# 02.net
KiCad netlist of a schematic drawn in Altium Designer
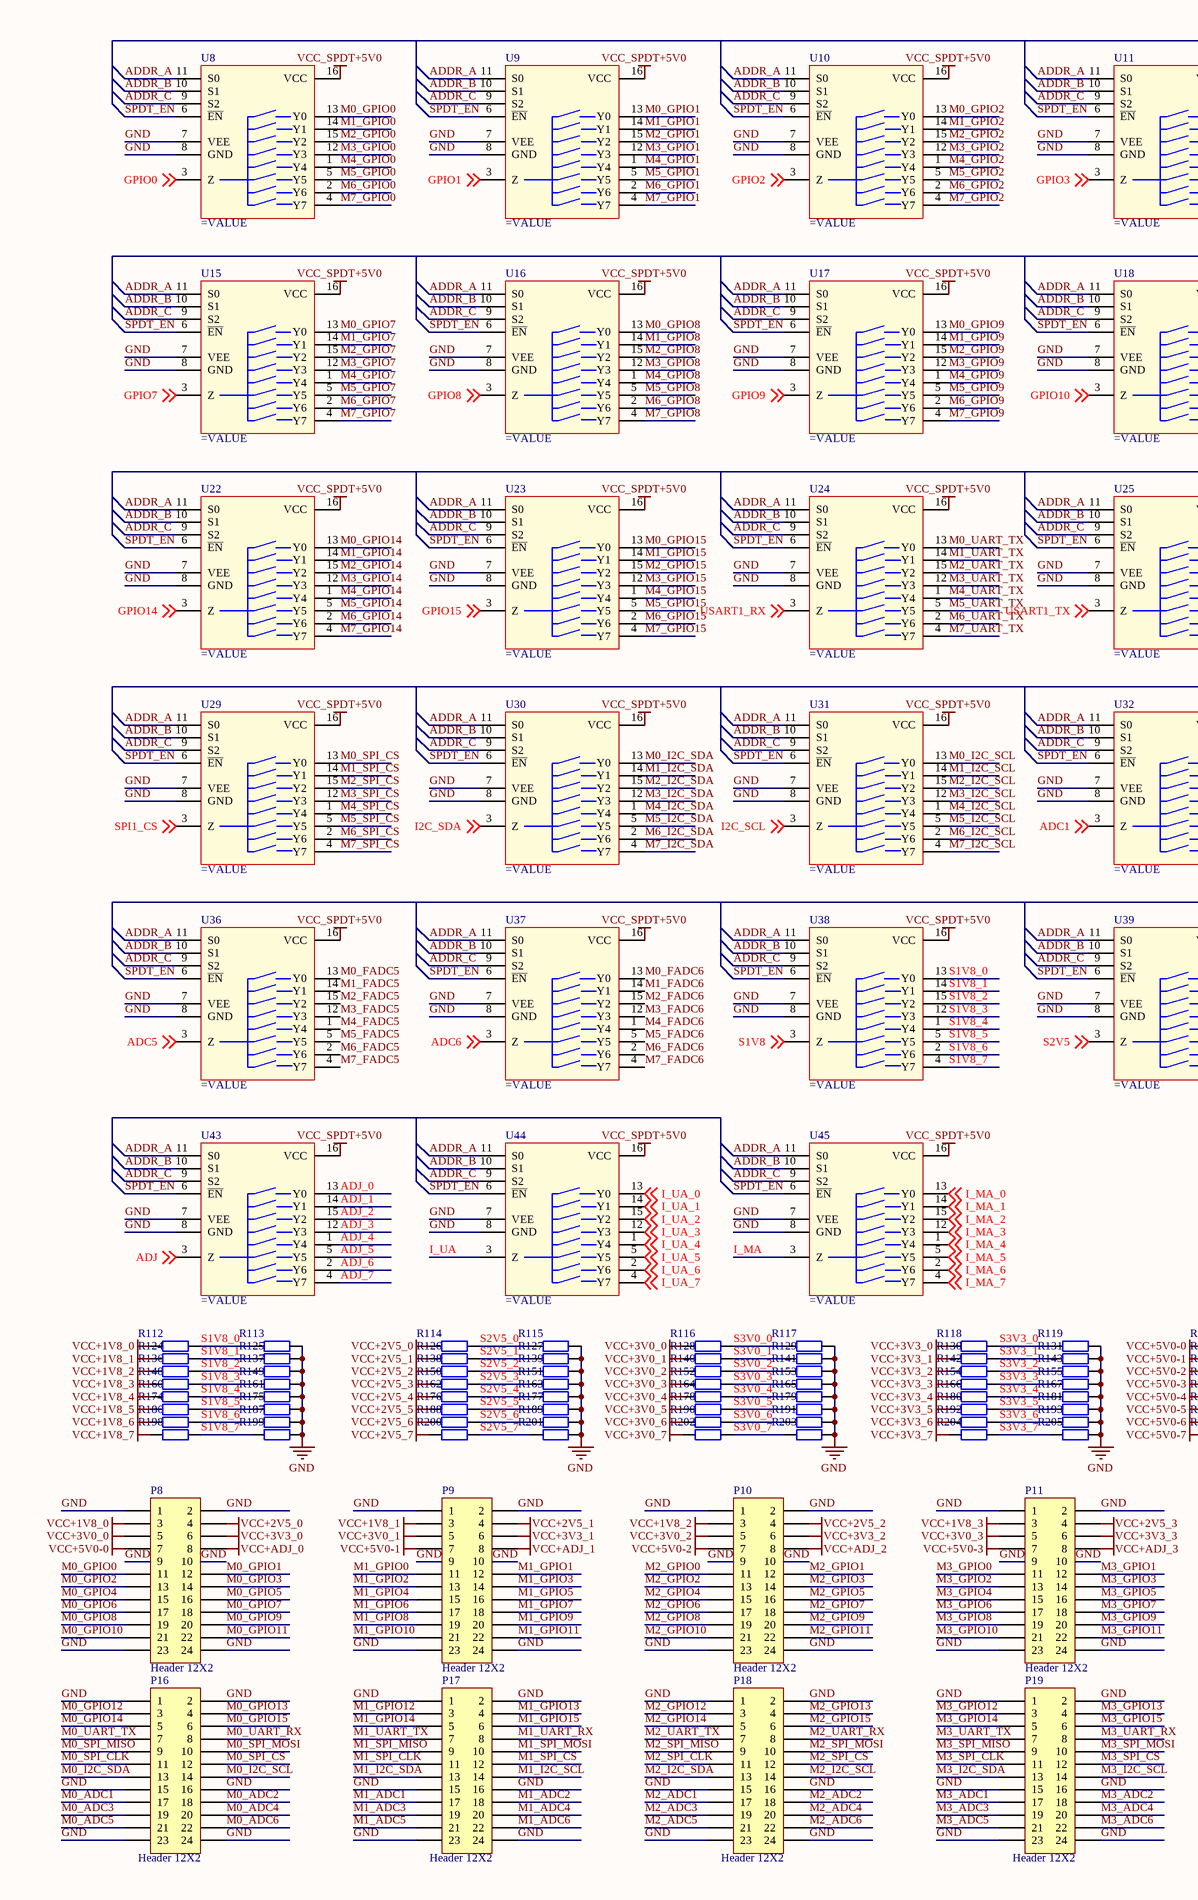
[diagram p0: 通用工装板02.SchDoc, left]
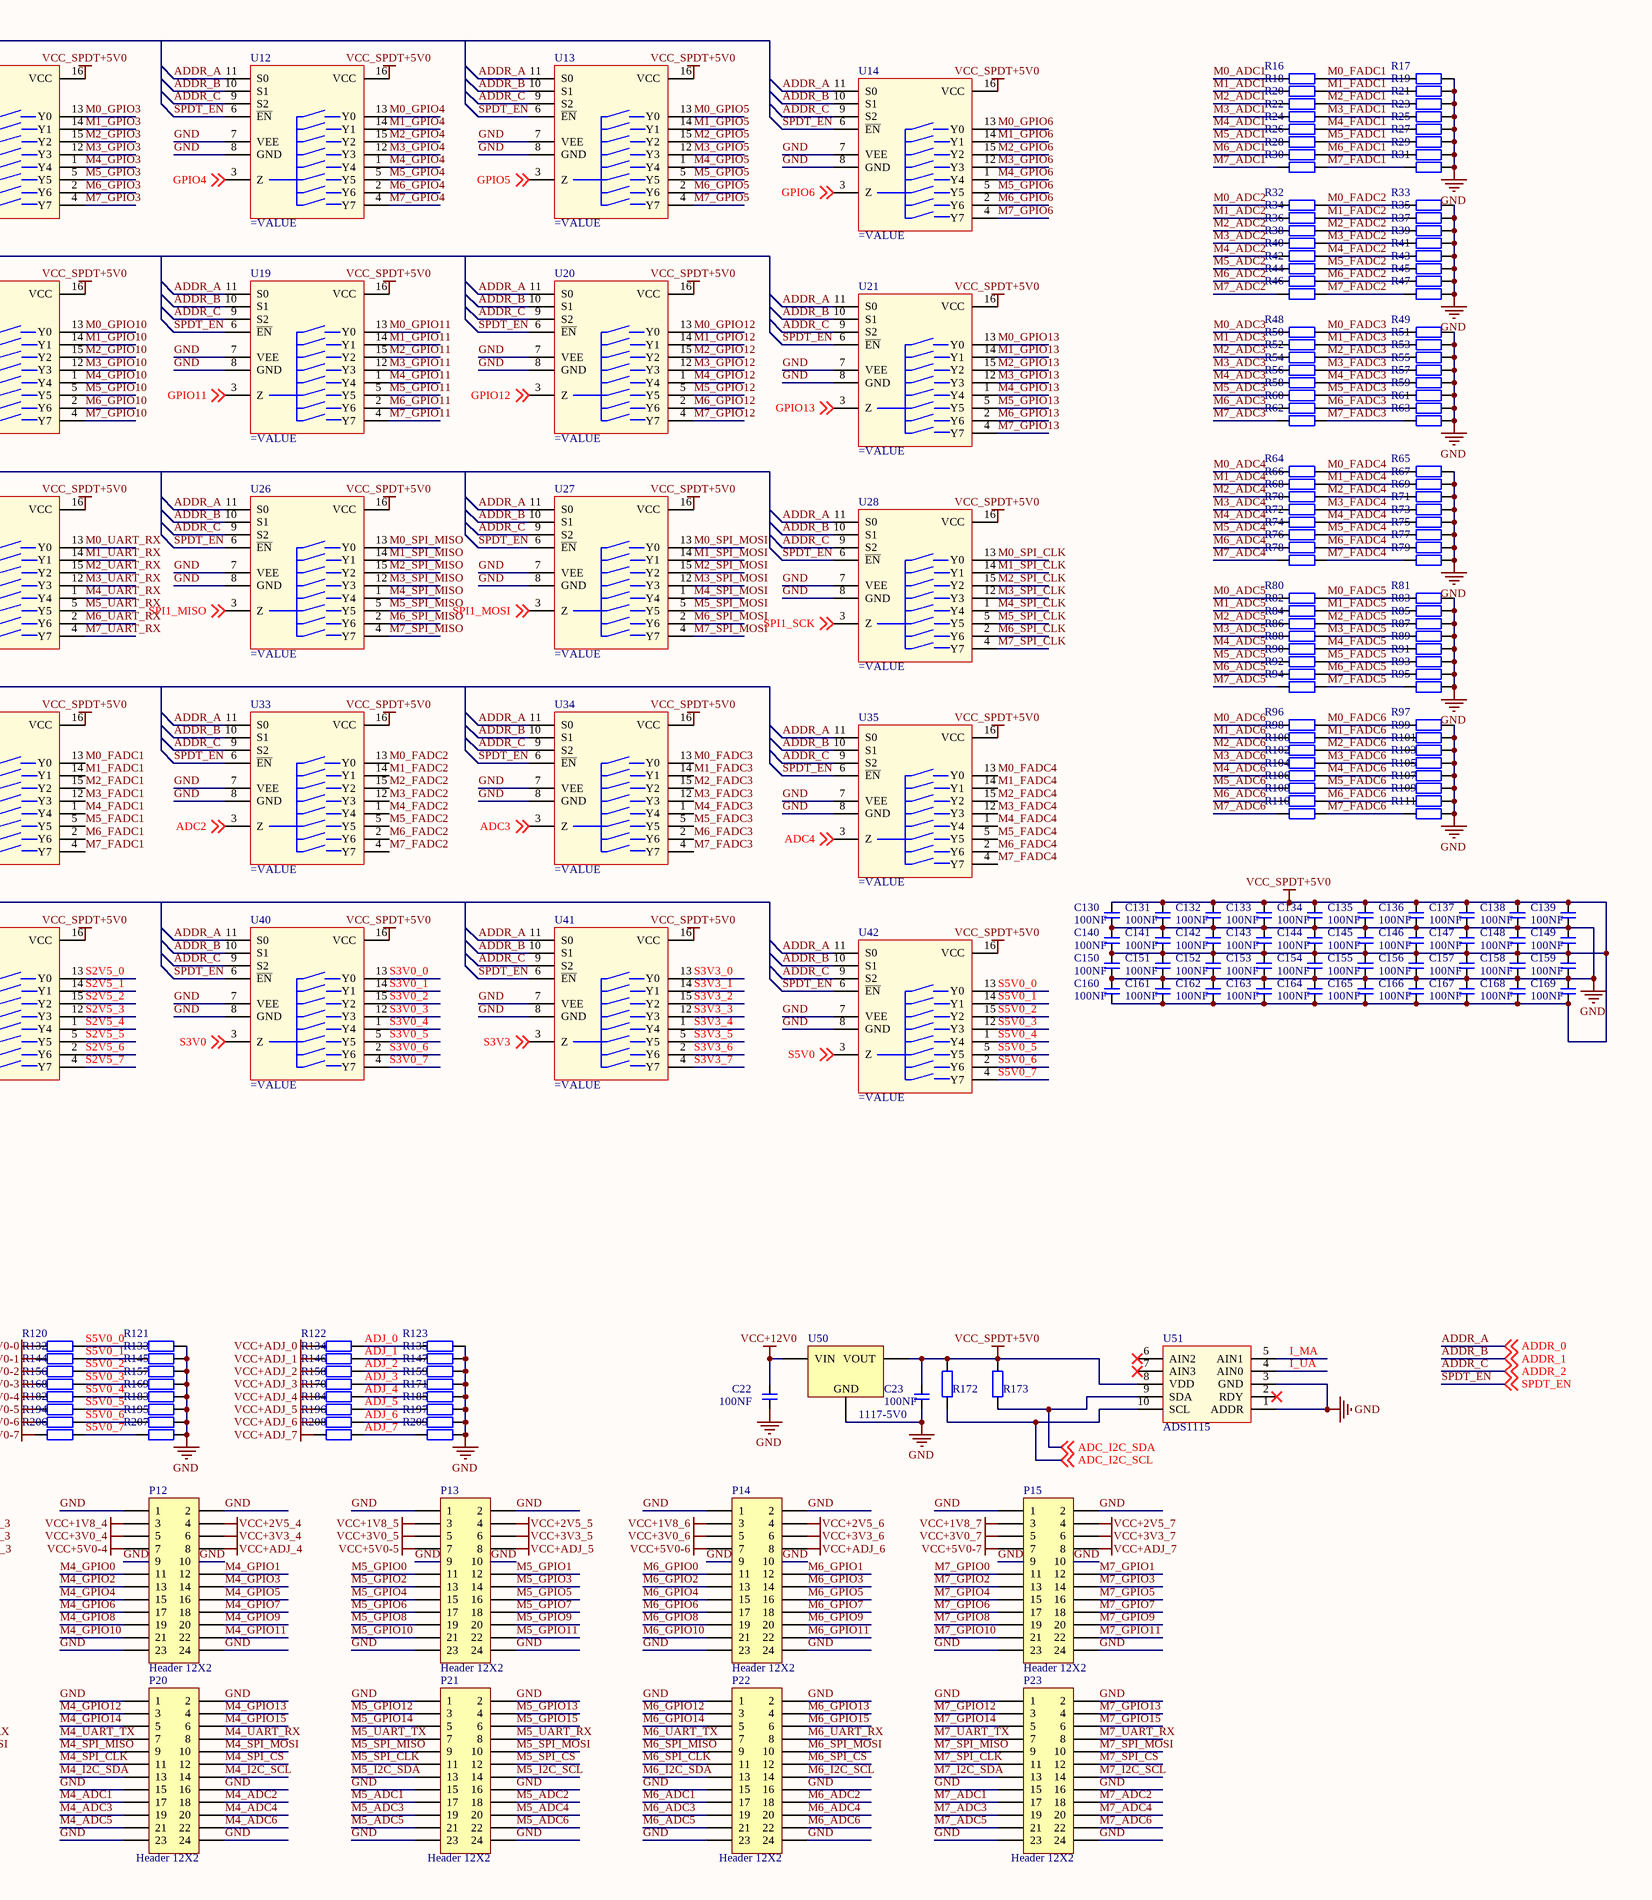
[diagram p1: 通用工装板02.SchDoc, right]

(export (version "E")
  (design (tool "Eeschema 10.0.6"))
  (components
    (comp (ref "C22")
      (value "100NF")
      (footprint "c0402")
      (description "无极性电容")
      (libsource (lib "瑞臻信息") (part "无极性电容"))
    )
    (comp (ref "C23")
      (value "100NF")
      (footprint "c0402")
      (description "无极性电容")
      (libsource (lib "瑞臻信息") (part "无极性电容"))
    )
    (comp (ref "C130")
      (value "100NF")
      (footprint "c0402")
      (description "无极性电容")
      (libsource (lib "瑞臻信息") (part "无极性电容"))
    )
    (comp (ref "C131")
      (value "100NF")
      (footprint "c0402")
      (description "无极性电容")
      (libsource (lib "瑞臻信息") (part "无极性电容"))
    )
    (comp (ref "C132")
      (value "100NF")
      (footprint "c0402")
      (description "无极性电容")
      (libsource (lib "瑞臻信息") (part "无极性电容"))
    )
    (comp (ref "C133")
      (value "100NF")
      (footprint "c0402")
      (description "无极性电容")
      (libsource (lib "瑞臻信息") (part "无极性电容"))
    )
    (comp (ref "C134")
      (value "100NF")
      (footprint "c0402")
      (description "无极性电容")
      (libsource (lib "瑞臻信息") (part "无极性电容"))
    )
    (comp (ref "C135")
      (value "100NF")
      (footprint "c0402")
      (description "无极性电容")
      (libsource (lib "瑞臻信息") (part "无极性电容"))
    )
    (comp (ref "C136")
      (value "100NF")
      (footprint "c0402")
      (description "无极性电容")
      (libsource (lib "瑞臻信息") (part "无极性电容"))
    )
    (comp (ref "C137")
      (value "100NF")
      (footprint "c0402")
      (description "无极性电容")
      (libsource (lib "瑞臻信息") (part "无极性电容"))
    )
    (comp (ref "C138")
      (value "100NF")
      (footprint "c0402")
      (description "无极性电容")
      (libsource (lib "瑞臻信息") (part "无极性电容"))
    )
    (comp (ref "C139")
      (value "100NF")
      (footprint "c0402")
      (description "无极性电容")
      (libsource (lib "瑞臻信息") (part "无极性电容"))
    )
    (comp (ref "C140")
      (value "100NF")
      (footprint "c0402")
      (description "无极性电容")
      (libsource (lib "瑞臻信息") (part "无极性电容"))
    )
    (comp (ref "C141")
      (value "100NF")
      (footprint "c0402")
      (description "无极性电容")
      (libsource (lib "瑞臻信息") (part "无极性电容"))
    )
    (comp (ref "C142")
      (value "100NF")
      (footprint "c0402")
      (description "无极性电容")
      (libsource (lib "瑞臻信息") (part "无极性电容"))
    )
    (comp (ref "C143")
      (value "100NF")
      (footprint "c0402")
      (description "无极性电容")
      (libsource (lib "瑞臻信息") (part "无极性电容"))
    )
    (comp (ref "C144")
      (value "100NF")
      (footprint "c0402")
      (description "无极性电容")
      (libsource (lib "瑞臻信息") (part "无极性电容"))
    )
    (comp (ref "C145")
      (value "100NF")
      (footprint "c0402")
      (description "无极性电容")
      (libsource (lib "瑞臻信息") (part "无极性电容"))
    )
    (comp (ref "C146")
      (value "100NF")
      (footprint "c0402")
      (description "无极性电容")
      (libsource (lib "瑞臻信息") (part "无极性电容"))
    )
    (comp (ref "C147")
      (value "100NF")
      (footprint "c0402")
      (description "无极性电容")
      (libsource (lib "瑞臻信息") (part "无极性电容"))
    )
    (comp (ref "C148")
      (value "100NF")
      (footprint "c0402")
      (description "无极性电容")
      (libsource (lib "瑞臻信息") (part "无极性电容"))
    )
    (comp (ref "C149")
      (value "100NF")
      (footprint "c0402")
      (description "无极性电容")
      (libsource (lib "瑞臻信息") (part "无极性电容"))
    )
    (comp (ref "C150")
      (value "100NF")
      (footprint "c0402")
      (description "无极性电容")
      (libsource (lib "瑞臻信息") (part "无极性电容"))
    )
    (comp (ref "C151")
      (value "100NF")
      (footprint "c0402")
      (description "无极性电容")
      (libsource (lib "瑞臻信息") (part "无极性电容"))
    )
    (comp (ref "C152")
      (value "100NF")
      (footprint "c0402")
      (description "无极性电容")
      (libsource (lib "瑞臻信息") (part "无极性电容"))
    )
    (comp (ref "C153")
      (value "100NF")
      (footprint "c0402")
      (description "无极性电容")
      (libsource (lib "瑞臻信息") (part "无极性电容"))
    )
    (comp (ref "C154")
      (value "100NF")
      (footprint "c0402")
      (description "无极性电容")
      (libsource (lib "瑞臻信息") (part "无极性电容"))
    )
    (comp (ref "C155")
      (value "100NF")
      (footprint "c0402")
      (description "无极性电容")
      (libsource (lib "瑞臻信息") (part "无极性电容"))
    )
    (comp (ref "C156")
      (value "100NF")
      (footprint "c0402")
      (description "无极性电容")
      (libsource (lib "瑞臻信息") (part "无极性电容"))
    )
    (comp (ref "C157")
      (value "100NF")
      (footprint "c0402")
      (description "无极性电容")
      (libsource (lib "瑞臻信息") (part "无极性电容"))
    )
    (comp (ref "C158")
      (value "100NF")
      (footprint "c0402")
      (description "无极性电容")
      (libsource (lib "瑞臻信息") (part "无极性电容"))
    )
    (comp (ref "C159")
      (value "100NF")
      (footprint "c0402")
      (description "无极性电容")
      (libsource (lib "瑞臻信息") (part "无极性电容"))
    )
    (comp (ref "C160")
      (value "100NF")
      (footprint "c0402")
      (description "无极性电容")
      (libsource (lib "瑞臻信息") (part "无极性电容"))
    )
    (comp (ref "C161")
      (value "100NF")
      (footprint "c0402")
      (description "无极性电容")
      (libsource (lib "瑞臻信息") (part "无极性电容"))
    )
    (comp (ref "C162")
      (value "100NF")
      (footprint "c0402")
      (description "无极性电容")
      (libsource (lib "瑞臻信息") (part "无极性电容"))
    )
    (comp (ref "C163")
      (value "100NF")
      (footprint "c0402")
      (description "无极性电容")
      (libsource (lib "瑞臻信息") (part "无极性电容"))
    )
    (comp (ref "C164")
      (value "100NF")
      (footprint "c0402")
      (description "无极性电容")
      (libsource (lib "瑞臻信息") (part "无极性电容"))
    )
    (comp (ref "C165")
      (value "100NF")
      (footprint "c0402")
      (description "无极性电容")
      (libsource (lib "瑞臻信息") (part "无极性电容"))
    )
    (comp (ref "C166")
      (value "100NF")
      (footprint "c0402")
      (description "无极性电容")
      (libsource (lib "瑞臻信息") (part "无极性电容"))
    )
    (comp (ref "C167")
      (value "100NF")
      (footprint "c0402")
      (description "无极性电容")
      (libsource (lib "瑞臻信息") (part "无极性电容"))
    )
    (comp (ref "C168")
      (value "100NF")
      (footprint "c0402")
      (description "无极性电容")
      (libsource (lib "瑞臻信息") (part "无极性电容"))
    )
    (comp (ref "C169")
      (value "100NF")
      (footprint "c0402")
      (description "无极性电容")
      (libsource (lib "瑞臻信息") (part "无极性电容"))
    )
    (comp (ref "P8")
      (value "Header 12X2")
      (footprint "FPC_24P_AB_0R5_5R1X17R7")
      (description "Header, 12-Pin, Dual row")
      (fields (field (name "PUBLISHER") "Altium Limited"))
      (libsource (lib "Miscellaneous Connectors") (part "Header 12X2"))
    )
    (comp (ref "P9")
      (value "Header 12X2")
      (footprint "FPC_24P_AB_0R5_5R1X17R7")
      (description "Header, 12-Pin, Dual row")
      (fields (field (name "PUBLISHER") "Altium Limited"))
      (libsource (lib "Miscellaneous Connectors") (part "Header 12X2"))
    )
    (comp (ref "P10")
      (value "Header 12X2")
      (footprint "FPC_24P_AB_0R5_5R1X17R7")
      (description "Header, 12-Pin, Dual row")
      (fields (field (name "PUBLISHER") "Altium Limited"))
      (libsource (lib "Miscellaneous Connectors") (part "Header 12X2"))
    )
    (comp (ref "P11")
      (value "Header 12X2")
      (footprint "FPC_24P_AB_0R5_5R1X17R7")
      (description "Header, 12-Pin, Dual row")
      (fields (field (name "PUBLISHER") "Altium Limited"))
      (libsource (lib "Miscellaneous Connectors") (part "Header 12X2"))
    )
    (comp (ref "P12")
      (value "Header 12X2")
      (footprint "FPC_24P_AB_0R5_5R1X17R7")
      (description "Header, 12-Pin, Dual row")
      (fields (field (name "PUBLISHER") "Altium Limited"))
      (libsource (lib "Miscellaneous Connectors") (part "Header 12X2"))
    )
    (comp (ref "P13")
      (value "Header 12X2")
      (footprint "FPC_24P_AB_0R5_5R1X17R7")
      (description "Header, 12-Pin, Dual row")
      (fields (field (name "PUBLISHER") "Altium Limited"))
      (libsource (lib "Miscellaneous Connectors") (part "Header 12X2"))
    )
    (comp (ref "P14")
      (value "Header 12X2")
      (footprint "FPC_24P_AB_0R5_5R1X17R7")
      (description "Header, 12-Pin, Dual row")
      (fields (field (name "PUBLISHER") "Altium Limited"))
      (libsource (lib "Miscellaneous Connectors") (part "Header 12X2"))
    )
    (comp (ref "P15")
      (value "Header 12X2")
      (footprint "FPC_24P_AB_0R5_5R1X17R7")
      (description "Header, 12-Pin, Dual row")
      (fields (field (name "PUBLISHER") "Altium Limited"))
      (libsource (lib "Miscellaneous Connectors") (part "Header 12X2"))
    )
    (comp (ref "P16")
      (value "Header 12X2")
      (footprint "FPC_24P_AB_0R5_5R1X17R7")
      (description "Header, 12-Pin, Dual row")
      (fields (field (name "PUBLISHER") "Altium Limited"))
      (libsource (lib "Miscellaneous Connectors") (part "Header 12X2"))
    )
    (comp (ref "P17")
      (value "Header 12X2")
      (footprint "FPC_24P_AB_0R5_5R1X17R7")
      (description "Header, 12-Pin, Dual row")
      (fields (field (name "PUBLISHER") "Altium Limited"))
      (libsource (lib "Miscellaneous Connectors") (part "Header 12X2"))
    )
    (comp (ref "P18")
      (value "Header 12X2")
      (footprint "FPC_24P_AB_0R5_5R1X17R7")
      (description "Header, 12-Pin, Dual row")
      (fields (field (name "PUBLISHER") "Altium Limited"))
      (libsource (lib "Miscellaneous Connectors") (part "Header 12X2"))
    )
    (comp (ref "P19")
      (value "Header 12X2")
      (footprint "FPC_24P_AB_0R5_5R1X17R7")
      (description "Header, 12-Pin, Dual row")
      (fields (field (name "PUBLISHER") "Altium Limited"))
      (libsource (lib "Miscellaneous Connectors") (part "Header 12X2"))
    )
    (comp (ref "P20")
      (value "Header 12X2")
      (footprint "FPC_24P_AB_0R5_5R1X17R7")
      (description "Header, 12-Pin, Dual row")
      (fields (field (name "PUBLISHER") "Altium Limited"))
      (libsource (lib "Miscellaneous Connectors") (part "Header 12X2"))
    )
    (comp (ref "P21")
      (value "Header 12X2")
      (footprint "FPC_24P_AB_0R5_5R1X17R7")
      (description "Header, 12-Pin, Dual row")
      (fields (field (name "PUBLISHER") "Altium Limited"))
      (libsource (lib "Miscellaneous Connectors") (part "Header 12X2"))
    )
    (comp (ref "P22")
      (value "Header 12X2")
      (footprint "FPC_24P_AB_0R5_5R1X17R7")
      (description "Header, 12-Pin, Dual row")
      (fields (field (name "PUBLISHER") "Altium Limited"))
      (libsource (lib "Miscellaneous Connectors") (part "Header 12X2"))
    )
    (comp (ref "P23")
      (value "Header 12X2")
      (footprint "FPC_24P_AB_0R5_5R1X17R7")
      (description "Header, 12-Pin, Dual row")
      (fields (field (name "PUBLISHER") "Altium Limited"))
      (libsource (lib "Miscellaneous Connectors") (part "Header 12X2"))
    )
    (comp (ref "R16")
      (value "10K")
      (footprint "r0402")
      (description "普通电阻")
      (libsource (lib "瑞臻信息") (part "普通电阻"))
    )
    (comp (ref "R17")
      (value "20K")
      (footprint "r0402")
      (description "普通电阻")
      (libsource (lib "瑞臻信息") (part "普通电阻"))
    )
    (comp (ref "R18")
      (value "10K")
      (footprint "r0402")
      (description "普通电阻")
      (libsource (lib "瑞臻信息") (part "普通电阻"))
    )
    (comp (ref "R19")
      (value "20K")
      (footprint "r0402")
      (description "普通电阻")
      (libsource (lib "瑞臻信息") (part "普通电阻"))
    )
    (comp (ref "R20")
      (value "10K")
      (footprint "r0402")
      (description "普通电阻")
      (libsource (lib "瑞臻信息") (part "普通电阻"))
    )
    (comp (ref "R21")
      (value "20K")
      (footprint "r0402")
      (description "普通电阻")
      (libsource (lib "瑞臻信息") (part "普通电阻"))
    )
    (comp (ref "R22")
      (value "10K")
      (footprint "r0402")
      (description "普通电阻")
      (libsource (lib "瑞臻信息") (part "普通电阻"))
    )
    (comp (ref "R23")
      (value "20K")
      (footprint "r0402")
      (description "普通电阻")
      (libsource (lib "瑞臻信息") (part "普通电阻"))
    )
    (comp (ref "R24")
      (value "10K")
      (footprint "r0402")
      (description "普通电阻")
      (libsource (lib "瑞臻信息") (part "普通电阻"))
    )
    (comp (ref "R25")
      (value "20K")
      (footprint "r0402")
      (description "普通电阻")
      (libsource (lib "瑞臻信息") (part "普通电阻"))
    )
    (comp (ref "R26")
      (value "10K")
      (footprint "r0402")
      (description "普通电阻")
      (libsource (lib "瑞臻信息") (part "普通电阻"))
    )
    (comp (ref "R27")
      (value "20K")
      (footprint "r0402")
      (description "普通电阻")
      (libsource (lib "瑞臻信息") (part "普通电阻"))
    )
    (comp (ref "R28")
      (value "10K")
      (footprint "r0402")
      (description "普通电阻")
      (libsource (lib "瑞臻信息") (part "普通电阻"))
    )
    (comp (ref "R29")
      (value "20K")
      (footprint "r0402")
      (description "普通电阻")
      (libsource (lib "瑞臻信息") (part "普通电阻"))
    )
    (comp (ref "R30")
      (value "10K")
      (footprint "r0402")
      (description "普通电阻")
      (libsource (lib "瑞臻信息") (part "普通电阻"))
    )
    (comp (ref "R31")
      (value "20K")
      (footprint "r0402")
      (description "普通电阻")
      (libsource (lib "瑞臻信息") (part "普通电阻"))
    )
    (comp (ref "R32")
      (value "10K")
      (footprint "r0402")
      (description "普通电阻")
      (libsource (lib "瑞臻信息") (part "普通电阻"))
    )
    (comp (ref "R33")
      (value "20K")
      (footprint "r0402")
      (description "普通电阻")
      (libsource (lib "瑞臻信息") (part "普通电阻"))
    )
    (comp (ref "R34")
      (value "10K")
      (footprint "r0402")
      (description "普通电阻")
      (libsource (lib "瑞臻信息") (part "普通电阻"))
    )
    (comp (ref "R35")
      (value "20K")
      (footprint "r0402")
      (description "普通电阻")
      (libsource (lib "瑞臻信息") (part "普通电阻"))
    )
    (comp (ref "R36")
      (value "10K")
      (footprint "r0402")
      (description "普通电阻")
      (libsource (lib "瑞臻信息") (part "普通电阻"))
    )
    (comp (ref "R37")
      (value "20K")
      (footprint "r0402")
      (description "普通电阻")
      (libsource (lib "瑞臻信息") (part "普通电阻"))
    )
    (comp (ref "R38")
      (value "10K")
      (footprint "r0402")
      (description "普通电阻")
      (libsource (lib "瑞臻信息") (part "普通电阻"))
    )
    (comp (ref "R39")
      (value "20K")
      (footprint "r0402")
      (description "普通电阻")
      (libsource (lib "瑞臻信息") (part "普通电阻"))
    )
    (comp (ref "R40")
      (value "10K")
      (footprint "r0402")
      (description "普通电阻")
      (libsource (lib "瑞臻信息") (part "普通电阻"))
    )
    (comp (ref "R41")
      (value "20K")
      (footprint "r0402")
      (description "普通电阻")
      (libsource (lib "瑞臻信息") (part "普通电阻"))
    )
    (comp (ref "R42")
      (value "10K")
      (footprint "r0402")
      (description "普通电阻")
      (libsource (lib "瑞臻信息") (part "普通电阻"))
    )
    (comp (ref "R43")
      (value "20K")
      (footprint "r0402")
      (description "普通电阻")
      (libsource (lib "瑞臻信息") (part "普通电阻"))
    )
    (comp (ref "R44")
      (value "10K")
      (footprint "r0402")
      (description "普通电阻")
      (libsource (lib "瑞臻信息") (part "普通电阻"))
    )
    (comp (ref "R45")
      (value "20K")
      (footprint "r0402")
      (description "普通电阻")
      (libsource (lib "瑞臻信息") (part "普通电阻"))
    )
    (comp (ref "R46")
      (value "10K")
      (footprint "r0402")
      (description "普通电阻")
      (libsource (lib "瑞臻信息") (part "普通电阻"))
    )
    (comp (ref "R47")
      (value "20K")
      (footprint "r0402")
      (description "普通电阻")
      (libsource (lib "瑞臻信息") (part "普通电阻"))
    )
    (comp (ref "R48")
      (value "10K")
      (footprint "r0402")
      (description "普通电阻")
      (libsource (lib "瑞臻信息") (part "普通电阻"))
    )
    (comp (ref "R49")
      (value "20K")
      (footprint "r0402")
      (description "普通电阻")
      (libsource (lib "瑞臻信息") (part "普通电阻"))
    )
    (comp (ref "R50")
      (value "10K")
      (footprint "r0402")
      (description "普通电阻")
      (libsource (lib "瑞臻信息") (part "普通电阻"))
    )
    (comp (ref "R51")
      (value "20K")
      (footprint "r0402")
      (description "普通电阻")
      (libsource (lib "瑞臻信息") (part "普通电阻"))
    )
    (comp (ref "R52")
      (value "10K")
      (footprint "r0402")
      (description "普通电阻")
      (libsource (lib "瑞臻信息") (part "普通电阻"))
    )
    (comp (ref "R53")
      (value "20K")
      (footprint "r0402")
      (description "普通电阻")
      (libsource (lib "瑞臻信息") (part "普通电阻"))
    )
    (comp (ref "R54")
      (value "10K")
      (footprint "r0402")
      (description "普通电阻")
      (libsource (lib "瑞臻信息") (part "普通电阻"))
    )
    (comp (ref "R55")
      (value "20K")
      (footprint "r0402")
      (description "普通电阻")
      (libsource (lib "瑞臻信息") (part "普通电阻"))
    )
    (comp (ref "R56")
      (value "10K")
      (footprint "r0402")
      (description "普通电阻")
      (libsource (lib "瑞臻信息") (part "普通电阻"))
    )
    (comp (ref "R57")
      (value "20K")
      (footprint "r0402")
      (description "普通电阻")
      (libsource (lib "瑞臻信息") (part "普通电阻"))
    )
    (comp (ref "R58")
      (value "10K")
      (footprint "r0402")
      (description "普通电阻")
      (libsource (lib "瑞臻信息") (part "普通电阻"))
    )
    (comp (ref "R59")
      (value "20K")
      (footprint "r0402")
      (description "普通电阻")
      (libsource (lib "瑞臻信息") (part "普通电阻"))
    )
    (comp (ref "R60")
      (value "10K")
      (footprint "r0402")
      (description "普通电阻")
      (libsource (lib "瑞臻信息") (part "普通电阻"))
    )
    (comp (ref "R61")
      (value "20K")
      (footprint "r0402")
      (description "普通电阻")
      (libsource (lib "瑞臻信息") (part "普通电阻"))
    )
    (comp (ref "R62")
      (value "10K")
      (footprint "r0402")
      (description "普通电阻")
      (libsource (lib "瑞臻信息") (part "普通电阻"))
    )
    (comp (ref "R63")
      (value "20K")
      (footprint "r0402")
      (description "普通电阻")
      (libsource (lib "瑞臻信息") (part "普通电阻"))
    )
    (comp (ref "R64")
      (value "10K")
      (footprint "r0402")
      (description "普通电阻")
      (libsource (lib "瑞臻信息") (part "普通电阻"))
    )
    (comp (ref "R65")
      (value "20K")
      (footprint "r0402")
      (description "普通电阻")
      (libsource (lib "瑞臻信息") (part "普通电阻"))
    )
    (comp (ref "R66")
      (value "10K")
      (footprint "r0402")
      (description "普通电阻")
      (libsource (lib "瑞臻信息") (part "普通电阻"))
    )
    (comp (ref "R67")
      (value "20K")
      (footprint "r0402")
      (description "普通电阻")
      (libsource (lib "瑞臻信息") (part "普通电阻"))
    )
    (comp (ref "R68")
      (value "10K")
      (footprint "r0402")
      (description "普通电阻")
      (libsource (lib "瑞臻信息") (part "普通电阻"))
    )
    (comp (ref "R69")
      (value "20K")
      (footprint "r0402")
      (description "普通电阻")
      (libsource (lib "瑞臻信息") (part "普通电阻"))
    )
    (comp (ref "R70")
      (value "10K")
      (footprint "r0402")
      (description "普通电阻")
      (libsource (lib "瑞臻信息") (part "普通电阻"))
    )
    (comp (ref "R71")
      (value "20K")
      (footprint "r0402")
      (description "普通电阻")
      (libsource (lib "瑞臻信息") (part "普通电阻"))
    )
    (comp (ref "R72")
      (value "10K")
      (footprint "r0402")
      (description "普通电阻")
      (libsource (lib "瑞臻信息") (part "普通电阻"))
    )
    (comp (ref "R73")
      (value "20K")
      (footprint "r0402")
      (description "普通电阻")
      (libsource (lib "瑞臻信息") (part "普通电阻"))
    )
    (comp (ref "R74")
      (value "10K")
      (footprint "r0402")
      (description "普通电阻")
      (libsource (lib "瑞臻信息") (part "普通电阻"))
    )
    (comp (ref "R75")
      (value "20K")
      (footprint "r0402")
      (description "普通电阻")
      (libsource (lib "瑞臻信息") (part "普通电阻"))
    )
    (comp (ref "R76")
      (value "10K")
      (footprint "r0402")
      (description "普通电阻")
      (libsource (lib "瑞臻信息") (part "普通电阻"))
    )
    (comp (ref "R77")
      (value "20K")
      (footprint "r0402")
      (description "普通电阻")
      (libsource (lib "瑞臻信息") (part "普通电阻"))
    )
    (comp (ref "R78")
      (value "10K")
      (footprint "r0402")
      (description "普通电阻")
      (libsource (lib "瑞臻信息") (part "普通电阻"))
    )
    (comp (ref "R79")
      (value "20K")
      (footprint "r0402")
      (description "普通电阻")
      (libsource (lib "瑞臻信息") (part "普通电阻"))
    )
    (comp (ref "R80")
      (value "10K")
      (footprint "r0402")
      (description "普通电阻")
      (libsource (lib "瑞臻信息") (part "普通电阻"))
    )
    (comp (ref "R81")
      (value "20K")
      (footprint "r0402")
      (description "普通电阻")
      (libsource (lib "瑞臻信息") (part "普通电阻"))
    )
    (comp (ref "R82")
      (value "10K")
      (footprint "r0402")
      (description "普通电阻")
      (libsource (lib "瑞臻信息") (part "普通电阻"))
    )
    (comp (ref "R83")
      (value "20K")
      (footprint "r0402")
      (description "普通电阻")
      (libsource (lib "瑞臻信息") (part "普通电阻"))
    )
    (comp (ref "R84")
      (value "10K")
      (footprint "r0402")
      (description "普通电阻")
      (libsource (lib "瑞臻信息") (part "普通电阻"))
    )
    (comp (ref "R85")
      (value "20K")
      (footprint "r0402")
      (description "普通电阻")
      (libsource (lib "瑞臻信息") (part "普通电阻"))
    )
    (comp (ref "R86")
      (value "10K")
      (footprint "r0402")
      (description "普通电阻")
      (libsource (lib "瑞臻信息") (part "普通电阻"))
    )
    (comp (ref "R87")
      (value "20K")
      (footprint "r0402")
      (description "普通电阻")
      (libsource (lib "瑞臻信息") (part "普通电阻"))
    )
    (comp (ref "R88")
      (value "10K")
      (footprint "r0402")
      (description "普通电阻")
      (libsource (lib "瑞臻信息") (part "普通电阻"))
    )
    (comp (ref "R89")
      (value "20K")
      (footprint "r0402")
      (description "普通电阻")
      (libsource (lib "瑞臻信息") (part "普通电阻"))
    )
    (comp (ref "R90")
      (value "10K")
      (footprint "r0402")
      (description "普通电阻")
      (libsource (lib "瑞臻信息") (part "普通电阻"))
    )
    (comp (ref "R91")
      (value "20K")
      (footprint "r0402")
      (description "普通电阻")
      (libsource (lib "瑞臻信息") (part "普通电阻"))
    )
    (comp (ref "R92")
      (value "10K")
      (footprint "r0402")
      (description "普通电阻")
      (libsource (lib "瑞臻信息") (part "普通电阻"))
    )
    (comp (ref "R93")
      (value "20K")
      (footprint "r0402")
      (description "普通电阻")
      (libsource (lib "瑞臻信息") (part "普通电阻"))
    )
    (comp (ref "R94")
      (value "10K")
      (footprint "r0402")
      (description "普通电阻")
      (libsource (lib "瑞臻信息") (part "普通电阻"))
    )
    (comp (ref "R95")
      (value "20K")
      (footprint "r0402")
      (description "普通电阻")
      (libsource (lib "瑞臻信息") (part "普通电阻"))
    )
    (comp (ref "R96")
      (value "10K")
      (footprint "r0402")
      (description "普通电阻")
      (libsource (lib "瑞臻信息") (part "普通电阻"))
    )
    (comp (ref "R97")
      (value "20K")
      (footprint "r0402")
      (description "普通电阻")
      (libsource (lib "瑞臻信息") (part "普通电阻"))
    )
    (comp (ref "R98")
      (value "10K")
      (footprint "r0402")
      (description "普通电阻")
      (libsource (lib "瑞臻信息") (part "普通电阻"))
    )
    (comp (ref "R99")
      (value "20K")
      (footprint "r0402")
      (description "普通电阻")
      (libsource (lib "瑞臻信息") (part "普通电阻"))
    )
    (comp (ref "R100")
      (value "10K")
      (footprint "r0402")
      (description "普通电阻")
      (libsource (lib "瑞臻信息") (part "普通电阻"))
    )
    (comp (ref "R101")
      (value "20K")
      (footprint "r0402")
      (description "普通电阻")
      (libsource (lib "瑞臻信息") (part "普通电阻"))
    )
    (comp (ref "R102")
      (value "10K")
      (footprint "r0402")
      (description "普通电阻")
      (libsource (lib "瑞臻信息") (part "普通电阻"))
    )
    (comp (ref "R103")
      (value "20K")
      (footprint "r0402")
      (description "普通电阻")
      (libsource (lib "瑞臻信息") (part "普通电阻"))
    )
    (comp (ref "R104")
      (value "10K")
      (footprint "r0402")
      (description "普通电阻")
      (libsource (lib "瑞臻信息") (part "普通电阻"))
    )
    (comp (ref "R105")
      (value "20K")
      (footprint "r0402")
      (description "普通电阻")
      (libsource (lib "瑞臻信息") (part "普通电阻"))
    )
    (comp (ref "R106")
      (value "10K")
      (footprint "r0402")
      (description "普通电阻")
      (libsource (lib "瑞臻信息") (part "普通电阻"))
    )
    (comp (ref "R107")
      (value "20K")
      (footprint "r0402")
      (description "普通电阻")
      (libsource (lib "瑞臻信息") (part "普通电阻"))
    )
    (comp (ref "R108")
      (value "10K")
      (footprint "r0402")
      (description "普通电阻")
      (libsource (lib "瑞臻信息") (part "普通电阻"))
    )
    (comp (ref "R109")
      (value "20K")
      (footprint "r0402")
      (description "普通电阻")
      (libsource (lib "瑞臻信息") (part "普通电阻"))
    )
    (comp (ref "R110")
      (value "10K")
      (footprint "r0402")
      (description "普通电阻")
      (libsource (lib "瑞臻信息") (part "普通电阻"))
    )
    (comp (ref "R111")
      (value "20K")
      (footprint "r0402")
      (description "普通电阻")
      (libsource (lib "瑞臻信息") (part "普通电阻"))
    )
    (comp (ref "R112")
      (value "10K")
      (footprint "r0402")
      (description "普通电阻")
      (libsource (lib "瑞臻信息") (part "普通电阻"))
    )
    (comp (ref "R113")
      (value "10K")
      (footprint "r0402")
      (description "普通电阻")
      (libsource (lib "瑞臻信息") (part "普通电阻"))
    )
    (comp (ref "R114")
      (value "10K")
      (footprint "r0402")
      (description "普通电阻")
      (libsource (lib "瑞臻信息") (part "普通电阻"))
    )
    (comp (ref "R115")
      (value "10K")
      (footprint "r0402")
      (description "普通电阻")
      (libsource (lib "瑞臻信息") (part "普通电阻"))
    )
    (comp (ref "R116")
      (value "10K")
      (footprint "r0402")
      (description "普通电阻")
      (libsource (lib "瑞臻信息") (part "普通电阻"))
    )
    (comp (ref "R117")
      (value "10K")
      (footprint "r0402")
      (description "普通电阻")
      (libsource (lib "瑞臻信息") (part "普通电阻"))
    )
    (comp (ref "R118")
      (value "10K")
      (footprint "r0402")
      (description "普通电阻")
      (libsource (lib "瑞臻信息") (part "普通电阻"))
    )
    (comp (ref "R119")
      (value "10K")
      (footprint "r0402")
      (description "普通电阻")
      (libsource (lib "瑞臻信息") (part "普通电阻"))
    )
    (comp (ref "R120")
      (value "10K")
      (footprint "r0402")
      (description "普通电阻")
      (libsource (lib "瑞臻信息") (part "普通电阻"))
    )
    (comp (ref "R121")
      (value "10K")
      (footprint "r0402")
      (description "普通电阻")
      (libsource (lib "瑞臻信息") (part "普通电阻"))
    )
    (comp (ref "R122")
      (value "10K")
      (footprint "r0402")
      (description "普通电阻")
      (libsource (lib "瑞臻信息") (part "普通电阻"))
    )
    (comp (ref "R123")
      (value "10K")
      (footprint "r0402")
      (description "普通电阻")
      (libsource (lib "瑞臻信息") (part "普通电阻"))
    )
    (comp (ref "R124")
      (value "10K")
      (footprint "r0402")
      (description "普通电阻")
      (libsource (lib "瑞臻信息") (part "普通电阻"))
    )
    (comp (ref "R125")
      (value "10K")
      (footprint "r0402")
      (description "普通电阻")
      (libsource (lib "瑞臻信息") (part "普通电阻"))
    )
    (comp (ref "R126")
      (value "10K")
      (footprint "r0402")
      (description "普通电阻")
      (libsource (lib "瑞臻信息") (part "普通电阻"))
    )
    (comp (ref "R127")
      (value "10K")
      (footprint "r0402")
      (description "普通电阻")
      (libsource (lib "瑞臻信息") (part "普通电阻"))
    )
    (comp (ref "R128")
      (value "10K")
      (footprint "r0402")
      (description "普通电阻")
      (libsource (lib "瑞臻信息") (part "普通电阻"))
    )
    (comp (ref "R129")
      (value "10K")
      (footprint "r0402")
      (description "普通电阻")
      (libsource (lib "瑞臻信息") (part "普通电阻"))
    )
    (comp (ref "R130")
      (value "10K")
      (footprint "r0402")
      (description "普通电阻")
      (libsource (lib "瑞臻信息") (part "普通电阻"))
    )
    (comp (ref "R131")
      (value "10K")
      (footprint "r0402")
      (description "普通电阻")
      (libsource (lib "瑞臻信息") (part "普通电阻"))
    )
    (comp (ref "R132")
      (value "10K")
      (footprint "r0402")
      (description "普通电阻")
      (libsource (lib "瑞臻信息") (part "普通电阻"))
    )
    (comp (ref "R133")
      (value "10K")
      (footprint "r0402")
      (description "普通电阻")
      (libsource (lib "瑞臻信息") (part "普通电阻"))
    )
    (comp (ref "R134")
      (value "10K")
      (footprint "r0402")
      (description "普通电阻")
      (libsource (lib "瑞臻信息") (part "普通电阻"))
    )
    (comp (ref "R135")
      (value "10K")
      (footprint "r0402")
      (description "普通电阻")
      (libsource (lib "瑞臻信息") (part "普通电阻"))
    )
    (comp (ref "R136")
      (value "10K")
      (footprint "r0402")
      (description "普通电阻")
      (libsource (lib "瑞臻信息") (part "普通电阻"))
    )
    (comp (ref "R137")
      (value "10K")
      (footprint "r0402")
      (description "普通电阻")
      (libsource (lib "瑞臻信息") (part "普通电阻"))
    )
    (comp (ref "R138")
      (value "10K")
      (footprint "r0402")
      (description "普通电阻")
      (libsource (lib "瑞臻信息") (part "普通电阻"))
    )
    (comp (ref "R139")
      (value "10K")
      (footprint "r0402")
      (description "普通电阻")
      (libsource (lib "瑞臻信息") (part "普通电阻"))
    )
    (comp (ref "R140")
      (value "10K")
      (footprint "r0402")
      (description "普通电阻")
      (libsource (lib "瑞臻信息") (part "普通电阻"))
    )
    (comp (ref "R141")
      (value "10K")
      (footprint "r0402")
      (description "普通电阻")
      (libsource (lib "瑞臻信息") (part "普通电阻"))
    )
    (comp (ref "R142")
      (value "10K")
      (footprint "r0402")
      (description "普通电阻")
      (libsource (lib "瑞臻信息") (part "普通电阻"))
    )
    (comp (ref "R143")
      (value "10K")
      (footprint "r0402")
      (description "普通电阻")
      (libsource (lib "瑞臻信息") (part "普通电阻"))
    )
    (comp (ref "R144")
      (value "10K")
      (footprint "r0402")
      (description "普通电阻")
      (libsource (lib "瑞臻信息") (part "普通电阻"))
    )
    (comp (ref "R145")
      (value "10K")
      (footprint "r0402")
      (description "普通电阻")
      (libsource (lib "瑞臻信息") (part "普通电阻"))
    )
    (comp (ref "R146")
      (value "10K")
      (footprint "r0402")
      (description "普通电阻")
      (libsource (lib "瑞臻信息") (part "普通电阻"))
    )
    (comp (ref "R147")
      (value "10K")
      (footprint "r0402")
      (description "普通电阻")
      (libsource (lib "瑞臻信息") (part "普通电阻"))
    )
    (comp (ref "R148")
      (value "10K")
      (footprint "r0402")
      (description "普通电阻")
      (libsource (lib "瑞臻信息") (part "普通电阻"))
    )
    (comp (ref "R149")
      (value "10K")
      (footprint "r0402")
      (description "普通电阻")
      (libsource (lib "瑞臻信息") (part "普通电阻"))
    )
    (comp (ref "R150")
      (value "10K")
      (footprint "r0402")
      (description "普通电阻")
      (libsource (lib "瑞臻信息") (part "普通电阻"))
    )
    (comp (ref "R151")
      (value "10K")
      (footprint "r0402")
      (description "普通电阻")
      (libsource (lib "瑞臻信息") (part "普通电阻"))
    )
    (comp (ref "R152")
      (value "10K")
      (footprint "r0402")
      (description "普通电阻")
      (libsource (lib "瑞臻信息") (part "普通电阻"))
    )
    (comp (ref "R153")
      (value "10K")
      (footprint "r0402")
      (description "普通电阻")
      (libsource (lib "瑞臻信息") (part "普通电阻"))
    )
    (comp (ref "R154")
      (value "10K")
      (footprint "r0402")
      (description "普通电阻")
      (libsource (lib "瑞臻信息") (part "普通电阻"))
    )
    (comp (ref "R155")
      (value "10K")
      (footprint "r0402")
      (description "普通电阻")
      (libsource (lib "瑞臻信息") (part "普通电阻"))
    )
    (comp (ref "R156")
      (value "10K")
      (footprint "r0402")
      (description "普通电阻")
      (libsource (lib "瑞臻信息") (part "普通电阻"))
    )
    (comp (ref "R157")
      (value "10K")
      (footprint "r0402")
      (description "普通电阻")
      (libsource (lib "瑞臻信息") (part "普通电阻"))
    )
    (comp (ref "R158")
      (value "10K")
      (footprint "r0402")
      (description "普通电阻")
      (libsource (lib "瑞臻信息") (part "普通电阻"))
    )
    (comp (ref "R159")
      (value "10K")
      (footprint "r0402")
      (description "普通电阻")
      (libsource (lib "瑞臻信息") (part "普通电阻"))
    )
    (comp (ref "R160")
      (value "10K")
      (footprint "r0402")
      (description "普通电阻")
      (libsource (lib "瑞臻信息") (part "普通电阻"))
    )
    (comp (ref "R161")
      (value "10K")
      (footprint "r0402")
      (description "普通电阻")
      (libsource (lib "瑞臻信息") (part "普通电阻"))
    )
    (comp (ref "R162")
      (value "10K")
      (footprint "r0402")
      (description "普通电阻")
      (libsource (lib "瑞臻信息") (part "普通电阻"))
    )
    (comp (ref "R163")
      (value "10K")
      (footprint "r0402")
      (description "普通电阻")
      (libsource (lib "瑞臻信息") (part "普通电阻"))
    )
    (comp (ref "R164")
      (value "10K")
      (footprint "r0402")
      (description "普通电阻")
      (libsource (lib "瑞臻信息") (part "普通电阻"))
    )
    (comp (ref "R165")
      (value "10K")
      (footprint "r0402")
      (description "普通电阻")
      (libsource (lib "瑞臻信息") (part "普通电阻"))
    )
    (comp (ref "R166")
      (value "10K")
      (footprint "r0402")
      (description "普通电阻")
      (libsource (lib "瑞臻信息") (part "普通电阻"))
    )
    (comp (ref "R167")
      (value "10K")
      (footprint "r0402")
      (description "普通电阻")
      (libsource (lib "瑞臻信息") (part "普通电阻"))
    )
    (comp (ref "R168")
      (value "10K")
      (footprint "r0402")
      (description "普通电阻")
      (libsource (lib "瑞臻信息") (part "普通电阻"))
    )
    (comp (ref "R169")
      (value "10K")
      (footprint "r0402")
      (description "普通电阻")
      (libsource (lib "瑞臻信息") (part "普通电阻"))
    )
    (comp (ref "R170")
      (value "10K")
      (footprint "r0402")
      (description "普通电阻")
      (libsource (lib "瑞臻信息") (part "普通电阻"))
    )
    (comp (ref "R171")
      (value "10K")
      (footprint "r0402")
      (description "普通电阻")
      (libsource (lib "瑞臻信息") (part "普通电阻"))
    )
    (comp (ref "R172")
      (value "10K")
      (footprint "r0402")
      (description "普通电阻")
      (libsource (lib "") (part "普通电阻_1"))
    )
    (comp (ref "R173")
      (value "10K")
      (footprint "r0402")
      (description "普通电阻")
      (libsource (lib "") (part "普通电阻_1"))
    )
    (comp (ref "R174")
      (value "10K")
      (footprint "r0402")
      (description "普通电阻")
      (libsource (lib "瑞臻信息") (part "普通电阻"))
    )
    (comp (ref "R175")
      (value "10K")
      (footprint "r0402")
      (description "普通电阻")
      (libsource (lib "瑞臻信息") (part "普通电阻"))
    )
    (comp (ref "R176")
      (value "10K")
      (footprint "r0402")
      (description "普通电阻")
      (libsource (lib "瑞臻信息") (part "普通电阻"))
    )
    (comp (ref "R177")
      (value "10K")
      (footprint "r0402")
      (description "普通电阻")
      (libsource (lib "瑞臻信息") (part "普通电阻"))
    )
    (comp (ref "R178")
      (value "10K")
      (footprint "r0402")
      (description "普通电阻")
      (libsource (lib "瑞臻信息") (part "普通电阻"))
    )
    (comp (ref "R179")
      (value "10K")
      (footprint "r0402")
      (description "普通电阻")
      (libsource (lib "瑞臻信息") (part "普通电阻"))
    )
    (comp (ref "R180")
      (value "10K")
      (footprint "r0402")
      (description "普通电阻")
      (libsource (lib "瑞臻信息") (part "普通电阻"))
    )
    (comp (ref "R181")
      (value "10K")
      (footprint "r0402")
      (description "普通电阻")
      (libsource (lib "瑞臻信息") (part "普通电阻"))
    )
    (comp (ref "R182")
      (value "10K")
      (footprint "r0402")
      (description "普通电阻")
      (libsource (lib "瑞臻信息") (part "普通电阻"))
    )
    (comp (ref "R183")
      (value "10K")
      (footprint "r0402")
      (description "普通电阻")
      (libsource (lib "瑞臻信息") (part "普通电阻"))
    )
    (comp (ref "R184")
      (value "10K")
      (footprint "r0402")
      (description "普通电阻")
      (libsource (lib "瑞臻信息") (part "普通电阻"))
    )
    (comp (ref "R185")
      (value "10K")
      (footprint "r0402")
      (description "普通电阻")
      (libsource (lib "瑞臻信息") (part "普通电阻"))
    )
    (comp (ref "R186")
      (value "10K")
      (footprint "r0402")
      (description "普通电阻")
      (libsource (lib "瑞臻信息") (part "普通电阻"))
    )
    (comp (ref "R187")
      (value "10K")
      (footprint "r0402")
      (description "普通电阻")
      (libsource (lib "瑞臻信息") (part "普通电阻"))
    )
    (comp (ref "R188")
      (value "10K")
      (footprint "r0402")
      (description "普通电阻")
      (libsource (lib "瑞臻信息") (part "普通电阻"))
    )
    (comp (ref "R189")
      (value "10K")
      (footprint "r0402")
      (description "普通电阻")
      (libsource (lib "瑞臻信息") (part "普通电阻"))
    )
    (comp (ref "R190")
      (value "10K")
      (footprint "r0402")
      (description "普通电阻")
      (libsource (lib "瑞臻信息") (part "普通电阻"))
    )
    (comp (ref "R191")
      (value "10K")
      (footprint "r0402")
      (description "普通电阻")
      (libsource (lib "瑞臻信息") (part "普通电阻"))
    )
    (comp (ref "R192")
      (value "10K")
      (footprint "r0402")
      (description "普通电阻")
      (libsource (lib "瑞臻信息") (part "普通电阻"))
    )
    (comp (ref "R193")
      (value "10K")
      (footprint "r0402")
      (description "普通电阻")
      (libsource (lib "瑞臻信息") (part "普通电阻"))
    )
    (comp (ref "R194")
      (value "10K")
      (footprint "r0402")
      (description "普通电阻")
      (libsource (lib "瑞臻信息") (part "普通电阻"))
    )
    (comp (ref "R195")
      (value "10K")
      (footprint "r0402")
      (description "普通电阻")
      (libsource (lib "瑞臻信息") (part "普通电阻"))
    )
    (comp (ref "R196")
      (value "10K")
      (footprint "r0402")
      (description "普通电阻")
      (libsource (lib "瑞臻信息") (part "普通电阻"))
    )
    (comp (ref "R197")
      (value "10K")
      (footprint "r0402")
      (description "普通电阻")
      (libsource (lib "瑞臻信息") (part "普通电阻"))
    )
    (comp (ref "R198")
      (value "10K")
      (footprint "r0402")
      (description "普通电阻")
      (libsource (lib "瑞臻信息") (part "普通电阻"))
    )
    (comp (ref "R199")
      (value "10K")
      (footprint "r0402")
      (description "普通电阻")
      (libsource (lib "瑞臻信息") (part "普通电阻"))
    )
    (comp (ref "R200")
      (value "10K")
      (footprint "r0402")
      (description "普通电阻")
      (libsource (lib "瑞臻信息") (part "普通电阻"))
    )
    (comp (ref "R201")
      (value "10K")
      (footprint "r0402")
      (description "普通电阻")
      (libsource (lib "瑞臻信息") (part "普通电阻"))
    )
    (comp (ref "R202")
      (value "10K")
      (footprint "r0402")
      (description "普通电阻")
      (libsource (lib "瑞臻信息") (part "普通电阻"))
    )
    (comp (ref "R203")
      (value "10K")
      (footprint "r0402")
      (description "普通电阻")
      (libsource (lib "瑞臻信息") (part "普通电阻"))
    )
    (comp (ref "R204")
      (value "10K")
      (footprint "r0402")
      (description "普通电阻")
      (libsource (lib "瑞臻信息") (part "普通电阻"))
    )
    (comp (ref "R205")
      (value "10K")
      (footprint "r0402")
      (description "普通电阻")
      (libsource (lib "瑞臻信息") (part "普通电阻"))
    )
    (comp (ref "R206")
      (value "10K")
      (footprint "r0402")
      (description "普通电阻")
      (libsource (lib "瑞臻信息") (part "普通电阻"))
    )
    (comp (ref "R207")
      (value "10K")
      (footprint "r0402")
      (description "普通电阻")
      (libsource (lib "瑞臻信息") (part "普通电阻"))
    )
    (comp (ref "R208")
      (value "10K")
      (footprint "r0402")
      (description "普通电阻")
      (libsource (lib "瑞臻信息") (part "普通电阻"))
    )
    (comp (ref "R209")
      (value "10K")
      (footprint "r0402")
      (description "普通电阻")
      (libsource (lib "瑞臻信息") (part "普通电阻"))
    )
    (comp (ref "U8")
      (value "~")
      (footprint "TSSOP_16P_0R65_4R4X5R0")
      (libsource (lib "瑞臻信息") (part "74HC4051"))
    )
    (comp (ref "U9")
      (value "~")
      (footprint "TSSOP_16P_0R65_4R4X5R0")
      (libsource (lib "瑞臻信息") (part "74HC4051"))
    )
    (comp (ref "U10")
      (value "~")
      (footprint "TSSOP_16P_0R65_4R4X5R0")
      (libsource (lib "瑞臻信息") (part "74HC4051"))
    )
    (comp (ref "U11")
      (value "~")
      (footprint "TSSOP_16P_0R65_4R4X5R0")
      (libsource (lib "瑞臻信息") (part "74HC4051"))
    )
    (comp (ref "U12")
      (value "~")
      (footprint "TSSOP_16P_0R65_4R4X5R0")
      (libsource (lib "瑞臻信息") (part "74HC4051"))
    )
    (comp (ref "U13")
      (value "~")
      (footprint "TSSOP_16P_0R65_4R4X5R0")
      (libsource (lib "瑞臻信息") (part "74HC4051"))
    )
    (comp (ref "U14")
      (value "~")
      (footprint "TSSOP_16P_0R65_4R4X5R0")
      (libsource (lib "瑞臻信息") (part "74HC4051"))
    )
    (comp (ref "U15")
      (value "~")
      (footprint "TSSOP_16P_0R65_4R4X5R0")
      (libsource (lib "瑞臻信息") (part "74HC4051"))
    )
    (comp (ref "U16")
      (value "~")
      (footprint "TSSOP_16P_0R65_4R4X5R0")
      (libsource (lib "瑞臻信息") (part "74HC4051"))
    )
    (comp (ref "U17")
      (value "~")
      (footprint "TSSOP_16P_0R65_4R4X5R0")
      (libsource (lib "瑞臻信息") (part "74HC4051"))
    )
    (comp (ref "U18")
      (value "~")
      (footprint "TSSOP_16P_0R65_4R4X5R0")
      (libsource (lib "瑞臻信息") (part "74HC4051"))
    )
    (comp (ref "U19")
      (value "~")
      (footprint "TSSOP_16P_0R65_4R4X5R0")
      (libsource (lib "瑞臻信息") (part "74HC4051"))
    )
    (comp (ref "U20")
      (value "~")
      (footprint "TSSOP_16P_0R65_4R4X5R0")
      (libsource (lib "瑞臻信息") (part "74HC4051"))
    )
    (comp (ref "U21")
      (value "~")
      (footprint "TSSOP_16P_0R65_4R4X5R0")
      (libsource (lib "瑞臻信息") (part "74HC4051"))
    )
    (comp (ref "U22")
      (value "~")
      (footprint "TSSOP_16P_0R65_4R4X5R0")
      (libsource (lib "瑞臻信息") (part "74HC4051"))
    )
    (comp (ref "U23")
      (value "~")
      (footprint "TSSOP_16P_0R65_4R4X5R0")
      (libsource (lib "瑞臻信息") (part "74HC4051"))
    )
    (comp (ref "U24")
      (value "~")
      (footprint "TSSOP_16P_0R65_4R4X5R0")
      (libsource (lib "瑞臻信息") (part "74HC4051"))
    )
    (comp (ref "U25")
      (value "~")
      (footprint "TSSOP_16P_0R65_4R4X5R0")
      (libsource (lib "瑞臻信息") (part "74HC4051"))
    )
    (comp (ref "U26")
      (value "~")
      (footprint "TSSOP_16P_0R65_4R4X5R0")
      (libsource (lib "瑞臻信息") (part "74HC4051"))
    )
    (comp (ref "U27")
      (value "~")
      (footprint "TSSOP_16P_0R65_4R4X5R0")
      (libsource (lib "瑞臻信息") (part "74HC4051"))
    )
    (comp (ref "U28")
      (value "~")
      (footprint "TSSOP_16P_0R65_4R4X5R0")
      (libsource (lib "瑞臻信息") (part "74HC4051"))
    )
    (comp (ref "U29")
      (value "~")
      (footprint "TSSOP_16P_0R65_4R4X5R0")
      (libsource (lib "瑞臻信息") (part "74HC4051"))
    )
    (comp (ref "U30")
      (value "~")
      (footprint "TSSOP_16P_0R65_4R4X5R0")
      (libsource (lib "瑞臻信息") (part "74HC4051"))
    )
    (comp (ref "U31")
      (value "~")
      (footprint "TSSOP_16P_0R65_4R4X5R0")
      (libsource (lib "瑞臻信息") (part "74HC4051"))
    )
    (comp (ref "U32")
      (value "~")
      (footprint "TSSOP_16P_0R65_4R4X5R0")
      (libsource (lib "瑞臻信息") (part "74HC4051"))
    )
    (comp (ref "U33")
      (value "~")
      (footprint "TSSOP_16P_0R65_4R4X5R0")
      (libsource (lib "瑞臻信息") (part "74HC4051"))
    )
    (comp (ref "U34")
      (value "~")
      (footprint "TSSOP_16P_0R65_4R4X5R0")
      (libsource (lib "瑞臻信息") (part "74HC4051"))
    )
    (comp (ref "U35")
      (value "~")
      (footprint "TSSOP_16P_0R65_4R4X5R0")
      (libsource (lib "瑞臻信息") (part "74HC4051"))
    )
    (comp (ref "U36")
      (value "~")
      (footprint "TSSOP_16P_0R65_4R4X5R0")
      (libsource (lib "瑞臻信息") (part "74HC4051"))
    )
    (comp (ref "U37")
      (value "~")
      (footprint "TSSOP_16P_0R65_4R4X5R0")
      (libsource (lib "瑞臻信息") (part "74HC4051"))
    )
    (comp (ref "U38")
      (value "~")
      (footprint "TSSOP_16P_0R65_4R4X5R0")
      (libsource (lib "瑞臻信息") (part "74HC4051"))
    )
    (comp (ref "U39")
      (value "~")
      (footprint "TSSOP_16P_0R65_4R4X5R0")
      (libsource (lib "瑞臻信息") (part "74HC4051"))
    )
    (comp (ref "U40")
      (value "~")
      (footprint "TSSOP_16P_0R65_4R4X5R0")
      (libsource (lib "瑞臻信息") (part "74HC4051"))
    )
    (comp (ref "U41")
      (value "~")
      (footprint "TSSOP_16P_0R65_4R4X5R0")
      (libsource (lib "瑞臻信息") (part "74HC4051"))
    )
    (comp (ref "U42")
      (value "~")
      (footprint "TSSOP_16P_0R65_4R4X5R0")
      (libsource (lib "瑞臻信息") (part "74HC4051"))
    )
    (comp (ref "U43")
      (value "~")
      (footprint "TSSOP_16P_0R65_4R4X5R0")
      (libsource (lib "瑞臻信息") (part "74HC4051"))
    )
    (comp (ref "U44")
      (value "~")
      (footprint "TSSOP_16P_0R65_4R4X5R0")
      (libsource (lib "瑞臻信息") (part "74HC4051"))
    )
    (comp (ref "U45")
      (value "~")
      (footprint "TSSOP_16P_0R65_4R4X5R0")
      (libsource (lib "瑞臻信息") (part "74HC4051"))
    )
    (comp (ref "U50")
      (value "1117-5V0")
      (footprint "SOT223_4P_2R3_3R7X6R7")
      (libsource (lib "瑞臻信息") (part "AMS1117"))
    )
    (comp (ref "U51")
      (value "ADS1115")
      (footprint "MSOP_10P_3R0X5R0_P")
      (libsource (lib "瑞臻信息") (part "ADS1115"))
    )
  )
  (nets
    (net (code "1") (name "/ADJ_0") (class "Default")
      (node (ref "R122") (pin "2") (pinfunction "2_2") (pintype "passive"))
      (node (ref "R123") (pin "1") (pinfunction "1_1") (pintype "passive"))
      (node (ref "U43") (pin "13") (pinfunction "Y0_13") (pintype "passive"))
    )
    (net (code "2") (name "/ADJ_1") (class "Default")
      (node (ref "R134") (pin "2") (pinfunction "2_2") (pintype "passive"))
      (node (ref "R135") (pin "1") (pinfunction "1_1") (pintype "passive"))
      (node (ref "U43") (pin "14") (pinfunction "Y1_14") (pintype "passive"))
    )
    (net (code "3") (name "/ADJ_2") (class "Default")
      (node (ref "R146") (pin "2") (pinfunction "2_2") (pintype "passive"))
      (node (ref "R147") (pin "1") (pinfunction "1_1") (pintype "passive"))
      (node (ref "U43") (pin "15") (pinfunction "Y2_15") (pintype "passive"))
    )
    (net (code "4") (name "/ADJ_3") (class "Default")
      (node (ref "R158") (pin "2") (pinfunction "2_2") (pintype "passive"))
      (node (ref "R159") (pin "1") (pinfunction "1_1") (pintype "passive"))
      (node (ref "U43") (pin "12") (pinfunction "Y3_12") (pintype "passive"))
    )
    (net (code "5") (name "/ADJ_4") (class "Default")
      (node (ref "R170") (pin "2") (pinfunction "2_2") (pintype "passive"))
      (node (ref "R171") (pin "1") (pinfunction "1_1") (pintype "passive"))
      (node (ref "U43") (pin "1") (pinfunction "Y4_1") (pintype "passive"))
    )
    (net (code "6") (name "/ADJ_5") (class "Default")
      (node (ref "R184") (pin "2") (pinfunction "2_2") (pintype "passive"))
      (node (ref "R185") (pin "1") (pinfunction "1_1") (pintype "passive"))
      (node (ref "U43") (pin "5") (pinfunction "Y5_5") (pintype "passive"))
    )
    (net (code "7") (name "/ADJ_6") (class "Default")
      (node (ref "R196") (pin "2") (pinfunction "2_2") (pintype "passive"))
      (node (ref "R197") (pin "1") (pinfunction "1_1") (pintype "passive"))
      (node (ref "U43") (pin "2") (pinfunction "Y6_2") (pintype "passive"))
    )
    (net (code "8") (name "/ADJ_7") (class "Default")
      (node (ref "R208") (pin "2") (pinfunction "2_2") (pintype "passive"))
      (node (ref "R209") (pin "1") (pinfunction "1_1") (pintype "passive"))
      (node (ref "U43") (pin "4") (pinfunction "Y7_4") (pintype "passive"))
    )
    (net (code "9") (name "/I_MA") (class "Default")
      (node (ref "U45") (pin "3") (pinfunction "Z_3") (pintype "passive"))
      (node (ref "U51") (pin "5") (pinfunction "AIN1_5") (pintype "passive"))
    )
    (net (code "10") (name "/I_UA") (class "Default")
      (node (ref "U44") (pin "3") (pinfunction "Z_3") (pintype "passive"))
      (node (ref "U51") (pin "4") (pinfunction "AIN0_4") (pintype "passive"))
    )
    (net (code "11") (name "/M0_ADC1") (class "Default")
      (node (ref "P16") (pin "17") (pinfunction "17_17") (pintype "passive"))
      (node (ref "R16") (pin "1") (pinfunction "1_1") (pintype "passive"))
    )
    (net (code "12") (name "/M0_ADC2") (class "Default")
      (node (ref "P16") (pin "18") (pinfunction "18_18") (pintype "passive"))
      (node (ref "R32") (pin "1") (pinfunction "1_1") (pintype "passive"))
    )
    (net (code "13") (name "/M0_ADC3") (class "Default")
      (node (ref "P16") (pin "19") (pinfunction "19_19") (pintype "passive"))
      (node (ref "R48") (pin "1") (pinfunction "1_1") (pintype "passive"))
    )
    (net (code "14") (name "/M0_ADC4") (class "Default")
      (node (ref "P16") (pin "20") (pinfunction "20_20") (pintype "passive"))
      (node (ref "R64") (pin "1") (pinfunction "1_1") (pintype "passive"))
    )
    (net (code "15") (name "/M0_ADC5") (class "Default")
      (node (ref "P16") (pin "21") (pinfunction "21_21") (pintype "passive"))
      (node (ref "R80") (pin "1") (pinfunction "1_1") (pintype "passive"))
    )
    (net (code "16") (name "/M0_ADC6") (class "Default")
      (node (ref "P16") (pin "22") (pinfunction "22_22") (pintype "passive"))
      (node (ref "R96") (pin "1") (pinfunction "1_1") (pintype "passive"))
    )
    (net (code "17") (name "/M0_FADC1") (class "Default")
      (node (ref "R16") (pin "2") (pinfunction "2_2") (pintype "passive"))
      (node (ref "R17") (pin "1") (pinfunction "1_1") (pintype "passive"))
      (node (ref "U32") (pin "13") (pinfunction "Y0_13") (pintype "passive"))
    )
    (net (code "18") (name "/M0_FADC2") (class "Default")
      (node (ref "R32") (pin "2") (pinfunction "2_2") (pintype "passive"))
      (node (ref "R33") (pin "1") (pinfunction "1_1") (pintype "passive"))
      (node (ref "U33") (pin "13") (pinfunction "Y0_13") (pintype "passive"))
    )
    (net (code "19") (name "/M0_FADC3") (class "Default")
      (node (ref "R48") (pin "2") (pinfunction "2_2") (pintype "passive"))
      (node (ref "R49") (pin "1") (pinfunction "1_1") (pintype "passive"))
      (node (ref "U34") (pin "13") (pinfunction "Y0_13") (pintype "passive"))
    )
    (net (code "20") (name "/M0_FADC4") (class "Default")
      (node (ref "R64") (pin "2") (pinfunction "2_2") (pintype "passive"))
      (node (ref "R65") (pin "1") (pinfunction "1_1") (pintype "passive"))
      (node (ref "U35") (pin "13") (pinfunction "Y0_13") (pintype "passive"))
    )
    (net (code "21") (name "/M0_FADC5") (class "Default")
      (node (ref "R80") (pin "2") (pinfunction "2_2") (pintype "passive"))
      (node (ref "R81") (pin "1") (pinfunction "1_1") (pintype "passive"))
      (node (ref "U36") (pin "13") (pinfunction "Y0_13") (pintype "passive"))
    )
    (net (code "22") (name "/M0_FADC6") (class "Default")
      (node (ref "R96") (pin "2") (pinfunction "2_2") (pintype "passive"))
      (node (ref "R97") (pin "1") (pinfunction "1_1") (pintype "passive"))
      (node (ref "U37") (pin "13") (pinfunction "Y0_13") (pintype "passive"))
    )
    (net (code "23") (name "/M0_GPIO0") (class "Default")
      (node (ref "P8") (pin "11") (pinfunction "11_11") (pintype "passive"))
      (node (ref "U8") (pin "13") (pinfunction "Y0_13") (pintype "passive"))
    )
    (net (code "24") (name "/M0_GPIO1") (class "Default")
      (node (ref "P8") (pin "12") (pinfunction "12_12") (pintype "passive"))
      (node (ref "U9") (pin "13") (pinfunction "Y0_13") (pintype "passive"))
    )
    (net (code "25") (name "/M0_GPIO2") (class "Default")
      (node (ref "P8") (pin "13") (pinfunction "13_13") (pintype "passive"))
      (node (ref "U10") (pin "13") (pinfunction "Y0_13") (pintype "passive"))
    )
    (net (code "26") (name "/M0_GPIO3") (class "Default")
      (node (ref "P8") (pin "14") (pinfunction "14_14") (pintype "passive"))
      (node (ref "U11") (pin "13") (pinfunction "Y0_13") (pintype "passive"))
    )
    (net (code "27") (name "/M0_GPIO4") (class "Default")
      (node (ref "P8") (pin "15") (pinfunction "15_15") (pintype "passive"))
      (node (ref "U12") (pin "13") (pinfunction "Y0_13") (pintype "passive"))
    )
    (net (code "28") (name "/M0_GPIO5") (class "Default")
      (node (ref "P8") (pin "16") (pinfunction "16_16") (pintype "passive"))
      (node (ref "U13") (pin "13") (pinfunction "Y0_13") (pintype "passive"))
    )
    (net (code "29") (name "/M0_GPIO6") (class "Default")
      (node (ref "P8") (pin "17") (pinfunction "17_17") (pintype "passive"))
      (node (ref "U14") (pin "13") (pinfunction "Y0_13") (pintype "passive"))
    )
    (net (code "30") (name "/M0_GPIO7") (class "Default")
      (node (ref "P8") (pin "18") (pinfunction "18_18") (pintype "passive"))
      (node (ref "U15") (pin "13") (pinfunction "Y0_13") (pintype "passive"))
    )
    (net (code "31") (name "/M0_GPIO8") (class "Default")
      (node (ref "P8") (pin "19") (pinfunction "19_19") (pintype "passive"))
      (node (ref "U16") (pin "13") (pinfunction "Y0_13") (pintype "passive"))
    )
    (net (code "32") (name "/M0_GPIO9") (class "Default")
      (node (ref "P8") (pin "20") (pinfunction "20_20") (pintype "passive"))
      (node (ref "U17") (pin "13") (pinfunction "Y0_13") (pintype "passive"))
    )
    (net (code "33") (name "/M0_GPIO10") (class "Default")
      (node (ref "P8") (pin "21") (pinfunction "21_21") (pintype "passive"))
      (node (ref "U18") (pin "13") (pinfunction "Y0_13") (pintype "passive"))
    )
    (net (code "34") (name "/M0_GPIO11") (class "Default")
      (node (ref "P8") (pin "22") (pinfunction "22_22") (pintype "passive"))
      (node (ref "U19") (pin "13") (pinfunction "Y0_13") (pintype "passive"))
    )
    (net (code "35") (name "/M0_GPIO12") (class "Default")
      (node (ref "P16") (pin "3") (pinfunction "3_3") (pintype "passive"))
      (node (ref "U20") (pin "13") (pinfunction "Y0_13") (pintype "passive"))
    )
    (net (code "36") (name "/M0_GPIO13") (class "Default")
      (node (ref "P16") (pin "4") (pinfunction "4_4") (pintype "passive"))
      (node (ref "U21") (pin "13") (pinfunction "Y0_13") (pintype "passive"))
    )
    (net (code "37") (name "/M0_GPIO14") (class "Default")
      (node (ref "P16") (pin "5") (pinfunction "5_5") (pintype "passive"))
      (node (ref "U22") (pin "13") (pinfunction "Y0_13") (pintype "passive"))
    )
    (net (code "38") (name "/M0_GPIO15") (class "Default")
      (node (ref "P16") (pin "6") (pinfunction "6_6") (pintype "passive"))
      (node (ref "U23") (pin "13") (pinfunction "Y0_13") (pintype "passive"))
    )
    (net (code "39") (name "/M0_I2C_SCL") (class "Default")
      (node (ref "P16") (pin "14") (pinfunction "14_14") (pintype "passive"))
      (node (ref "U31") (pin "13") (pinfunction "Y0_13") (pintype "passive"))
    )
    (net (code "40") (name "/M0_I2C_SDA") (class "Default")
      (node (ref "P16") (pin "13") (pinfunction "13_13") (pintype "passive"))
      (node (ref "U30") (pin "13") (pinfunction "Y0_13") (pintype "passive"))
    )
    (net (code "41") (name "/M0_SPI_CLK") (class "Default")
      (node (ref "P16") (pin "11") (pinfunction "11_11") (pintype "passive"))
      (node (ref "U28") (pin "13") (pinfunction "Y0_13") (pintype "passive"))
    )
    (net (code "42") (name "/M0_SPI_CS") (class "Default")
      (node (ref "P16") (pin "12") (pinfunction "12_12") (pintype "passive"))
      (node (ref "U29") (pin "13") (pinfunction "Y0_13") (pintype "passive"))
    )
    (net (code "43") (name "/M0_SPI_MISO") (class "Default")
      (node (ref "P16") (pin "9") (pinfunction "9_9") (pintype "passive"))
      (node (ref "U26") (pin "13") (pinfunction "Y0_13") (pintype "passive"))
    )
    (net (code "44") (name "/M0_SPI_MOSI") (class "Default")
      (node (ref "P16") (pin "10") (pinfunction "10_10") (pintype "passive"))
      (node (ref "U27") (pin "13") (pinfunction "Y0_13") (pintype "passive"))
    )
    (net (code "45") (name "/M0_UART_RX") (class "Default")
      (node (ref "P16") (pin "8") (pinfunction "8_8") (pintype "passive"))
      (node (ref "U25") (pin "13") (pinfunction "Y0_13") (pintype "passive"))
    )
    (net (code "46") (name "/M0_UART_TX") (class "Default")
      (node (ref "P16") (pin "7") (pinfunction "7_7") (pintype "passive"))
      (node (ref "U24") (pin "13") (pinfunction "Y0_13") (pintype "passive"))
    )
    (net (code "47") (name "/M1_ADC1") (class "Default")
      (node (ref "P17") (pin "17") (pinfunction "17_17") (pintype "passive"))
      (node (ref "R18") (pin "1") (pinfunction "1_1") (pintype "passive"))
    )
    (net (code "48") (name "/M1_ADC2") (class "Default")
      (node (ref "P17") (pin "18") (pinfunction "18_18") (pintype "passive"))
      (node (ref "R34") (pin "1") (pinfunction "1_1") (pintype "passive"))
    )
    (net (code "49") (name "/M1_ADC3") (class "Default")
      (node (ref "P17") (pin "19") (pinfunction "19_19") (pintype "passive"))
      (node (ref "R50") (pin "1") (pinfunction "1_1") (pintype "passive"))
    )
    (net (code "50") (name "/M1_ADC4") (class "Default")
      (node (ref "P17") (pin "20") (pinfunction "20_20") (pintype "passive"))
      (node (ref "R66") (pin "1") (pinfunction "1_1") (pintype "passive"))
    )
    (net (code "51") (name "/M1_ADC5") (class "Default")
      (node (ref "P17") (pin "21") (pinfunction "21_21") (pintype "passive"))
      (node (ref "R82") (pin "1") (pinfunction "1_1") (pintype "passive"))
    )
    (net (code "52") (name "/M1_ADC6") (class "Default")
      (node (ref "P17") (pin "22") (pinfunction "22_22") (pintype "passive"))
      (node (ref "R98") (pin "1") (pinfunction "1_1") (pintype "passive"))
    )
    (net (code "53") (name "/M1_FADC1") (class "Default")
      (node (ref "R18") (pin "2") (pinfunction "2_2") (pintype "passive"))
      (node (ref "R19") (pin "1") (pinfunction "1_1") (pintype "passive"))
      (node (ref "U32") (pin "14") (pinfunction "Y1_14") (pintype "passive"))
    )
    (net (code "54") (name "/M1_FADC2") (class "Default")
      (node (ref "R34") (pin "2") (pinfunction "2_2") (pintype "passive"))
      (node (ref "R35") (pin "1") (pinfunction "1_1") (pintype "passive"))
      (node (ref "U33") (pin "14") (pinfunction "Y1_14") (pintype "passive"))
    )
    (net (code "55") (name "/M1_FADC3") (class "Default")
      (node (ref "R50") (pin "2") (pinfunction "2_2") (pintype "passive"))
      (node (ref "R51") (pin "1") (pinfunction "1_1") (pintype "passive"))
      (node (ref "U34") (pin "14") (pinfunction "Y1_14") (pintype "passive"))
    )
    (net (code "56") (name "/M1_FADC4") (class "Default")
      (node (ref "R66") (pin "2") (pinfunction "2_2") (pintype "passive"))
      (node (ref "R67") (pin "1") (pinfunction "1_1") (pintype "passive"))
      (node (ref "U35") (pin "14") (pinfunction "Y1_14") (pintype "passive"))
    )
    (net (code "57") (name "/M1_FADC5") (class "Default")
      (node (ref "R82") (pin "2") (pinfunction "2_2") (pintype "passive"))
      (node (ref "R83") (pin "1") (pinfunction "1_1") (pintype "passive"))
      (node (ref "U36") (pin "14") (pinfunction "Y1_14") (pintype "passive"))
    )
    (net (code "58") (name "/M1_FADC6") (class "Default")
      (node (ref "R98") (pin "2") (pinfunction "2_2") (pintype "passive"))
      (node (ref "R99") (pin "1") (pinfunction "1_1") (pintype "passive"))
      (node (ref "U37") (pin "14") (pinfunction "Y1_14") (pintype "passive"))
    )
    (net (code "59") (name "/M1_GPIO0") (class "Default")
      (node (ref "P9") (pin "11") (pinfunction "11_11") (pintype "passive"))
      (node (ref "U8") (pin "14") (pinfunction "Y1_14") (pintype "passive"))
    )
    (net (code "60") (name "/M1_GPIO1") (class "Default")
      (node (ref "P9") (pin "12") (pinfunction "12_12") (pintype "passive"))
      (node (ref "U9") (pin "14") (pinfunction "Y1_14") (pintype "passive"))
    )
    (net (code "61") (name "/M1_GPIO2") (class "Default")
      (node (ref "P9") (pin "13") (pinfunction "13_13") (pintype "passive"))
      (node (ref "U10") (pin "14") (pinfunction "Y1_14") (pintype "passive"))
    )
    (net (code "62") (name "/M1_GPIO3") (class "Default")
      (node (ref "P9") (pin "14") (pinfunction "14_14") (pintype "passive"))
      (node (ref "U11") (pin "14") (pinfunction "Y1_14") (pintype "passive"))
    )
    (net (code "63") (name "/M1_GPIO4") (class "Default")
      (node (ref "P9") (pin "15") (pinfunction "15_15") (pintype "passive"))
      (node (ref "U12") (pin "14") (pinfunction "Y1_14") (pintype "passive"))
    )
    (net (code "64") (name "/M1_GPIO5") (class "Default")
      (node (ref "P9") (pin "16") (pinfunction "16_16") (pintype "passive"))
      (node (ref "U13") (pin "14") (pinfunction "Y1_14") (pintype "passive"))
    )
    (net (code "65") (name "/M1_GPIO6") (class "Default")
      (node (ref "P9") (pin "17") (pinfunction "17_17") (pintype "passive"))
      (node (ref "U14") (pin "14") (pinfunction "Y1_14") (pintype "passive"))
    )
    (net (code "66") (name "/M1_GPIO7") (class "Default")
      (node (ref "P9") (pin "18") (pinfunction "18_18") (pintype "passive"))
      (node (ref "U15") (pin "14") (pinfunction "Y1_14") (pintype "passive"))
    )
    (net (code "67") (name "/M1_GPIO8") (class "Default")
      (node (ref "P9") (pin "19") (pinfunction "19_19") (pintype "passive"))
      (node (ref "U16") (pin "14") (pinfunction "Y1_14") (pintype "passive"))
    )
    (net (code "68") (name "/M1_GPIO9") (class "Default")
      (node (ref "P9") (pin "20") (pinfunction "20_20") (pintype "passive"))
      (node (ref "U17") (pin "14") (pinfunction "Y1_14") (pintype "passive"))
    )
    (net (code "69") (name "/M1_GPIO10") (class "Default")
      (node (ref "P9") (pin "21") (pinfunction "21_21") (pintype "passive"))
      (node (ref "U18") (pin "14") (pinfunction "Y1_14") (pintype "passive"))
    )
    (net (code "70") (name "/M1_GPIO11") (class "Default")
      (node (ref "P9") (pin "22") (pinfunction "22_22") (pintype "passive"))
      (node (ref "U19") (pin "14") (pinfunction "Y1_14") (pintype "passive"))
    )
    (net (code "71") (name "/M1_GPIO12") (class "Default")
      (node (ref "P17") (pin "3") (pinfunction "3_3") (pintype "passive"))
      (node (ref "U20") (pin "14") (pinfunction "Y1_14") (pintype "passive"))
    )
    (net (code "72") (name "/M1_GPIO13") (class "Default")
      (node (ref "P17") (pin "4") (pinfunction "4_4") (pintype "passive"))
      (node (ref "U21") (pin "14") (pinfunction "Y1_14") (pintype "passive"))
    )
    (net (code "73") (name "/M1_GPIO14") (class "Default")
      (node (ref "P17") (pin "5") (pinfunction "5_5") (pintype "passive"))
      (node (ref "U22") (pin "14") (pinfunction "Y1_14") (pintype "passive"))
    )
    (net (code "74") (name "/M1_GPIO15") (class "Default")
      (node (ref "P17") (pin "6") (pinfunction "6_6") (pintype "passive"))
      (node (ref "U23") (pin "14") (pinfunction "Y1_14") (pintype "passive"))
    )
    (net (code "75") (name "/M1_I2C_SCL") (class "Default")
      (node (ref "P17") (pin "14") (pinfunction "14_14") (pintype "passive"))
      (node (ref "U31") (pin "14") (pinfunction "Y1_14") (pintype "passive"))
    )
    (net (code "76") (name "/M1_I2C_SDA") (class "Default")
      (node (ref "P17") (pin "13") (pinfunction "13_13") (pintype "passive"))
      (node (ref "U30") (pin "14") (pinfunction "Y1_14") (pintype "passive"))
    )
    (net (code "77") (name "/M1_SPI_CLK") (class "Default")
      (node (ref "P17") (pin "11") (pinfunction "11_11") (pintype "passive"))
      (node (ref "U28") (pin "14") (pinfunction "Y1_14") (pintype "passive"))
    )
    (net (code "78") (name "/M1_SPI_CS") (class "Default")
      (node (ref "P17") (pin "12") (pinfunction "12_12") (pintype "passive"))
      (node (ref "U29") (pin "14") (pinfunction "Y1_14") (pintype "passive"))
    )
    (net (code "79") (name "/M1_SPI_MISO") (class "Default")
      (node (ref "P17") (pin "9") (pinfunction "9_9") (pintype "passive"))
      (node (ref "U26") (pin "14") (pinfunction "Y1_14") (pintype "passive"))
    )
    (net (code "80") (name "/M1_SPI_MOSI") (class "Default")
      (node (ref "P17") (pin "10") (pinfunction "10_10") (pintype "passive"))
      (node (ref "U27") (pin "14") (pinfunction "Y1_14") (pintype "passive"))
    )
    (net (code "81") (name "/M1_UART_RX") (class "Default")
      (node (ref "P17") (pin "8") (pinfunction "8_8") (pintype "passive"))
      (node (ref "U25") (pin "14") (pinfunction "Y1_14") (pintype "passive"))
    )
    (net (code "82") (name "/M1_UART_TX") (class "Default")
      (node (ref "P17") (pin "7") (pinfunction "7_7") (pintype "passive"))
      (node (ref "U24") (pin "14") (pinfunction "Y1_14") (pintype "passive"))
    )
    (net (code "83") (name "/M2_ADC1") (class "Default")
      (node (ref "P18") (pin "17") (pinfunction "17_17") (pintype "passive"))
      (node (ref "R20") (pin "1") (pinfunction "1_1") (pintype "passive"))
    )
    (net (code "84") (name "/M2_ADC2") (class "Default")
      (node (ref "P18") (pin "18") (pinfunction "18_18") (pintype "passive"))
      (node (ref "R36") (pin "1") (pinfunction "1_1") (pintype "passive"))
    )
    (net (code "85") (name "/M2_ADC3") (class "Default")
      (node (ref "P18") (pin "19") (pinfunction "19_19") (pintype "passive"))
      (node (ref "R52") (pin "1") (pinfunction "1_1") (pintype "passive"))
    )
    (net (code "86") (name "/M2_ADC4") (class "Default")
      (node (ref "P18") (pin "20") (pinfunction "20_20") (pintype "passive"))
      (node (ref "R68") (pin "1") (pinfunction "1_1") (pintype "passive"))
    )
    (net (code "87") (name "/M2_ADC5") (class "Default")
      (node (ref "P18") (pin "21") (pinfunction "21_21") (pintype "passive"))
      (node (ref "R84") (pin "1") (pinfunction "1_1") (pintype "passive"))
    )
    (net (code "88") (name "/M2_ADC6") (class "Default")
      (node (ref "P18") (pin "22") (pinfunction "22_22") (pintype "passive"))
      (node (ref "R100") (pin "1") (pinfunction "1_1") (pintype "passive"))
    )
    (net (code "89") (name "/M2_FADC1") (class "Default")
      (node (ref "R20") (pin "2") (pinfunction "2_2") (pintype "passive"))
      (node (ref "R21") (pin "1") (pinfunction "1_1") (pintype "passive"))
      (node (ref "U32") (pin "15") (pinfunction "Y2_15") (pintype "passive"))
    )
    (net (code "90") (name "/M2_FADC2") (class "Default")
      (node (ref "R36") (pin "2") (pinfunction "2_2") (pintype "passive"))
      (node (ref "R37") (pin "1") (pinfunction "1_1") (pintype "passive"))
      (node (ref "U33") (pin "15") (pinfunction "Y2_15") (pintype "passive"))
    )
    (net (code "91") (name "/M2_FADC3") (class "Default")
      (node (ref "R52") (pin "2") (pinfunction "2_2") (pintype "passive"))
      (node (ref "R53") (pin "1") (pinfunction "1_1") (pintype "passive"))
      (node (ref "U34") (pin "15") (pinfunction "Y2_15") (pintype "passive"))
    )
    (net (code "92") (name "/M2_FADC4") (class "Default")
      (node (ref "R68") (pin "2") (pinfunction "2_2") (pintype "passive"))
      (node (ref "R69") (pin "1") (pinfunction "1_1") (pintype "passive"))
      (node (ref "U35") (pin "15") (pinfunction "Y2_15") (pintype "passive"))
    )
    (net (code "93") (name "/M2_FADC5") (class "Default")
      (node (ref "R84") (pin "2") (pinfunction "2_2") (pintype "passive"))
      (node (ref "R85") (pin "1") (pinfunction "1_1") (pintype "passive"))
      (node (ref "U36") (pin "15") (pinfunction "Y2_15") (pintype "passive"))
    )
    (net (code "94") (name "/M2_FADC6") (class "Default")
      (node (ref "R100") (pin "2") (pinfunction "2_2") (pintype "passive"))
      (node (ref "R101") (pin "1") (pinfunction "1_1") (pintype "passive"))
      (node (ref "U37") (pin "15") (pinfunction "Y2_15") (pintype "passive"))
    )
    (net (code "95") (name "/M2_GPIO0") (class "Default")
      (node (ref "P10") (pin "11") (pinfunction "11_11") (pintype "passive"))
      (node (ref "U8") (pin "15") (pinfunction "Y2_15") (pintype "passive"))
    )
    (net (code "96") (name "/M2_GPIO1") (class "Default")
      (node (ref "P10") (pin "12") (pinfunction "12_12") (pintype "passive"))
      (node (ref "U9") (pin "15") (pinfunction "Y2_15") (pintype "passive"))
    )
    (net (code "97") (name "/M2_GPIO2") (class "Default")
      (node (ref "P10") (pin "13") (pinfunction "13_13") (pintype "passive"))
      (node (ref "U10") (pin "15") (pinfunction "Y2_15") (pintype "passive"))
    )
    (net (code "98") (name "/M2_GPIO3") (class "Default")
      (node (ref "P10") (pin "14") (pinfunction "14_14") (pintype "passive"))
      (node (ref "U11") (pin "15") (pinfunction "Y2_15") (pintype "passive"))
    )
    (net (code "99") (name "/M2_GPIO4") (class "Default")
      (node (ref "P10") (pin "15") (pinfunction "15_15") (pintype "passive"))
      (node (ref "U12") (pin "15") (pinfunction "Y2_15") (pintype "passive"))
    )
    (net (code "100") (name "/M2_GPIO5") (class "Default")
      (node (ref "P10") (pin "16") (pinfunction "16_16") (pintype "passive"))
      (node (ref "U13") (pin "15") (pinfunction "Y2_15") (pintype "passive"))
    )
    (net (code "101") (name "/M2_GPIO6") (class "Default")
      (node (ref "P10") (pin "17") (pinfunction "17_17") (pintype "passive"))
      (node (ref "U14") (pin "15") (pinfunction "Y2_15") (pintype "passive"))
    )
    (net (code "102") (name "/M2_GPIO7") (class "Default")
      (node (ref "P10") (pin "18") (pinfunction "18_18") (pintype "passive"))
      (node (ref "U15") (pin "15") (pinfunction "Y2_15") (pintype "passive"))
    )
    (net (code "103") (name "/M2_GPIO8") (class "Default")
      (node (ref "P10") (pin "19") (pinfunction "19_19") (pintype "passive"))
      (node (ref "U16") (pin "15") (pinfunction "Y2_15") (pintype "passive"))
    )
    (net (code "104") (name "/M2_GPIO9") (class "Default")
      (node (ref "P10") (pin "20") (pinfunction "20_20") (pintype "passive"))
      (node (ref "U17") (pin "15") (pinfunction "Y2_15") (pintype "passive"))
    )
    (net (code "105") (name "/M2_GPIO10") (class "Default")
      (node (ref "P10") (pin "21") (pinfunction "21_21") (pintype "passive"))
      (node (ref "U18") (pin "15") (pinfunction "Y2_15") (pintype "passive"))
    )
    (net (code "106") (name "/M2_GPIO11") (class "Default")
      (node (ref "P10") (pin "22") (pinfunction "22_22") (pintype "passive"))
      (node (ref "U19") (pin "15") (pinfunction "Y2_15") (pintype "passive"))
    )
    (net (code "107") (name "/M2_GPIO12") (class "Default")
      (node (ref "P18") (pin "3") (pinfunction "3_3") (pintype "passive"))
      (node (ref "U20") (pin "15") (pinfunction "Y2_15") (pintype "passive"))
    )
    (net (code "108") (name "/M2_GPIO13") (class "Default")
      (node (ref "P18") (pin "4") (pinfunction "4_4") (pintype "passive"))
      (node (ref "U21") (pin "15") (pinfunction "Y2_15") (pintype "passive"))
    )
    (net (code "109") (name "/M2_GPIO14") (class "Default")
      (node (ref "P18") (pin "5") (pinfunction "5_5") (pintype "passive"))
      (node (ref "U22") (pin "15") (pinfunction "Y2_15") (pintype "passive"))
    )
    (net (code "110") (name "/M2_GPIO15") (class "Default")
      (node (ref "P18") (pin "6") (pinfunction "6_6") (pintype "passive"))
      (node (ref "U23") (pin "15") (pinfunction "Y2_15") (pintype "passive"))
    )
    (net (code "111") (name "/M2_I2C_SCL") (class "Default")
      (node (ref "P18") (pin "14") (pinfunction "14_14") (pintype "passive"))
      (node (ref "U31") (pin "15") (pinfunction "Y2_15") (pintype "passive"))
    )
    (net (code "112") (name "/M2_I2C_SDA") (class "Default")
      (node (ref "P18") (pin "13") (pinfunction "13_13") (pintype "passive"))
      (node (ref "U30") (pin "15") (pinfunction "Y2_15") (pintype "passive"))
    )
    (net (code "113") (name "/M2_SPI_CLK") (class "Default")
      (node (ref "P18") (pin "11") (pinfunction "11_11") (pintype "passive"))
      (node (ref "U28") (pin "15") (pinfunction "Y2_15") (pintype "passive"))
    )
    (net (code "114") (name "/M2_SPI_CS") (class "Default")
      (node (ref "P18") (pin "12") (pinfunction "12_12") (pintype "passive"))
      (node (ref "U29") (pin "15") (pinfunction "Y2_15") (pintype "passive"))
    )
    (net (code "115") (name "/M2_SPI_MISO") (class "Default")
      (node (ref "P18") (pin "9") (pinfunction "9_9") (pintype "passive"))
      (node (ref "U26") (pin "15") (pinfunction "Y2_15") (pintype "passive"))
    )
    (net (code "116") (name "/M2_SPI_MOSI") (class "Default")
      (node (ref "P18") (pin "10") (pinfunction "10_10") (pintype "passive"))
      (node (ref "U27") (pin "15") (pinfunction "Y2_15") (pintype "passive"))
    )
    (net (code "117") (name "/M2_UART_RX") (class "Default")
      (node (ref "P18") (pin "8") (pinfunction "8_8") (pintype "passive"))
      (node (ref "U25") (pin "15") (pinfunction "Y2_15") (pintype "passive"))
    )
    (net (code "118") (name "/M2_UART_TX") (class "Default")
      (node (ref "P18") (pin "7") (pinfunction "7_7") (pintype "passive"))
      (node (ref "U24") (pin "15") (pinfunction "Y2_15") (pintype "passive"))
    )
    (net (code "119") (name "/M3_ADC1") (class "Default")
      (node (ref "P19") (pin "17") (pinfunction "17_17") (pintype "passive"))
      (node (ref "R22") (pin "1") (pinfunction "1_1") (pintype "passive"))
    )
    (net (code "120") (name "/M3_ADC2") (class "Default")
      (node (ref "P19") (pin "18") (pinfunction "18_18") (pintype "passive"))
      (node (ref "R38") (pin "1") (pinfunction "1_1") (pintype "passive"))
    )
    (net (code "121") (name "/M3_ADC3") (class "Default")
      (node (ref "P19") (pin "19") (pinfunction "19_19") (pintype "passive"))
      (node (ref "R54") (pin "1") (pinfunction "1_1") (pintype "passive"))
    )
    (net (code "122") (name "/M3_ADC4") (class "Default")
      (node (ref "P19") (pin "20") (pinfunction "20_20") (pintype "passive"))
      (node (ref "R70") (pin "1") (pinfunction "1_1") (pintype "passive"))
    )
    (net (code "123") (name "/M3_ADC5") (class "Default")
      (node (ref "P19") (pin "21") (pinfunction "21_21") (pintype "passive"))
      (node (ref "R86") (pin "1") (pinfunction "1_1") (pintype "passive"))
    )
    (net (code "124") (name "/M3_ADC6") (class "Default")
      (node (ref "P19") (pin "22") (pinfunction "22_22") (pintype "passive"))
      (node (ref "R102") (pin "1") (pinfunction "1_1") (pintype "passive"))
    )
    (net (code "125") (name "/M3_FADC1") (class "Default")
      (node (ref "R22") (pin "2") (pinfunction "2_2") (pintype "passive"))
      (node (ref "R23") (pin "1") (pinfunction "1_1") (pintype "passive"))
      (node (ref "U32") (pin "12") (pinfunction "Y3_12") (pintype "passive"))
    )
    (net (code "126") (name "/M3_FADC2") (class "Default")
      (node (ref "R38") (pin "2") (pinfunction "2_2") (pintype "passive"))
      (node (ref "R39") (pin "1") (pinfunction "1_1") (pintype "passive"))
      (node (ref "U33") (pin "12") (pinfunction "Y3_12") (pintype "passive"))
    )
    (net (code "127") (name "/M3_FADC3") (class "Default")
      (node (ref "R54") (pin "2") (pinfunction "2_2") (pintype "passive"))
      (node (ref "R55") (pin "1") (pinfunction "1_1") (pintype "passive"))
      (node (ref "U34") (pin "12") (pinfunction "Y3_12") (pintype "passive"))
    )
    (net (code "128") (name "/M3_FADC4") (class "Default")
      (node (ref "R70") (pin "2") (pinfunction "2_2") (pintype "passive"))
      (node (ref "R71") (pin "1") (pinfunction "1_1") (pintype "passive"))
      (node (ref "U35") (pin "12") (pinfunction "Y3_12") (pintype "passive"))
    )
    (net (code "129") (name "/M3_FADC5") (class "Default")
      (node (ref "R86") (pin "2") (pinfunction "2_2") (pintype "passive"))
      (node (ref "R87") (pin "1") (pinfunction "1_1") (pintype "passive"))
      (node (ref "U36") (pin "12") (pinfunction "Y3_12") (pintype "passive"))
    )
    (net (code "130") (name "/M3_FADC6") (class "Default")
      (node (ref "R102") (pin "2") (pinfunction "2_2") (pintype "passive"))
      (node (ref "R103") (pin "1") (pinfunction "1_1") (pintype "passive"))
      (node (ref "U37") (pin "12") (pinfunction "Y3_12") (pintype "passive"))
    )
    (net (code "131") (name "/M3_GPIO0") (class "Default")
      (node (ref "P11") (pin "11") (pinfunction "11_11") (pintype "passive"))
      (node (ref "U8") (pin "12") (pinfunction "Y3_12") (pintype "passive"))
    )
    (net (code "132") (name "/M3_GPIO1") (class "Default")
      (node (ref "P11") (pin "12") (pinfunction "12_12") (pintype "passive"))
      (node (ref "U9") (pin "12") (pinfunction "Y3_12") (pintype "passive"))
    )
    (net (code "133") (name "/M3_GPIO2") (class "Default")
      (node (ref "P11") (pin "13") (pinfunction "13_13") (pintype "passive"))
      (node (ref "U10") (pin "12") (pinfunction "Y3_12") (pintype "passive"))
    )
    (net (code "134") (name "/M3_GPIO3") (class "Default")
      (node (ref "P11") (pin "14") (pinfunction "14_14") (pintype "passive"))
      (node (ref "U11") (pin "12") (pinfunction "Y3_12") (pintype "passive"))
    )
    (net (code "135") (name "/M3_GPIO4") (class "Default")
      (node (ref "P11") (pin "15") (pinfunction "15_15") (pintype "passive"))
      (node (ref "U12") (pin "12") (pinfunction "Y3_12") (pintype "passive"))
    )
    (net (code "136") (name "/M3_GPIO5") (class "Default")
      (node (ref "P11") (pin "16") (pinfunction "16_16") (pintype "passive"))
      (node (ref "U13") (pin "12") (pinfunction "Y3_12") (pintype "passive"))
    )
    (net (code "137") (name "/M3_GPIO6") (class "Default")
      (node (ref "P11") (pin "17") (pinfunction "17_17") (pintype "passive"))
      (node (ref "U14") (pin "12") (pinfunction "Y3_12") (pintype "passive"))
    )
    (net (code "138") (name "/M3_GPIO7") (class "Default")
      (node (ref "P11") (pin "18") (pinfunction "18_18") (pintype "passive"))
      (node (ref "U15") (pin "12") (pinfunction "Y3_12") (pintype "passive"))
    )
    (net (code "139") (name "/M3_GPIO8") (class "Default")
      (node (ref "P11") (pin "19") (pinfunction "19_19") (pintype "passive"))
      (node (ref "U16") (pin "12") (pinfunction "Y3_12") (pintype "passive"))
    )
    (net (code "140") (name "/M3_GPIO9") (class "Default")
      (node (ref "P11") (pin "20") (pinfunction "20_20") (pintype "passive"))
      (node (ref "U17") (pin "12") (pinfunction "Y3_12") (pintype "passive"))
    )
    (net (code "141") (name "/M3_GPIO10") (class "Default")
      (node (ref "P11") (pin "21") (pinfunction "21_21") (pintype "passive"))
      (node (ref "U18") (pin "12") (pinfunction "Y3_12") (pintype "passive"))
    )
    (net (code "142") (name "/M3_GPIO11") (class "Default")
      (node (ref "P11") (pin "22") (pinfunction "22_22") (pintype "passive"))
      (node (ref "U19") (pin "12") (pinfunction "Y3_12") (pintype "passive"))
    )
    (net (code "143") (name "/M3_GPIO12") (class "Default")
      (node (ref "P19") (pin "3") (pinfunction "3_3") (pintype "passive"))
      (node (ref "U20") (pin "12") (pinfunction "Y3_12") (pintype "passive"))
    )
    (net (code "144") (name "/M3_GPIO13") (class "Default")
      (node (ref "P19") (pin "4") (pinfunction "4_4") (pintype "passive"))
      (node (ref "U21") (pin "12") (pinfunction "Y3_12") (pintype "passive"))
    )
    (net (code "145") (name "/M3_GPIO14") (class "Default")
      (node (ref "P19") (pin "5") (pinfunction "5_5") (pintype "passive"))
      (node (ref "U22") (pin "12") (pinfunction "Y3_12") (pintype "passive"))
    )
    (net (code "146") (name "/M3_GPIO15") (class "Default")
      (node (ref "P19") (pin "6") (pinfunction "6_6") (pintype "passive"))
      (node (ref "U23") (pin "12") (pinfunction "Y3_12") (pintype "passive"))
    )
    (net (code "147") (name "/M3_I2C_SCL") (class "Default")
      (node (ref "P19") (pin "14") (pinfunction "14_14") (pintype "passive"))
      (node (ref "U31") (pin "12") (pinfunction "Y3_12") (pintype "passive"))
    )
    (net (code "148") (name "/M3_I2C_SDA") (class "Default")
      (node (ref "P19") (pin "13") (pinfunction "13_13") (pintype "passive"))
      (node (ref "U30") (pin "12") (pinfunction "Y3_12") (pintype "passive"))
    )
    (net (code "149") (name "/M3_SPI_CLK") (class "Default")
      (node (ref "P19") (pin "11") (pinfunction "11_11") (pintype "passive"))
      (node (ref "U28") (pin "12") (pinfunction "Y3_12") (pintype "passive"))
    )
    (net (code "150") (name "/M3_SPI_CS") (class "Default")
      (node (ref "P19") (pin "12") (pinfunction "12_12") (pintype "passive"))
      (node (ref "U29") (pin "12") (pinfunction "Y3_12") (pintype "passive"))
    )
    (net (code "151") (name "/M3_SPI_MISO") (class "Default")
      (node (ref "P19") (pin "9") (pinfunction "9_9") (pintype "passive"))
      (node (ref "U26") (pin "12") (pinfunction "Y3_12") (pintype "passive"))
    )
    (net (code "152") (name "/M3_SPI_MOSI") (class "Default")
      (node (ref "P19") (pin "10") (pinfunction "10_10") (pintype "passive"))
      (node (ref "U27") (pin "12") (pinfunction "Y3_12") (pintype "passive"))
    )
    (net (code "153") (name "/M3_UART_RX") (class "Default")
      (node (ref "P19") (pin "8") (pinfunction "8_8") (pintype "passive"))
      (node (ref "U25") (pin "12") (pinfunction "Y3_12") (pintype "passive"))
    )
    (net (code "154") (name "/M3_UART_TX") (class "Default")
      (node (ref "P19") (pin "7") (pinfunction "7_7") (pintype "passive"))
      (node (ref "U24") (pin "12") (pinfunction "Y3_12") (pintype "passive"))
    )
    (net (code "155") (name "/M4_ADC1") (class "Default")
      (node (ref "P20") (pin "17") (pinfunction "17_17") (pintype "passive"))
      (node (ref "R24") (pin "1") (pinfunction "1_1") (pintype "passive"))
    )
    (net (code "156") (name "/M4_ADC2") (class "Default")
      (node (ref "P20") (pin "18") (pinfunction "18_18") (pintype "passive"))
      (node (ref "R40") (pin "1") (pinfunction "1_1") (pintype "passive"))
    )
    (net (code "157") (name "/M4_ADC3") (class "Default")
      (node (ref "P20") (pin "19") (pinfunction "19_19") (pintype "passive"))
      (node (ref "R56") (pin "1") (pinfunction "1_1") (pintype "passive"))
    )
    (net (code "158") (name "/M4_ADC4") (class "Default")
      (node (ref "P20") (pin "20") (pinfunction "20_20") (pintype "passive"))
      (node (ref "R72") (pin "1") (pinfunction "1_1") (pintype "passive"))
    )
    (net (code "159") (name "/M4_ADC5") (class "Default")
      (node (ref "P20") (pin "21") (pinfunction "21_21") (pintype "passive"))
      (node (ref "R88") (pin "1") (pinfunction "1_1") (pintype "passive"))
    )
    (net (code "160") (name "/M4_ADC6") (class "Default")
      (node (ref "P20") (pin "22") (pinfunction "22_22") (pintype "passive"))
      (node (ref "R104") (pin "1") (pinfunction "1_1") (pintype "passive"))
    )
    (net (code "161") (name "/M4_FADC1") (class "Default")
      (node (ref "R24") (pin "2") (pinfunction "2_2") (pintype "passive"))
      (node (ref "R25") (pin "1") (pinfunction "1_1") (pintype "passive"))
      (node (ref "U32") (pin "1") (pinfunction "Y4_1") (pintype "passive"))
    )
    (net (code "162") (name "/M4_FADC2") (class "Default")
      (node (ref "R40") (pin "2") (pinfunction "2_2") (pintype "passive"))
      (node (ref "R41") (pin "1") (pinfunction "1_1") (pintype "passive"))
      (node (ref "U33") (pin "1") (pinfunction "Y4_1") (pintype "passive"))
    )
    (net (code "163") (name "/M4_FADC3") (class "Default")
      (node (ref "R56") (pin "2") (pinfunction "2_2") (pintype "passive"))
      (node (ref "R57") (pin "1") (pinfunction "1_1") (pintype "passive"))
      (node (ref "U34") (pin "1") (pinfunction "Y4_1") (pintype "passive"))
    )
    (net (code "164") (name "/M4_FADC4") (class "Default")
      (node (ref "R72") (pin "2") (pinfunction "2_2") (pintype "passive"))
      (node (ref "R73") (pin "1") (pinfunction "1_1") (pintype "passive"))
      (node (ref "U35") (pin "1") (pinfunction "Y4_1") (pintype "passive"))
    )
    (net (code "165") (name "/M4_FADC5") (class "Default")
      (node (ref "R88") (pin "2") (pinfunction "2_2") (pintype "passive"))
      (node (ref "R89") (pin "1") (pinfunction "1_1") (pintype "passive"))
      (node (ref "U36") (pin "1") (pinfunction "Y4_1") (pintype "passive"))
    )
    (net (code "166") (name "/M4_FADC6") (class "Default")
      (node (ref "R104") (pin "2") (pinfunction "2_2") (pintype "passive"))
      (node (ref "R105") (pin "1") (pinfunction "1_1") (pintype "passive"))
      (node (ref "U37") (pin "1") (pinfunction "Y4_1") (pintype "passive"))
    )
    (net (code "167") (name "/M4_GPIO0") (class "Default")
      (node (ref "P12") (pin "11") (pinfunction "11_11") (pintype "passive"))
      (node (ref "U8") (pin "1") (pinfunction "Y4_1") (pintype "passive"))
    )
    (net (code "168") (name "/M4_GPIO1") (class "Default")
      (node (ref "P12") (pin "12") (pinfunction "12_12") (pintype "passive"))
      (node (ref "U9") (pin "1") (pinfunction "Y4_1") (pintype "passive"))
    )
    (net (code "169") (name "/M4_GPIO2") (class "Default")
      (node (ref "P12") (pin "13") (pinfunction "13_13") (pintype "passive"))
      (node (ref "U10") (pin "1") (pinfunction "Y4_1") (pintype "passive"))
    )
    (net (code "170") (name "/M4_GPIO3") (class "Default")
      (node (ref "P12") (pin "14") (pinfunction "14_14") (pintype "passive"))
      (node (ref "U11") (pin "1") (pinfunction "Y4_1") (pintype "passive"))
    )
    (net (code "171") (name "/M4_GPIO4") (class "Default")
      (node (ref "P12") (pin "15") (pinfunction "15_15") (pintype "passive"))
      (node (ref "U12") (pin "1") (pinfunction "Y4_1") (pintype "passive"))
    )
    (net (code "172") (name "/M4_GPIO5") (class "Default")
      (node (ref "P12") (pin "16") (pinfunction "16_16") (pintype "passive"))
      (node (ref "U13") (pin "1") (pinfunction "Y4_1") (pintype "passive"))
    )
    (net (code "173") (name "/M4_GPIO6") (class "Default")
      (node (ref "P12") (pin "17") (pinfunction "17_17") (pintype "passive"))
      (node (ref "U14") (pin "1") (pinfunction "Y4_1") (pintype "passive"))
    )
    (net (code "174") (name "/M4_GPIO7") (class "Default")
      (node (ref "P12") (pin "18") (pinfunction "18_18") (pintype "passive"))
      (node (ref "U15") (pin "1") (pinfunction "Y4_1") (pintype "passive"))
    )
    (net (code "175") (name "/M4_GPIO8") (class "Default")
      (node (ref "P12") (pin "19") (pinfunction "19_19") (pintype "passive"))
      (node (ref "U16") (pin "1") (pinfunction "Y4_1") (pintype "passive"))
    )
    (net (code "176") (name "/M4_GPIO9") (class "Default")
      (node (ref "P12") (pin "20") (pinfunction "20_20") (pintype "passive"))
      (node (ref "U17") (pin "1") (pinfunction "Y4_1") (pintype "passive"))
    )
    (net (code "177") (name "/M4_GPIO10") (class "Default")
      (node (ref "P12") (pin "21") (pinfunction "21_21") (pintype "passive"))
      (node (ref "U18") (pin "1") (pinfunction "Y4_1") (pintype "passive"))
    )
    (net (code "178") (name "/M4_GPIO11") (class "Default")
      (node (ref "P12") (pin "22") (pinfunction "22_22") (pintype "passive"))
      (node (ref "U19") (pin "1") (pinfunction "Y4_1") (pintype "passive"))
    )
    (net (code "179") (name "/M4_GPIO12") (class "Default")
      (node (ref "P20") (pin "3") (pinfunction "3_3") (pintype "passive"))
      (node (ref "U20") (pin "1") (pinfunction "Y4_1") (pintype "passive"))
    )
    (net (code "180") (name "/M4_GPIO13") (class "Default")
      (node (ref "P20") (pin "4") (pinfunction "4_4") (pintype "passive"))
      (node (ref "U21") (pin "1") (pinfunction "Y4_1") (pintype "passive"))
    )
    (net (code "181") (name "/M4_GPIO14") (class "Default")
      (node (ref "P20") (pin "5") (pinfunction "5_5") (pintype "passive"))
      (node (ref "U22") (pin "1") (pinfunction "Y4_1") (pintype "passive"))
    )
    (net (code "182") (name "/M4_GPIO15") (class "Default")
      (node (ref "P20") (pin "6") (pinfunction "6_6") (pintype "passive"))
      (node (ref "U23") (pin "1") (pinfunction "Y4_1") (pintype "passive"))
    )
    (net (code "183") (name "/M4_I2C_SCL") (class "Default")
      (node (ref "P20") (pin "14") (pinfunction "14_14") (pintype "passive"))
      (node (ref "U31") (pin "1") (pinfunction "Y4_1") (pintype "passive"))
    )
    (net (code "184") (name "/M4_I2C_SDA") (class "Default")
      (node (ref "P20") (pin "13") (pinfunction "13_13") (pintype "passive"))
      (node (ref "U30") (pin "1") (pinfunction "Y4_1") (pintype "passive"))
    )
    (net (code "185") (name "/M4_SPI_CLK") (class "Default")
      (node (ref "P20") (pin "11") (pinfunction "11_11") (pintype "passive"))
      (node (ref "U28") (pin "1") (pinfunction "Y4_1") (pintype "passive"))
    )
    (net (code "186") (name "/M4_SPI_CS") (class "Default")
      (node (ref "P20") (pin "12") (pinfunction "12_12") (pintype "passive"))
      (node (ref "U29") (pin "1") (pinfunction "Y4_1") (pintype "passive"))
    )
    (net (code "187") (name "/M4_SPI_MISO") (class "Default")
      (node (ref "P20") (pin "9") (pinfunction "9_9") (pintype "passive"))
      (node (ref "U26") (pin "1") (pinfunction "Y4_1") (pintype "passive"))
    )
    (net (code "188") (name "/M4_SPI_MOSI") (class "Default")
      (node (ref "P20") (pin "10") (pinfunction "10_10") (pintype "passive"))
      (node (ref "U27") (pin "1") (pinfunction "Y4_1") (pintype "passive"))
    )
    (net (code "189") (name "/M4_UART_RX") (class "Default")
      (node (ref "P20") (pin "8") (pinfunction "8_8") (pintype "passive"))
      (node (ref "U25") (pin "1") (pinfunction "Y4_1") (pintype "passive"))
    )
    (net (code "190") (name "/M4_UART_TX") (class "Default")
      (node (ref "P20") (pin "7") (pinfunction "7_7") (pintype "passive"))
      (node (ref "U24") (pin "1") (pinfunction "Y4_1") (pintype "passive"))
    )
    (net (code "191") (name "/M5_ADC1") (class "Default")
      (node (ref "P21") (pin "17") (pinfunction "17_17") (pintype "passive"))
      (node (ref "R26") (pin "1") (pinfunction "1_1") (pintype "passive"))
    )
    (net (code "192") (name "/M5_ADC2") (class "Default")
      (node (ref "P21") (pin "18") (pinfunction "18_18") (pintype "passive"))
      (node (ref "R42") (pin "1") (pinfunction "1_1") (pintype "passive"))
    )
    (net (code "193") (name "/M5_ADC3") (class "Default")
      (node (ref "P21") (pin "19") (pinfunction "19_19") (pintype "passive"))
      (node (ref "R58") (pin "1") (pinfunction "1_1") (pintype "passive"))
    )
    (net (code "194") (name "/M5_ADC4") (class "Default")
      (node (ref "P21") (pin "20") (pinfunction "20_20") (pintype "passive"))
      (node (ref "R74") (pin "1") (pinfunction "1_1") (pintype "passive"))
    )
    (net (code "195") (name "/M5_ADC5") (class "Default")
      (node (ref "P21") (pin "21") (pinfunction "21_21") (pintype "passive"))
      (node (ref "R90") (pin "1") (pinfunction "1_1") (pintype "passive"))
    )
    (net (code "196") (name "/M5_ADC6") (class "Default")
      (node (ref "P21") (pin "22") (pinfunction "22_22") (pintype "passive"))
      (node (ref "R106") (pin "1") (pinfunction "1_1") (pintype "passive"))
    )
    (net (code "197") (name "/M5_FADC1") (class "Default")
      (node (ref "R26") (pin "2") (pinfunction "2_2") (pintype "passive"))
      (node (ref "R27") (pin "1") (pinfunction "1_1") (pintype "passive"))
      (node (ref "U32") (pin "5") (pinfunction "Y5_5") (pintype "passive"))
    )
    (net (code "198") (name "/M5_FADC2") (class "Default")
      (node (ref "R42") (pin "2") (pinfunction "2_2") (pintype "passive"))
      (node (ref "R43") (pin "1") (pinfunction "1_1") (pintype "passive"))
      (node (ref "U33") (pin "5") (pinfunction "Y5_5") (pintype "passive"))
    )
    (net (code "199") (name "/M5_FADC3") (class "Default")
      (node (ref "R58") (pin "2") (pinfunction "2_2") (pintype "passive"))
      (node (ref "R59") (pin "1") (pinfunction "1_1") (pintype "passive"))
      (node (ref "U34") (pin "5") (pinfunction "Y5_5") (pintype "passive"))
    )
    (net (code "200") (name "/M5_FADC4") (class "Default")
      (node (ref "R74") (pin "2") (pinfunction "2_2") (pintype "passive"))
      (node (ref "R75") (pin "1") (pinfunction "1_1") (pintype "passive"))
      (node (ref "U35") (pin "5") (pinfunction "Y5_5") (pintype "passive"))
    )
    (net (code "201") (name "/M5_FADC5") (class "Default")
      (node (ref "R90") (pin "2") (pinfunction "2_2") (pintype "passive"))
      (node (ref "R91") (pin "1") (pinfunction "1_1") (pintype "passive"))
      (node (ref "U36") (pin "5") (pinfunction "Y5_5") (pintype "passive"))
    )
    (net (code "202") (name "/M5_FADC6") (class "Default")
      (node (ref "R106") (pin "2") (pinfunction "2_2") (pintype "passive"))
      (node (ref "R107") (pin "1") (pinfunction "1_1") (pintype "passive"))
      (node (ref "U37") (pin "5") (pinfunction "Y5_5") (pintype "passive"))
    )
    (net (code "203") (name "/M5_GPIO0") (class "Default")
      (node (ref "P13") (pin "11") (pinfunction "11_11") (pintype "passive"))
      (node (ref "U8") (pin "5") (pinfunction "Y5_5") (pintype "passive"))
    )
    (net (code "204") (name "/M5_GPIO1") (class "Default")
      (node (ref "P13") (pin "12") (pinfunction "12_12") (pintype "passive"))
      (node (ref "U9") (pin "5") (pinfunction "Y5_5") (pintype "passive"))
    )
    (net (code "205") (name "/M5_GPIO2") (class "Default")
      (node (ref "P13") (pin "13") (pinfunction "13_13") (pintype "passive"))
      (node (ref "U10") (pin "5") (pinfunction "Y5_5") (pintype "passive"))
    )
    (net (code "206") (name "/M5_GPIO3") (class "Default")
      (node (ref "P13") (pin "14") (pinfunction "14_14") (pintype "passive"))
      (node (ref "U11") (pin "5") (pinfunction "Y5_5") (pintype "passive"))
    )
    (net (code "207") (name "/M5_GPIO4") (class "Default")
      (node (ref "P13") (pin "15") (pinfunction "15_15") (pintype "passive"))
      (node (ref "U12") (pin "5") (pinfunction "Y5_5") (pintype "passive"))
    )
    (net (code "208") (name "/M5_GPIO5") (class "Default")
      (node (ref "P13") (pin "16") (pinfunction "16_16") (pintype "passive"))
      (node (ref "U13") (pin "5") (pinfunction "Y5_5") (pintype "passive"))
    )
    (net (code "209") (name "/M5_GPIO6") (class "Default")
      (node (ref "P13") (pin "17") (pinfunction "17_17") (pintype "passive"))
      (node (ref "U14") (pin "5") (pinfunction "Y5_5") (pintype "passive"))
    )
    (net (code "210") (name "/M5_GPIO7") (class "Default")
      (node (ref "P13") (pin "18") (pinfunction "18_18") (pintype "passive"))
      (node (ref "U15") (pin "5") (pinfunction "Y5_5") (pintype "passive"))
    )
    (net (code "211") (name "/M5_GPIO8") (class "Default")
      (node (ref "P13") (pin "19") (pinfunction "19_19") (pintype "passive"))
      (node (ref "U16") (pin "5") (pinfunction "Y5_5") (pintype "passive"))
    )
    (net (code "212") (name "/M5_GPIO9") (class "Default")
      (node (ref "P13") (pin "20") (pinfunction "20_20") (pintype "passive"))
      (node (ref "U17") (pin "5") (pinfunction "Y5_5") (pintype "passive"))
    )
    (net (code "213") (name "/M5_GPIO10") (class "Default")
      (node (ref "P13") (pin "21") (pinfunction "21_21") (pintype "passive"))
      (node (ref "U18") (pin "5") (pinfunction "Y5_5") (pintype "passive"))
    )
    (net (code "214") (name "/M5_GPIO11") (class "Default")
      (node (ref "P13") (pin "22") (pinfunction "22_22") (pintype "passive"))
      (node (ref "U19") (pin "5") (pinfunction "Y5_5") (pintype "passive"))
    )
    (net (code "215") (name "/M5_GPIO12") (class "Default")
      (node (ref "P21") (pin "3") (pinfunction "3_3") (pintype "passive"))
      (node (ref "U20") (pin "5") (pinfunction "Y5_5") (pintype "passive"))
    )
    (net (code "216") (name "/M5_GPIO13") (class "Default")
      (node (ref "P21") (pin "4") (pinfunction "4_4") (pintype "passive"))
      (node (ref "U21") (pin "5") (pinfunction "Y5_5") (pintype "passive"))
    )
    (net (code "217") (name "/M5_GPIO14") (class "Default")
      (node (ref "P21") (pin "5") (pinfunction "5_5") (pintype "passive"))
      (node (ref "U22") (pin "5") (pinfunction "Y5_5") (pintype "passive"))
    )
    (net (code "218") (name "/M5_GPIO15") (class "Default")
      (node (ref "P21") (pin "6") (pinfunction "6_6") (pintype "passive"))
      (node (ref "U23") (pin "5") (pinfunction "Y5_5") (pintype "passive"))
    )
    (net (code "219") (name "/M5_I2C_SCL") (class "Default")
      (node (ref "P21") (pin "14") (pinfunction "14_14") (pintype "passive"))
      (node (ref "U31") (pin "5") (pinfunction "Y5_5") (pintype "passive"))
    )
    (net (code "220") (name "/M5_I2C_SDA") (class "Default")
      (node (ref "P21") (pin "13") (pinfunction "13_13") (pintype "passive"))
      (node (ref "U30") (pin "5") (pinfunction "Y5_5") (pintype "passive"))
    )
    (net (code "221") (name "/M5_SPI_CLK") (class "Default")
      (node (ref "P21") (pin "11") (pinfunction "11_11") (pintype "passive"))
      (node (ref "U28") (pin "5") (pinfunction "Y5_5") (pintype "passive"))
    )
    (net (code "222") (name "/M5_SPI_CS") (class "Default")
      (node (ref "P21") (pin "12") (pinfunction "12_12") (pintype "passive"))
      (node (ref "U29") (pin "5") (pinfunction "Y5_5") (pintype "passive"))
    )
    (net (code "223") (name "/M5_SPI_MISO") (class "Default")
      (node (ref "P21") (pin "9") (pinfunction "9_9") (pintype "passive"))
      (node (ref "U26") (pin "5") (pinfunction "Y5_5") (pintype "passive"))
    )
    (net (code "224") (name "/M5_SPI_MOSI") (class "Default")
      (node (ref "P21") (pin "10") (pinfunction "10_10") (pintype "passive"))
      (node (ref "U27") (pin "5") (pinfunction "Y5_5") (pintype "passive"))
    )
    (net (code "225") (name "/M5_UART_RX") (class "Default")
      (node (ref "P21") (pin "8") (pinfunction "8_8") (pintype "passive"))
      (node (ref "U25") (pin "5") (pinfunction "Y5_5") (pintype "passive"))
    )
    (net (code "226") (name "/M5_UART_TX") (class "Default")
      (node (ref "P21") (pin "7") (pinfunction "7_7") (pintype "passive"))
      (node (ref "U24") (pin "5") (pinfunction "Y5_5") (pintype "passive"))
    )
    (net (code "227") (name "/M6_ADC1") (class "Default")
      (node (ref "P22") (pin "17") (pinfunction "17_17") (pintype "passive"))
      (node (ref "R28") (pin "1") (pinfunction "1_1") (pintype "passive"))
    )
    (net (code "228") (name "/M6_ADC2") (class "Default")
      (node (ref "P22") (pin "18") (pinfunction "18_18") (pintype "passive"))
      (node (ref "R44") (pin "1") (pinfunction "1_1") (pintype "passive"))
    )
    (net (code "229") (name "/M6_ADC3") (class "Default")
      (node (ref "P22") (pin "19") (pinfunction "19_19") (pintype "passive"))
      (node (ref "R60") (pin "1") (pinfunction "1_1") (pintype "passive"))
    )
    (net (code "230") (name "/M6_ADC4") (class "Default")
      (node (ref "P22") (pin "20") (pinfunction "20_20") (pintype "passive"))
      (node (ref "R76") (pin "1") (pinfunction "1_1") (pintype "passive"))
    )
    (net (code "231") (name "/M6_ADC5") (class "Default")
      (node (ref "P22") (pin "21") (pinfunction "21_21") (pintype "passive"))
      (node (ref "R92") (pin "1") (pinfunction "1_1") (pintype "passive"))
    )
    (net (code "232") (name "/M6_ADC6") (class "Default")
      (node (ref "P22") (pin "22") (pinfunction "22_22") (pintype "passive"))
      (node (ref "R108") (pin "1") (pinfunction "1_1") (pintype "passive"))
    )
    (net (code "233") (name "/M6_FADC1") (class "Default")
      (node (ref "R28") (pin "2") (pinfunction "2_2") (pintype "passive"))
      (node (ref "R29") (pin "1") (pinfunction "1_1") (pintype "passive"))
      (node (ref "U32") (pin "2") (pinfunction "Y6_2") (pintype "passive"))
    )
    (net (code "234") (name "/M6_FADC2") (class "Default")
      (node (ref "R44") (pin "2") (pinfunction "2_2") (pintype "passive"))
      (node (ref "R45") (pin "1") (pinfunction "1_1") (pintype "passive"))
      (node (ref "U33") (pin "2") (pinfunction "Y6_2") (pintype "passive"))
    )
    (net (code "235") (name "/M6_FADC3") (class "Default")
      (node (ref "R60") (pin "2") (pinfunction "2_2") (pintype "passive"))
      (node (ref "R61") (pin "1") (pinfunction "1_1") (pintype "passive"))
      (node (ref "U34") (pin "2") (pinfunction "Y6_2") (pintype "passive"))
    )
    (net (code "236") (name "/M6_FADC4") (class "Default")
      (node (ref "R76") (pin "2") (pinfunction "2_2") (pintype "passive"))
      (node (ref "R77") (pin "1") (pinfunction "1_1") (pintype "passive"))
      (node (ref "U35") (pin "2") (pinfunction "Y6_2") (pintype "passive"))
    )
    (net (code "237") (name "/M6_FADC5") (class "Default")
      (node (ref "R92") (pin "2") (pinfunction "2_2") (pintype "passive"))
      (node (ref "R93") (pin "1") (pinfunction "1_1") (pintype "passive"))
      (node (ref "U36") (pin "2") (pinfunction "Y6_2") (pintype "passive"))
    )
    (net (code "238") (name "/M6_FADC6") (class "Default")
      (node (ref "R108") (pin "2") (pinfunction "2_2") (pintype "passive"))
      (node (ref "R109") (pin "1") (pinfunction "1_1") (pintype "passive"))
      (node (ref "U37") (pin "2") (pinfunction "Y6_2") (pintype "passive"))
    )
    (net (code "239") (name "/M6_GPIO0") (class "Default")
      (node (ref "P14") (pin "11") (pinfunction "11_11") (pintype "passive"))
      (node (ref "U8") (pin "2") (pinfunction "Y6_2") (pintype "passive"))
    )
    (net (code "240") (name "/M6_GPIO1") (class "Default")
      (node (ref "P14") (pin "12") (pinfunction "12_12") (pintype "passive"))
      (node (ref "U9") (pin "2") (pinfunction "Y6_2") (pintype "passive"))
    )
    (net (code "241") (name "/M6_GPIO2") (class "Default")
      (node (ref "P14") (pin "13") (pinfunction "13_13") (pintype "passive"))
      (node (ref "U10") (pin "2") (pinfunction "Y6_2") (pintype "passive"))
    )
    (net (code "242") (name "/M6_GPIO3") (class "Default")
      (node (ref "P14") (pin "14") (pinfunction "14_14") (pintype "passive"))
      (node (ref "U11") (pin "2") (pinfunction "Y6_2") (pintype "passive"))
    )
    (net (code "243") (name "/M6_GPIO4") (class "Default")
      (node (ref "P14") (pin "15") (pinfunction "15_15") (pintype "passive"))
      (node (ref "U12") (pin "2") (pinfunction "Y6_2") (pintype "passive"))
    )
    (net (code "244") (name "/M6_GPIO5") (class "Default")
      (node (ref "P14") (pin "16") (pinfunction "16_16") (pintype "passive"))
      (node (ref "U13") (pin "2") (pinfunction "Y6_2") (pintype "passive"))
    )
    (net (code "245") (name "/M6_GPIO6") (class "Default")
      (node (ref "P14") (pin "17") (pinfunction "17_17") (pintype "passive"))
      (node (ref "U14") (pin "2") (pinfunction "Y6_2") (pintype "passive"))
    )
    (net (code "246") (name "/M6_GPIO7") (class "Default")
      (node (ref "P14") (pin "18") (pinfunction "18_18") (pintype "passive"))
      (node (ref "U15") (pin "2") (pinfunction "Y6_2") (pintype "passive"))
    )
    (net (code "247") (name "/M6_GPIO8") (class "Default")
      (node (ref "P14") (pin "19") (pinfunction "19_19") (pintype "passive"))
      (node (ref "U16") (pin "2") (pinfunction "Y6_2") (pintype "passive"))
    )
    (net (code "248") (name "/M6_GPIO9") (class "Default")
      (node (ref "P14") (pin "20") (pinfunction "20_20") (pintype "passive"))
      (node (ref "U17") (pin "2") (pinfunction "Y6_2") (pintype "passive"))
    )
    (net (code "249") (name "/M6_GPIO10") (class "Default")
      (node (ref "P14") (pin "21") (pinfunction "21_21") (pintype "passive"))
      (node (ref "U18") (pin "2") (pinfunction "Y6_2") (pintype "passive"))
    )
    (net (code "250") (name "/M6_GPIO11") (class "Default")
      (node (ref "P14") (pin "22") (pinfunction "22_22") (pintype "passive"))
      (node (ref "U19") (pin "2") (pinfunction "Y6_2") (pintype "passive"))
    )
    (net (code "251") (name "/M6_GPIO12") (class "Default")
      (node (ref "P22") (pin "3") (pinfunction "3_3") (pintype "passive"))
      (node (ref "U20") (pin "2") (pinfunction "Y6_2") (pintype "passive"))
    )
    (net (code "252") (name "/M6_GPIO13") (class "Default")
      (node (ref "P22") (pin "4") (pinfunction "4_4") (pintype "passive"))
      (node (ref "U21") (pin "2") (pinfunction "Y6_2") (pintype "passive"))
    )
    (net (code "253") (name "/M6_GPIO14") (class "Default")
      (node (ref "P22") (pin "5") (pinfunction "5_5") (pintype "passive"))
      (node (ref "U22") (pin "2") (pinfunction "Y6_2") (pintype "passive"))
    )
    (net (code "254") (name "/M6_GPIO15") (class "Default")
      (node (ref "P22") (pin "6") (pinfunction "6_6") (pintype "passive"))
      (node (ref "U23") (pin "2") (pinfunction "Y6_2") (pintype "passive"))
    )
    (net (code "255") (name "/M6_I2C_SCL") (class "Default")
      (node (ref "P22") (pin "14") (pinfunction "14_14") (pintype "passive"))
      (node (ref "U31") (pin "2") (pinfunction "Y6_2") (pintype "passive"))
    )
    (net (code "256") (name "/M6_I2C_SDA") (class "Default")
      (node (ref "P22") (pin "13") (pinfunction "13_13") (pintype "passive"))
      (node (ref "U30") (pin "2") (pinfunction "Y6_2") (pintype "passive"))
    )
    (net (code "257") (name "/M6_SPI_CLK") (class "Default")
      (node (ref "P22") (pin "11") (pinfunction "11_11") (pintype "passive"))
      (node (ref "U28") (pin "2") (pinfunction "Y6_2") (pintype "passive"))
    )
    (net (code "258") (name "/M6_SPI_CS") (class "Default")
      (node (ref "P22") (pin "12") (pinfunction "12_12") (pintype "passive"))
      (node (ref "U29") (pin "2") (pinfunction "Y6_2") (pintype "passive"))
    )
    (net (code "259") (name "/M6_SPI_MISO") (class "Default")
      (node (ref "P22") (pin "9") (pinfunction "9_9") (pintype "passive"))
      (node (ref "U26") (pin "2") (pinfunction "Y6_2") (pintype "passive"))
    )
    (net (code "260") (name "/M6_SPI_MOSI") (class "Default")
      (node (ref "P22") (pin "10") (pinfunction "10_10") (pintype "passive"))
      (node (ref "U27") (pin "2") (pinfunction "Y6_2") (pintype "passive"))
    )
    (net (code "261") (name "/M6_UART_RX") (class "Default")
      (node (ref "P22") (pin "8") (pinfunction "8_8") (pintype "passive"))
      (node (ref "U25") (pin "2") (pinfunction "Y6_2") (pintype "passive"))
    )
    (net (code "262") (name "/M6_UART_TX") (class "Default")
      (node (ref "P22") (pin "7") (pinfunction "7_7") (pintype "passive"))
      (node (ref "U24") (pin "2") (pinfunction "Y6_2") (pintype "passive"))
    )
    (net (code "263") (name "/M7_ADC1") (class "Default")
      (node (ref "P23") (pin "17") (pinfunction "17_17") (pintype "passive"))
      (node (ref "R30") (pin "1") (pinfunction "1_1") (pintype "passive"))
    )
    (net (code "264") (name "/M7_ADC2") (class "Default")
      (node (ref "P23") (pin "18") (pinfunction "18_18") (pintype "passive"))
      (node (ref "R46") (pin "1") (pinfunction "1_1") (pintype "passive"))
    )
    (net (code "265") (name "/M7_ADC3") (class "Default")
      (node (ref "P23") (pin "19") (pinfunction "19_19") (pintype "passive"))
      (node (ref "R62") (pin "1") (pinfunction "1_1") (pintype "passive"))
    )
    (net (code "266") (name "/M7_ADC4") (class "Default")
      (node (ref "P23") (pin "20") (pinfunction "20_20") (pintype "passive"))
      (node (ref "R78") (pin "1") (pinfunction "1_1") (pintype "passive"))
    )
    (net (code "267") (name "/M7_ADC5") (class "Default")
      (node (ref "P23") (pin "21") (pinfunction "21_21") (pintype "passive"))
      (node (ref "R94") (pin "1") (pinfunction "1_1") (pintype "passive"))
    )
    (net (code "268") (name "/M7_ADC6") (class "Default")
      (node (ref "P23") (pin "22") (pinfunction "22_22") (pintype "passive"))
      (node (ref "R110") (pin "1") (pinfunction "1_1") (pintype "passive"))
    )
    (net (code "269") (name "/M7_FADC1") (class "Default")
      (node (ref "R30") (pin "2") (pinfunction "2_2") (pintype "passive"))
      (node (ref "R31") (pin "1") (pinfunction "1_1") (pintype "passive"))
      (node (ref "U32") (pin "4") (pinfunction "Y7_4") (pintype "passive"))
    )
    (net (code "270") (name "/M7_FADC2") (class "Default")
      (node (ref "R46") (pin "2") (pinfunction "2_2") (pintype "passive"))
      (node (ref "R47") (pin "1") (pinfunction "1_1") (pintype "passive"))
      (node (ref "U33") (pin "4") (pinfunction "Y7_4") (pintype "passive"))
    )
    (net (code "271") (name "/M7_FADC3") (class "Default")
      (node (ref "R62") (pin "2") (pinfunction "2_2") (pintype "passive"))
      (node (ref "R63") (pin "1") (pinfunction "1_1") (pintype "passive"))
      (node (ref "U34") (pin "4") (pinfunction "Y7_4") (pintype "passive"))
    )
    (net (code "272") (name "/M7_FADC4") (class "Default")
      (node (ref "R78") (pin "2") (pinfunction "2_2") (pintype "passive"))
      (node (ref "R79") (pin "1") (pinfunction "1_1") (pintype "passive"))
      (node (ref "U35") (pin "4") (pinfunction "Y7_4") (pintype "passive"))
    )
    (net (code "273") (name "/M7_FADC5") (class "Default")
      (node (ref "R94") (pin "2") (pinfunction "2_2") (pintype "passive"))
      (node (ref "R95") (pin "1") (pinfunction "1_1") (pintype "passive"))
      (node (ref "U36") (pin "4") (pinfunction "Y7_4") (pintype "passive"))
    )
    (net (code "274") (name "/M7_FADC6") (class "Default")
      (node (ref "R110") (pin "2") (pinfunction "2_2") (pintype "passive"))
      (node (ref "R111") (pin "1") (pinfunction "1_1") (pintype "passive"))
      (node (ref "U37") (pin "4") (pinfunction "Y7_4") (pintype "passive"))
    )
    (net (code "275") (name "/M7_GPIO0") (class "Default")
      (node (ref "P15") (pin "11") (pinfunction "11_11") (pintype "passive"))
      (node (ref "U8") (pin "4") (pinfunction "Y7_4") (pintype "passive"))
    )
    (net (code "276") (name "/M7_GPIO1") (class "Default")
      (node (ref "P15") (pin "12") (pinfunction "12_12") (pintype "passive"))
      (node (ref "U9") (pin "4") (pinfunction "Y7_4") (pintype "passive"))
    )
    (net (code "277") (name "/M7_GPIO2") (class "Default")
      (node (ref "P15") (pin "13") (pinfunction "13_13") (pintype "passive"))
      (node (ref "U10") (pin "4") (pinfunction "Y7_4") (pintype "passive"))
    )
    (net (code "278") (name "/M7_GPIO3") (class "Default")
      (node (ref "P15") (pin "14") (pinfunction "14_14") (pintype "passive"))
      (node (ref "U11") (pin "4") (pinfunction "Y7_4") (pintype "passive"))
    )
    (net (code "279") (name "/M7_GPIO4") (class "Default")
      (node (ref "P15") (pin "15") (pinfunction "15_15") (pintype "passive"))
      (node (ref "U12") (pin "4") (pinfunction "Y7_4") (pintype "passive"))
    )
    (net (code "280") (name "/M7_GPIO5") (class "Default")
      (node (ref "P15") (pin "16") (pinfunction "16_16") (pintype "passive"))
      (node (ref "U13") (pin "4") (pinfunction "Y7_4") (pintype "passive"))
    )
    (net (code "281") (name "/M7_GPIO6") (class "Default")
      (node (ref "P15") (pin "17") (pinfunction "17_17") (pintype "passive"))
      (node (ref "U14") (pin "4") (pinfunction "Y7_4") (pintype "passive"))
    )
    (net (code "282") (name "/M7_GPIO7") (class "Default")
      (node (ref "P15") (pin "18") (pinfunction "18_18") (pintype "passive"))
      (node (ref "U15") (pin "4") (pinfunction "Y7_4") (pintype "passive"))
    )
    (net (code "283") (name "/M7_GPIO8") (class "Default")
      (node (ref "P15") (pin "19") (pinfunction "19_19") (pintype "passive"))
      (node (ref "U16") (pin "4") (pinfunction "Y7_4") (pintype "passive"))
    )
    (net (code "284") (name "/M7_GPIO9") (class "Default")
      (node (ref "P15") (pin "20") (pinfunction "20_20") (pintype "passive"))
      (node (ref "U17") (pin "4") (pinfunction "Y7_4") (pintype "passive"))
    )
    (net (code "285") (name "/M7_GPIO10") (class "Default")
      (node (ref "P15") (pin "21") (pinfunction "21_21") (pintype "passive"))
      (node (ref "U18") (pin "4") (pinfunction "Y7_4") (pintype "passive"))
    )
    (net (code "286") (name "/M7_GPIO11") (class "Default")
      (node (ref "P15") (pin "22") (pinfunction "22_22") (pintype "passive"))
      (node (ref "U19") (pin "4") (pinfunction "Y7_4") (pintype "passive"))
    )
    (net (code "287") (name "/M7_GPIO12") (class "Default")
      (node (ref "P23") (pin "3") (pinfunction "3_3") (pintype "passive"))
      (node (ref "U20") (pin "4") (pinfunction "Y7_4") (pintype "passive"))
    )
    (net (code "288") (name "/M7_GPIO13") (class "Default")
      (node (ref "P23") (pin "4") (pinfunction "4_4") (pintype "passive"))
      (node (ref "U21") (pin "4") (pinfunction "Y7_4") (pintype "passive"))
    )
    (net (code "289") (name "/M7_GPIO14") (class "Default")
      (node (ref "P23") (pin "5") (pinfunction "5_5") (pintype "passive"))
      (node (ref "U22") (pin "4") (pinfunction "Y7_4") (pintype "passive"))
    )
    (net (code "290") (name "/M7_GPIO15") (class "Default")
      (node (ref "P23") (pin "6") (pinfunction "6_6") (pintype "passive"))
      (node (ref "U23") (pin "4") (pinfunction "Y7_4") (pintype "passive"))
    )
    (net (code "291") (name "/M7_I2C_SCL") (class "Default")
      (node (ref "P23") (pin "14") (pinfunction "14_14") (pintype "passive"))
      (node (ref "U31") (pin "4") (pinfunction "Y7_4") (pintype "passive"))
    )
    (net (code "292") (name "/M7_I2C_SDA") (class "Default")
      (node (ref "P23") (pin "13") (pinfunction "13_13") (pintype "passive"))
      (node (ref "U30") (pin "4") (pinfunction "Y7_4") (pintype "passive"))
    )
    (net (code "293") (name "/M7_SPI_CLK") (class "Default")
      (node (ref "P23") (pin "11") (pinfunction "11_11") (pintype "passive"))
      (node (ref "U28") (pin "4") (pinfunction "Y7_4") (pintype "passive"))
    )
    (net (code "294") (name "/M7_SPI_CS") (class "Default")
      (node (ref "P23") (pin "12") (pinfunction "12_12") (pintype "passive"))
      (node (ref "U29") (pin "4") (pinfunction "Y7_4") (pintype "passive"))
    )
    (net (code "295") (name "/M7_SPI_MISO") (class "Default")
      (node (ref "P23") (pin "9") (pinfunction "9_9") (pintype "passive"))
      (node (ref "U26") (pin "4") (pinfunction "Y7_4") (pintype "passive"))
    )
    (net (code "296") (name "/M7_SPI_MOSI") (class "Default")
      (node (ref "P23") (pin "10") (pinfunction "10_10") (pintype "passive"))
      (node (ref "U27") (pin "4") (pinfunction "Y7_4") (pintype "passive"))
    )
    (net (code "297") (name "/M7_UART_RX") (class "Default")
      (node (ref "P23") (pin "8") (pinfunction "8_8") (pintype "passive"))
      (node (ref "U25") (pin "4") (pinfunction "Y7_4") (pintype "passive"))
    )
    (net (code "298") (name "/M7_UART_TX") (class "Default")
      (node (ref "P23") (pin "7") (pinfunction "7_7") (pintype "passive"))
      (node (ref "U24") (pin "4") (pinfunction "Y7_4") (pintype "passive"))
    )
    (net (code "299") (name "/S1V8_0") (class "Default")
      (node (ref "R112") (pin "2") (pinfunction "2_2") (pintype "passive"))
      (node (ref "R113") (pin "1") (pinfunction "1_1") (pintype "passive"))
      (node (ref "U38") (pin "13") (pinfunction "Y0_13") (pintype "passive"))
    )
    (net (code "300") (name "/S1V8_1") (class "Default")
      (node (ref "R124") (pin "2") (pinfunction "2_2") (pintype "passive"))
      (node (ref "R125") (pin "1") (pinfunction "1_1") (pintype "passive"))
      (node (ref "U38") (pin "14") (pinfunction "Y1_14") (pintype "passive"))
    )
    (net (code "301") (name "/S1V8_2") (class "Default")
      (node (ref "R136") (pin "2") (pinfunction "2_2") (pintype "passive"))
      (node (ref "R137") (pin "1") (pinfunction "1_1") (pintype "passive"))
      (node (ref "U38") (pin "15") (pinfunction "Y2_15") (pintype "passive"))
    )
    (net (code "302") (name "/S1V8_3") (class "Default")
      (node (ref "R148") (pin "2") (pinfunction "2_2") (pintype "passive"))
      (node (ref "R149") (pin "1") (pinfunction "1_1") (pintype "passive"))
      (node (ref "U38") (pin "12") (pinfunction "Y3_12") (pintype "passive"))
    )
    (net (code "303") (name "/S1V8_4") (class "Default")
      (node (ref "R160") (pin "2") (pinfunction "2_2") (pintype "passive"))
      (node (ref "R161") (pin "1") (pinfunction "1_1") (pintype "passive"))
      (node (ref "U38") (pin "1") (pinfunction "Y4_1") (pintype "passive"))
    )
    (net (code "304") (name "/S1V8_5") (class "Default")
      (node (ref "R174") (pin "2") (pinfunction "2_2") (pintype "passive"))
      (node (ref "R175") (pin "1") (pinfunction "1_1") (pintype "passive"))
      (node (ref "U38") (pin "5") (pinfunction "Y5_5") (pintype "passive"))
    )
    (net (code "305") (name "/S1V8_6") (class "Default")
      (node (ref "R186") (pin "2") (pinfunction "2_2") (pintype "passive"))
      (node (ref "R187") (pin "1") (pinfunction "1_1") (pintype "passive"))
      (node (ref "U38") (pin "2") (pinfunction "Y6_2") (pintype "passive"))
    )
    (net (code "306") (name "/S1V8_7") (class "Default")
      (node (ref "R198") (pin "2") (pinfunction "2_2") (pintype "passive"))
      (node (ref "R199") (pin "1") (pinfunction "1_1") (pintype "passive"))
      (node (ref "U38") (pin "4") (pinfunction "Y7_4") (pintype "passive"))
    )
    (net (code "307") (name "/S2V5_0") (class "Default")
      (node (ref "R114") (pin "2") (pinfunction "2_2") (pintype "passive"))
      (node (ref "R115") (pin "1") (pinfunction "1_1") (pintype "passive"))
      (node (ref "U39") (pin "13") (pinfunction "Y0_13") (pintype "passive"))
    )
    (net (code "308") (name "/S2V5_1") (class "Default")
      (node (ref "R126") (pin "2") (pinfunction "2_2") (pintype "passive"))
      (node (ref "R127") (pin "1") (pinfunction "1_1") (pintype "passive"))
      (node (ref "U39") (pin "14") (pinfunction "Y1_14") (pintype "passive"))
    )
    (net (code "309") (name "/S2V5_2") (class "Default")
      (node (ref "R138") (pin "2") (pinfunction "2_2") (pintype "passive"))
      (node (ref "R139") (pin "1") (pinfunction "1_1") (pintype "passive"))
      (node (ref "U39") (pin "15") (pinfunction "Y2_15") (pintype "passive"))
    )
    (net (code "310") (name "/S2V5_3") (class "Default")
      (node (ref "R150") (pin "2") (pinfunction "2_2") (pintype "passive"))
      (node (ref "R151") (pin "1") (pinfunction "1_1") (pintype "passive"))
      (node (ref "U39") (pin "12") (pinfunction "Y3_12") (pintype "passive"))
    )
    (net (code "311") (name "/S2V5_4") (class "Default")
      (node (ref "R162") (pin "2") (pinfunction "2_2") (pintype "passive"))
      (node (ref "R163") (pin "1") (pinfunction "1_1") (pintype "passive"))
      (node (ref "U39") (pin "1") (pinfunction "Y4_1") (pintype "passive"))
    )
    (net (code "312") (name "/S2V5_5") (class "Default")
      (node (ref "R176") (pin "2") (pinfunction "2_2") (pintype "passive"))
      (node (ref "R177") (pin "1") (pinfunction "1_1") (pintype "passive"))
      (node (ref "U39") (pin "5") (pinfunction "Y5_5") (pintype "passive"))
    )
    (net (code "313") (name "/S2V5_6") (class "Default")
      (node (ref "R188") (pin "2") (pinfunction "2_2") (pintype "passive"))
      (node (ref "R189") (pin "1") (pinfunction "1_1") (pintype "passive"))
      (node (ref "U39") (pin "2") (pinfunction "Y6_2") (pintype "passive"))
    )
    (net (code "314") (name "/S2V5_7") (class "Default")
      (node (ref "R200") (pin "2") (pinfunction "2_2") (pintype "passive"))
      (node (ref "R201") (pin "1") (pinfunction "1_1") (pintype "passive"))
      (node (ref "U39") (pin "4") (pinfunction "Y7_4") (pintype "passive"))
    )
    (net (code "315") (name "/S3V0_0") (class "Default")
      (node (ref "R116") (pin "2") (pinfunction "2_2") (pintype "passive"))
      (node (ref "R117") (pin "1") (pinfunction "1_1") (pintype "passive"))
      (node (ref "U40") (pin "13") (pinfunction "Y0_13") (pintype "passive"))
    )
    (net (code "316") (name "/S3V0_1") (class "Default")
      (node (ref "R128") (pin "2") (pinfunction "2_2") (pintype "passive"))
      (node (ref "R129") (pin "1") (pinfunction "1_1") (pintype "passive"))
      (node (ref "U40") (pin "14") (pinfunction "Y1_14") (pintype "passive"))
    )
    (net (code "317") (name "/S3V0_2") (class "Default")
      (node (ref "R140") (pin "2") (pinfunction "2_2") (pintype "passive"))
      (node (ref "R141") (pin "1") (pinfunction "1_1") (pintype "passive"))
      (node (ref "U40") (pin "15") (pinfunction "Y2_15") (pintype "passive"))
    )
    (net (code "318") (name "/S3V0_3") (class "Default")
      (node (ref "R152") (pin "2") (pinfunction "2_2") (pintype "passive"))
      (node (ref "R153") (pin "1") (pinfunction "1_1") (pintype "passive"))
      (node (ref "U40") (pin "12") (pinfunction "Y3_12") (pintype "passive"))
    )
    (net (code "319") (name "/S3V0_4") (class "Default")
      (node (ref "R164") (pin "2") (pinfunction "2_2") (pintype "passive"))
      (node (ref "R165") (pin "1") (pinfunction "1_1") (pintype "passive"))
      (node (ref "U40") (pin "1") (pinfunction "Y4_1") (pintype "passive"))
    )
    (net (code "320") (name "/S3V0_5") (class "Default")
      (node (ref "R178") (pin "2") (pinfunction "2_2") (pintype "passive"))
      (node (ref "R179") (pin "1") (pinfunction "1_1") (pintype "passive"))
      (node (ref "U40") (pin "5") (pinfunction "Y5_5") (pintype "passive"))
    )
    (net (code "321") (name "/S3V0_6") (class "Default")
      (node (ref "R190") (pin "2") (pinfunction "2_2") (pintype "passive"))
      (node (ref "R191") (pin "1") (pinfunction "1_1") (pintype "passive"))
      (node (ref "U40") (pin "2") (pinfunction "Y6_2") (pintype "passive"))
    )
    (net (code "322") (name "/S3V0_7") (class "Default")
      (node (ref "R202") (pin "2") (pinfunction "2_2") (pintype "passive"))
      (node (ref "R203") (pin "1") (pinfunction "1_1") (pintype "passive"))
      (node (ref "U40") (pin "4") (pinfunction "Y7_4") (pintype "passive"))
    )
    (net (code "323") (name "/S3V3_0") (class "Default")
      (node (ref "R118") (pin "2") (pinfunction "2_2") (pintype "passive"))
      (node (ref "R119") (pin "1") (pinfunction "1_1") (pintype "passive"))
      (node (ref "U41") (pin "13") (pinfunction "Y0_13") (pintype "passive"))
    )
    (net (code "324") (name "/S3V3_1") (class "Default")
      (node (ref "R130") (pin "2") (pinfunction "2_2") (pintype "passive"))
      (node (ref "R131") (pin "1") (pinfunction "1_1") (pintype "passive"))
      (node (ref "U41") (pin "14") (pinfunction "Y1_14") (pintype "passive"))
    )
    (net (code "325") (name "/S3V3_2") (class "Default")
      (node (ref "R142") (pin "2") (pinfunction "2_2") (pintype "passive"))
      (node (ref "R143") (pin "1") (pinfunction "1_1") (pintype "passive"))
      (node (ref "U41") (pin "15") (pinfunction "Y2_15") (pintype "passive"))
    )
    (net (code "326") (name "/S3V3_3") (class "Default")
      (node (ref "R154") (pin "2") (pinfunction "2_2") (pintype "passive"))
      (node (ref "R155") (pin "1") (pinfunction "1_1") (pintype "passive"))
      (node (ref "U41") (pin "12") (pinfunction "Y3_12") (pintype "passive"))
    )
    (net (code "327") (name "/S3V3_4") (class "Default")
      (node (ref "R166") (pin "2") (pinfunction "2_2") (pintype "passive"))
      (node (ref "R167") (pin "1") (pinfunction "1_1") (pintype "passive"))
      (node (ref "U41") (pin "1") (pinfunction "Y4_1") (pintype "passive"))
    )
    (net (code "328") (name "/S3V3_5") (class "Default")
      (node (ref "R180") (pin "2") (pinfunction "2_2") (pintype "passive"))
      (node (ref "R181") (pin "1") (pinfunction "1_1") (pintype "passive"))
      (node (ref "U41") (pin "5") (pinfunction "Y5_5") (pintype "passive"))
    )
    (net (code "329") (name "/S3V3_6") (class "Default")
      (node (ref "R192") (pin "2") (pinfunction "2_2") (pintype "passive"))
      (node (ref "R193") (pin "1") (pinfunction "1_1") (pintype "passive"))
      (node (ref "U41") (pin "2") (pinfunction "Y6_2") (pintype "passive"))
    )
    (net (code "330") (name "/S3V3_7") (class "Default")
      (node (ref "R204") (pin "2") (pinfunction "2_2") (pintype "passive"))
      (node (ref "R205") (pin "1") (pinfunction "1_1") (pintype "passive"))
      (node (ref "U41") (pin "4") (pinfunction "Y7_4") (pintype "passive"))
    )
    (net (code "331") (name "/S5V0_0") (class "Default")
      (node (ref "R120") (pin "2") (pinfunction "2_2") (pintype "passive"))
      (node (ref "R121") (pin "1") (pinfunction "1_1") (pintype "passive"))
      (node (ref "U42") (pin "13") (pinfunction "Y0_13") (pintype "passive"))
    )
    (net (code "332") (name "/S5V0_1") (class "Default")
      (node (ref "R132") (pin "2") (pinfunction "2_2") (pintype "passive"))
      (node (ref "R133") (pin "1") (pinfunction "1_1") (pintype "passive"))
      (node (ref "U42") (pin "14") (pinfunction "Y1_14") (pintype "passive"))
    )
    (net (code "333") (name "/S5V0_2") (class "Default")
      (node (ref "R144") (pin "2") (pinfunction "2_2") (pintype "passive"))
      (node (ref "R145") (pin "1") (pinfunction "1_1") (pintype "passive"))
      (node (ref "U42") (pin "15") (pinfunction "Y2_15") (pintype "passive"))
    )
    (net (code "334") (name "/S5V0_3") (class "Default")
      (node (ref "R156") (pin "2") (pinfunction "2_2") (pintype "passive"))
      (node (ref "R157") (pin "1") (pinfunction "1_1") (pintype "passive"))
      (node (ref "U42") (pin "12") (pinfunction "Y3_12") (pintype "passive"))
    )
    (net (code "335") (name "/S5V0_4") (class "Default")
      (node (ref "R168") (pin "2") (pinfunction "2_2") (pintype "passive"))
      (node (ref "R169") (pin "1") (pinfunction "1_1") (pintype "passive"))
      (node (ref "U42") (pin "1") (pinfunction "Y4_1") (pintype "passive"))
    )
    (net (code "336") (name "/S5V0_5") (class "Default")
      (node (ref "R182") (pin "2") (pinfunction "2_2") (pintype "passive"))
      (node (ref "R183") (pin "1") (pinfunction "1_1") (pintype "passive"))
      (node (ref "U42") (pin "5") (pinfunction "Y5_5") (pintype "passive"))
    )
    (net (code "337") (name "/S5V0_6") (class "Default")
      (node (ref "R194") (pin "2") (pinfunction "2_2") (pintype "passive"))
      (node (ref "R195") (pin "1") (pinfunction "1_1") (pintype "passive"))
      (node (ref "U42") (pin "2") (pinfunction "Y6_2") (pintype "passive"))
    )
    (net (code "338") (name "/S5V0_7") (class "Default")
      (node (ref "R206") (pin "2") (pinfunction "2_2") (pintype "passive"))
      (node (ref "R207") (pin "1") (pinfunction "1_1") (pintype "passive"))
      (node (ref "U42") (pin "4") (pinfunction "Y7_4") (pintype "passive"))
    )
    (net (code "339") (name "ADC1") (class "Default")
      (node (ref "U32") (pin "3") (pinfunction "Z_3") (pintype "passive"))
    )
    (net (code "340") (name "ADC2") (class "Default")
      (node (ref "U33") (pin "3") (pinfunction "Z_3") (pintype "passive"))
    )
    (net (code "341") (name "ADC3") (class "Default")
      (node (ref "U34") (pin "3") (pinfunction "Z_3") (pintype "passive"))
    )
    (net (code "342") (name "ADC4") (class "Default")
      (node (ref "U35") (pin "3") (pinfunction "Z_3") (pintype "passive"))
    )
    (net (code "343") (name "ADC5") (class "Default")
      (node (ref "U36") (pin "3") (pinfunction "Z_3") (pintype "passive"))
    )
    (net (code "344") (name "ADC6") (class "Default")
      (node (ref "U37") (pin "3") (pinfunction "Z_3") (pintype "passive"))
    )
    (net (code "345") (name "ADC_I2C_SCL") (class "Default")
      (node (ref "R172") (pin "1") (pinfunction "1_1") (pintype "passive"))
      (node (ref "U51") (pin "10") (pinfunction "SCL_10") (pintype "passive"))
    )
    (net (code "346") (name "ADC_I2C_SDA") (class "Default")
      (node (ref "R173") (pin "1") (pinfunction "1_1") (pintype "passive"))
      (node (ref "U51") (pin "9") (pinfunction "SDA_9") (pintype "passive"))
    )
    (net (code "347") (name "ADDR_0") (class "Default")
      (node (ref "U10") (pin "11") (pinfunction "S0_11") (pintype "passive"))
      (node (ref "U11") (pin "11") (pinfunction "S0_11") (pintype "passive"))
      (node (ref "U12") (pin "11") (pinfunction "S0_11") (pintype "passive"))
      (node (ref "U13") (pin "11") (pinfunction "S0_11") (pintype "passive"))
      (node (ref "U14") (pin "11") (pinfunction "S0_11") (pintype "passive"))
      (node (ref "U15") (pin "11") (pinfunction "S0_11") (pintype "passive"))
      (node (ref "U16") (pin "11") (pinfunction "S0_11") (pintype "passive"))
      (node (ref "U17") (pin "11") (pinfunction "S0_11") (pintype "passive"))
      (node (ref "U18") (pin "11") (pinfunction "S0_11") (pintype "passive"))
      (node (ref "U19") (pin "11") (pinfunction "S0_11") (pintype "passive"))
      (node (ref "U20") (pin "11") (pinfunction "S0_11") (pintype "passive"))
      (node (ref "U21") (pin "11") (pinfunction "S0_11") (pintype "passive"))
      (node (ref "U22") (pin "11") (pinfunction "S0_11") (pintype "passive"))
      (node (ref "U23") (pin "11") (pinfunction "S0_11") (pintype "passive"))
      (node (ref "U24") (pin "11") (pinfunction "S0_11") (pintype "passive"))
      (node (ref "U25") (pin "11") (pinfunction "S0_11") (pintype "passive"))
      (node (ref "U26") (pin "11") (pinfunction "S0_11") (pintype "passive"))
      (node (ref "U27") (pin "11") (pinfunction "S0_11") (pintype "passive"))
      (node (ref "U28") (pin "11") (pinfunction "S0_11") (pintype "passive"))
      (node (ref "U29") (pin "11") (pinfunction "S0_11") (pintype "passive"))
      (node (ref "U30") (pin "11") (pinfunction "S0_11") (pintype "passive"))
      (node (ref "U31") (pin "11") (pinfunction "S0_11") (pintype "passive"))
      (node (ref "U32") (pin "11") (pinfunction "S0_11") (pintype "passive"))
      (node (ref "U33") (pin "11") (pinfunction "S0_11") (pintype "passive"))
      (node (ref "U34") (pin "11") (pinfunction "S0_11") (pintype "passive"))
      (node (ref "U35") (pin "11") (pinfunction "S0_11") (pintype "passive"))
      (node (ref "U36") (pin "11") (pinfunction "S0_11") (pintype "passive"))
      (node (ref "U37") (pin "11") (pinfunction "S0_11") (pintype "passive"))
      (node (ref "U38") (pin "11") (pinfunction "S0_11") (pintype "passive"))
      (node (ref "U39") (pin "11") (pinfunction "S0_11") (pintype "passive"))
      (node (ref "U40") (pin "11") (pinfunction "S0_11") (pintype "passive"))
      (node (ref "U41") (pin "11") (pinfunction "S0_11") (pintype "passive"))
      (node (ref "U42") (pin "11") (pinfunction "S0_11") (pintype "passive"))
      (node (ref "U43") (pin "11") (pinfunction "S0_11") (pintype "passive"))
      (node (ref "U44") (pin "11") (pinfunction "S0_11") (pintype "passive"))
      (node (ref "U45") (pin "11") (pinfunction "S0_11") (pintype "passive"))
      (node (ref "U8") (pin "11") (pinfunction "S0_11") (pintype "passive"))
      (node (ref "U9") (pin "11") (pinfunction "S0_11") (pintype "passive"))
    )
    (net (code "348") (name "ADDR_1") (class "Default")
      (node (ref "U10") (pin "10") (pinfunction "S1_10") (pintype "passive"))
      (node (ref "U11") (pin "10") (pinfunction "S1_10") (pintype "passive"))
      (node (ref "U12") (pin "10") (pinfunction "S1_10") (pintype "passive"))
      (node (ref "U13") (pin "10") (pinfunction "S1_10") (pintype "passive"))
      (node (ref "U14") (pin "10") (pinfunction "S1_10") (pintype "passive"))
      (node (ref "U15") (pin "10") (pinfunction "S1_10") (pintype "passive"))
      (node (ref "U16") (pin "10") (pinfunction "S1_10") (pintype "passive"))
      (node (ref "U17") (pin "10") (pinfunction "S1_10") (pintype "passive"))
      (node (ref "U18") (pin "10") (pinfunction "S1_10") (pintype "passive"))
      (node (ref "U19") (pin "10") (pinfunction "S1_10") (pintype "passive"))
      (node (ref "U20") (pin "10") (pinfunction "S1_10") (pintype "passive"))
      (node (ref "U21") (pin "10") (pinfunction "S1_10") (pintype "passive"))
      (node (ref "U22") (pin "10") (pinfunction "S1_10") (pintype "passive"))
      (node (ref "U23") (pin "10") (pinfunction "S1_10") (pintype "passive"))
      (node (ref "U24") (pin "10") (pinfunction "S1_10") (pintype "passive"))
      (node (ref "U25") (pin "10") (pinfunction "S1_10") (pintype "passive"))
      (node (ref "U26") (pin "10") (pinfunction "S1_10") (pintype "passive"))
      (node (ref "U27") (pin "10") (pinfunction "S1_10") (pintype "passive"))
      (node (ref "U28") (pin "10") (pinfunction "S1_10") (pintype "passive"))
      (node (ref "U29") (pin "10") (pinfunction "S1_10") (pintype "passive"))
      (node (ref "U30") (pin "10") (pinfunction "S1_10") (pintype "passive"))
      (node (ref "U31") (pin "10") (pinfunction "S1_10") (pintype "passive"))
      (node (ref "U32") (pin "10") (pinfunction "S1_10") (pintype "passive"))
      (node (ref "U33") (pin "10") (pinfunction "S1_10") (pintype "passive"))
      (node (ref "U34") (pin "10") (pinfunction "S1_10") (pintype "passive"))
      (node (ref "U35") (pin "10") (pinfunction "S1_10") (pintype "passive"))
      (node (ref "U36") (pin "10") (pinfunction "S1_10") (pintype "passive"))
      (node (ref "U37") (pin "10") (pinfunction "S1_10") (pintype "passive"))
      (node (ref "U38") (pin "10") (pinfunction "S1_10") (pintype "passive"))
      (node (ref "U39") (pin "10") (pinfunction "S1_10") (pintype "passive"))
      (node (ref "U40") (pin "10") (pinfunction "S1_10") (pintype "passive"))
      (node (ref "U41") (pin "10") (pinfunction "S1_10") (pintype "passive"))
      (node (ref "U42") (pin "10") (pinfunction "S1_10") (pintype "passive"))
      (node (ref "U43") (pin "10") (pinfunction "S1_10") (pintype "passive"))
      (node (ref "U44") (pin "10") (pinfunction "S1_10") (pintype "passive"))
      (node (ref "U45") (pin "10") (pinfunction "S1_10") (pintype "passive"))
      (node (ref "U8") (pin "10") (pinfunction "S1_10") (pintype "passive"))
      (node (ref "U9") (pin "10") (pinfunction "S1_10") (pintype "passive"))
    )
    (net (code "349") (name "ADDR_2") (class "Default")
      (node (ref "U10") (pin "9") (pinfunction "S2_9") (pintype "passive"))
      (node (ref "U11") (pin "9") (pinfunction "S2_9") (pintype "passive"))
      (node (ref "U12") (pin "9") (pinfunction "S2_9") (pintype "passive"))
      (node (ref "U13") (pin "9") (pinfunction "S2_9") (pintype "passive"))
      (node (ref "U14") (pin "9") (pinfunction "S2_9") (pintype "passive"))
      (node (ref "U15") (pin "9") (pinfunction "S2_9") (pintype "passive"))
      (node (ref "U16") (pin "9") (pinfunction "S2_9") (pintype "passive"))
      (node (ref "U17") (pin "9") (pinfunction "S2_9") (pintype "passive"))
      (node (ref "U18") (pin "9") (pinfunction "S2_9") (pintype "passive"))
      (node (ref "U19") (pin "9") (pinfunction "S2_9") (pintype "passive"))
      (node (ref "U20") (pin "9") (pinfunction "S2_9") (pintype "passive"))
      (node (ref "U21") (pin "9") (pinfunction "S2_9") (pintype "passive"))
      (node (ref "U22") (pin "9") (pinfunction "S2_9") (pintype "passive"))
      (node (ref "U23") (pin "9") (pinfunction "S2_9") (pintype "passive"))
      (node (ref "U24") (pin "9") (pinfunction "S2_9") (pintype "passive"))
      (node (ref "U25") (pin "9") (pinfunction "S2_9") (pintype "passive"))
      (node (ref "U26") (pin "9") (pinfunction "S2_9") (pintype "passive"))
      (node (ref "U27") (pin "9") (pinfunction "S2_9") (pintype "passive"))
      (node (ref "U28") (pin "9") (pinfunction "S2_9") (pintype "passive"))
      (node (ref "U29") (pin "9") (pinfunction "S2_9") (pintype "passive"))
      (node (ref "U30") (pin "9") (pinfunction "S2_9") (pintype "passive"))
      (node (ref "U31") (pin "9") (pinfunction "S2_9") (pintype "passive"))
      (node (ref "U32") (pin "9") (pinfunction "S2_9") (pintype "passive"))
      (node (ref "U33") (pin "9") (pinfunction "S2_9") (pintype "passive"))
      (node (ref "U34") (pin "9") (pinfunction "S2_9") (pintype "passive"))
      (node (ref "U35") (pin "9") (pinfunction "S2_9") (pintype "passive"))
      (node (ref "U36") (pin "9") (pinfunction "S2_9") (pintype "passive"))
      (node (ref "U37") (pin "9") (pinfunction "S2_9") (pintype "passive"))
      (node (ref "U38") (pin "9") (pinfunction "S2_9") (pintype "passive"))
      (node (ref "U39") (pin "9") (pinfunction "S2_9") (pintype "passive"))
      (node (ref "U40") (pin "9") (pinfunction "S2_9") (pintype "passive"))
      (node (ref "U41") (pin "9") (pinfunction "S2_9") (pintype "passive"))
      (node (ref "U42") (pin "9") (pinfunction "S2_9") (pintype "passive"))
      (node (ref "U43") (pin "9") (pinfunction "S2_9") (pintype "passive"))
      (node (ref "U44") (pin "9") (pinfunction "S2_9") (pintype "passive"))
      (node (ref "U45") (pin "9") (pinfunction "S2_9") (pintype "passive"))
      (node (ref "U8") (pin "9") (pinfunction "S2_9") (pintype "passive"))
      (node (ref "U9") (pin "9") (pinfunction "S2_9") (pintype "passive"))
    )
    (net (code "350") (name "ADJ") (class "Default")
      (node (ref "U43") (pin "3") (pinfunction "Z_3") (pintype "passive"))
    )
    (net (code "351") (name "GND") (class "Default")
      (node (ref "C130") (pin "1") (pinfunction "1_1") (pintype "passive"))
      (node (ref "C131") (pin "1") (pinfunction "1_1") (pintype "passive"))
      (node (ref "C132") (pin "1") (pinfunction "1_1") (pintype "passive"))
      (node (ref "C133") (pin "1") (pinfunction "1_1") (pintype "passive"))
      (node (ref "C134") (pin "1") (pinfunction "1_1") (pintype "passive"))
      (node (ref "C135") (pin "1") (pinfunction "1_1") (pintype "passive"))
      (node (ref "C136") (pin "1") (pinfunction "1_1") (pintype "passive"))
      (node (ref "C137") (pin "1") (pinfunction "1_1") (pintype "passive"))
      (node (ref "C138") (pin "1") (pinfunction "1_1") (pintype "passive"))
      (node (ref "C139") (pin "1") (pinfunction "1_1") (pintype "passive"))
      (node (ref "C140") (pin "2") (pinfunction "2_2") (pintype "passive"))
      (node (ref "C141") (pin "2") (pinfunction "2_2") (pintype "passive"))
      (node (ref "C142") (pin "2") (pinfunction "2_2") (pintype "passive"))
      (node (ref "C143") (pin "2") (pinfunction "2_2") (pintype "passive"))
      (node (ref "C144") (pin "2") (pinfunction "2_2") (pintype "passive"))
      (node (ref "C145") (pin "2") (pinfunction "2_2") (pintype "passive"))
      (node (ref "C146") (pin "2") (pinfunction "2_2") (pintype "passive"))
      (node (ref "C147") (pin "2") (pinfunction "2_2") (pintype "passive"))
      (node (ref "C148") (pin "2") (pinfunction "2_2") (pintype "passive"))
      (node (ref "C149") (pin "2") (pinfunction "2_2") (pintype "passive"))
      (node (ref "C150") (pin "1") (pinfunction "1_1") (pintype "passive"))
      (node (ref "C151") (pin "1") (pinfunction "1_1") (pintype "passive"))
      (node (ref "C152") (pin "1") (pinfunction "1_1") (pintype "passive"))
      (node (ref "C153") (pin "1") (pinfunction "1_1") (pintype "passive"))
      (node (ref "C154") (pin "1") (pinfunction "1_1") (pintype "passive"))
      (node (ref "C155") (pin "1") (pinfunction "1_1") (pintype "passive"))
      (node (ref "C156") (pin "1") (pinfunction "1_1") (pintype "passive"))
      (node (ref "C157") (pin "1") (pinfunction "1_1") (pintype "passive"))
      (node (ref "C158") (pin "1") (pinfunction "1_1") (pintype "passive"))
      (node (ref "C159") (pin "1") (pinfunction "1_1") (pintype "passive"))
      (node (ref "C160") (pin "2") (pinfunction "2_2") (pintype "passive"))
      (node (ref "C161") (pin "2") (pinfunction "2_2") (pintype "passive"))
      (node (ref "C162") (pin "2") (pinfunction "2_2") (pintype "passive"))
      (node (ref "C163") (pin "2") (pinfunction "2_2") (pintype "passive"))
      (node (ref "C164") (pin "2") (pinfunction "2_2") (pintype "passive"))
      (node (ref "C165") (pin "2") (pinfunction "2_2") (pintype "passive"))
      (node (ref "C166") (pin "2") (pinfunction "2_2") (pintype "passive"))
      (node (ref "C167") (pin "2") (pinfunction "2_2") (pintype "passive"))
      (node (ref "C168") (pin "2") (pinfunction "2_2") (pintype "passive"))
      (node (ref "C169") (pin "2") (pinfunction "2_2") (pintype "passive"))
      (node (ref "C22") (pin "1") (pinfunction "1_1") (pintype "passive"))
      (node (ref "C23") (pin "1") (pinfunction "1_1") (pintype "passive"))
      (node (ref "P10") (pin "1") (pinfunction "1_1") (pintype "passive"))
      (node (ref "P10") (pin "10") (pinfunction "10_10") (pintype "passive"))
      (node (ref "P10") (pin "2") (pinfunction "2_2") (pintype "passive"))
      (node (ref "P10") (pin "23") (pinfunction "23_23") (pintype "passive"))
      (node (ref "P10") (pin "24") (pinfunction "24_24") (pintype "passive"))
      (node (ref "P10") (pin "9") (pinfunction "9_9") (pintype "passive"))
      (node (ref "P11") (pin "1") (pinfunction "1_1") (pintype "passive"))
      (node (ref "P11") (pin "10") (pinfunction "10_10") (pintype "passive"))
      (node (ref "P11") (pin "2") (pinfunction "2_2") (pintype "passive"))
      (node (ref "P11") (pin "23") (pinfunction "23_23") (pintype "passive"))
      (node (ref "P11") (pin "24") (pinfunction "24_24") (pintype "passive"))
      (node (ref "P11") (pin "9") (pinfunction "9_9") (pintype "passive"))
      (node (ref "P12") (pin "1") (pinfunction "1_1") (pintype "passive"))
      (node (ref "P12") (pin "10") (pinfunction "10_10") (pintype "passive"))
      (node (ref "P12") (pin "2") (pinfunction "2_2") (pintype "passive"))
      (node (ref "P12") (pin "23") (pinfunction "23_23") (pintype "passive"))
      (node (ref "P12") (pin "24") (pinfunction "24_24") (pintype "passive"))
      (node (ref "P12") (pin "9") (pinfunction "9_9") (pintype "passive"))
      (node (ref "P13") (pin "1") (pinfunction "1_1") (pintype "passive"))
      (node (ref "P13") (pin "10") (pinfunction "10_10") (pintype "passive"))
      (node (ref "P13") (pin "2") (pinfunction "2_2") (pintype "passive"))
      (node (ref "P13") (pin "23") (pinfunction "23_23") (pintype "passive"))
      (node (ref "P13") (pin "24") (pinfunction "24_24") (pintype "passive"))
      (node (ref "P13") (pin "9") (pinfunction "9_9") (pintype "passive"))
      (node (ref "P14") (pin "1") (pinfunction "1_1") (pintype "passive"))
      (node (ref "P14") (pin "10") (pinfunction "10_10") (pintype "passive"))
      (node (ref "P14") (pin "2") (pinfunction "2_2") (pintype "passive"))
      (node (ref "P14") (pin "23") (pinfunction "23_23") (pintype "passive"))
      (node (ref "P14") (pin "24") (pinfunction "24_24") (pintype "passive"))
      (node (ref "P14") (pin "9") (pinfunction "9_9") (pintype "passive"))
      (node (ref "P15") (pin "1") (pinfunction "1_1") (pintype "passive"))
      (node (ref "P15") (pin "10") (pinfunction "10_10") (pintype "passive"))
      (node (ref "P15") (pin "2") (pinfunction "2_2") (pintype "passive"))
      (node (ref "P15") (pin "23") (pinfunction "23_23") (pintype "passive"))
      (node (ref "P15") (pin "24") (pinfunction "24_24") (pintype "passive"))
      (node (ref "P15") (pin "9") (pinfunction "9_9") (pintype "passive"))
      (node (ref "P16") (pin "1") (pinfunction "1_1") (pintype "passive"))
      (node (ref "P16") (pin "15") (pinfunction "15_15") (pintype "passive"))
      (node (ref "P16") (pin "16") (pinfunction "16_16") (pintype "passive"))
      (node (ref "P16") (pin "2") (pinfunction "2_2") (pintype "passive"))
      (node (ref "P16") (pin "23") (pinfunction "23_23") (pintype "passive"))
      (node (ref "P16") (pin "24") (pinfunction "24_24") (pintype "passive"))
      (node (ref "P17") (pin "1") (pinfunction "1_1") (pintype "passive"))
      (node (ref "P17") (pin "15") (pinfunction "15_15") (pintype "passive"))
      (node (ref "P17") (pin "16") (pinfunction "16_16") (pintype "passive"))
      (node (ref "P17") (pin "2") (pinfunction "2_2") (pintype "passive"))
      (node (ref "P17") (pin "23") (pinfunction "23_23") (pintype "passive"))
      (node (ref "P17") (pin "24") (pinfunction "24_24") (pintype "passive"))
      (node (ref "P18") (pin "1") (pinfunction "1_1") (pintype "passive"))
      (node (ref "P18") (pin "15") (pinfunction "15_15") (pintype "passive"))
      (node (ref "P18") (pin "16") (pinfunction "16_16") (pintype "passive"))
      (node (ref "P18") (pin "2") (pinfunction "2_2") (pintype "passive"))
      (node (ref "P18") (pin "23") (pinfunction "23_23") (pintype "passive"))
      (node (ref "P18") (pin "24") (pinfunction "24_24") (pintype "passive"))
      (node (ref "P19") (pin "1") (pinfunction "1_1") (pintype "passive"))
      (node (ref "P19") (pin "15") (pinfunction "15_15") (pintype "passive"))
      (node (ref "P19") (pin "16") (pinfunction "16_16") (pintype "passive"))
      (node (ref "P19") (pin "2") (pinfunction "2_2") (pintype "passive"))
      (node (ref "P19") (pin "23") (pinfunction "23_23") (pintype "passive"))
      (node (ref "P19") (pin "24") (pinfunction "24_24") (pintype "passive"))
      (node (ref "P20") (pin "1") (pinfunction "1_1") (pintype "passive"))
      (node (ref "P20") (pin "15") (pinfunction "15_15") (pintype "passive"))
      (node (ref "P20") (pin "16") (pinfunction "16_16") (pintype "passive"))
      (node (ref "P20") (pin "2") (pinfunction "2_2") (pintype "passive"))
      (node (ref "P20") (pin "23") (pinfunction "23_23") (pintype "passive"))
      (node (ref "P20") (pin "24") (pinfunction "24_24") (pintype "passive"))
      (node (ref "P21") (pin "1") (pinfunction "1_1") (pintype "passive"))
      (node (ref "P21") (pin "15") (pinfunction "15_15") (pintype "passive"))
      (node (ref "P21") (pin "16") (pinfunction "16_16") (pintype "passive"))
      (node (ref "P21") (pin "2") (pinfunction "2_2") (pintype "passive"))
      (node (ref "P21") (pin "23") (pinfunction "23_23") (pintype "passive"))
      (node (ref "P21") (pin "24") (pinfunction "24_24") (pintype "passive"))
      (node (ref "P22") (pin "1") (pinfunction "1_1") (pintype "passive"))
      (node (ref "P22") (pin "15") (pinfunction "15_15") (pintype "passive"))
      (node (ref "P22") (pin "16") (pinfunction "16_16") (pintype "passive"))
      (node (ref "P22") (pin "2") (pinfunction "2_2") (pintype "passive"))
      (node (ref "P22") (pin "23") (pinfunction "23_23") (pintype "passive"))
      (node (ref "P22") (pin "24") (pinfunction "24_24") (pintype "passive"))
      (node (ref "P23") (pin "1") (pinfunction "1_1") (pintype "passive"))
      (node (ref "P23") (pin "15") (pinfunction "15_15") (pintype "passive"))
      (node (ref "P23") (pin "16") (pinfunction "16_16") (pintype "passive"))
      (node (ref "P23") (pin "2") (pinfunction "2_2") (pintype "passive"))
      (node (ref "P23") (pin "23") (pinfunction "23_23") (pintype "passive"))
      (node (ref "P23") (pin "24") (pinfunction "24_24") (pintype "passive"))
      (node (ref "P8") (pin "1") (pinfunction "1_1") (pintype "passive"))
      (node (ref "P8") (pin "10") (pinfunction "10_10") (pintype "passive"))
      (node (ref "P8") (pin "2") (pinfunction "2_2") (pintype "passive"))
      (node (ref "P8") (pin "23") (pinfunction "23_23") (pintype "passive"))
      (node (ref "P8") (pin "24") (pinfunction "24_24") (pintype "passive"))
      (node (ref "P8") (pin "9") (pinfunction "9_9") (pintype "passive"))
      (node (ref "P9") (pin "1") (pinfunction "1_1") (pintype "passive"))
      (node (ref "P9") (pin "10") (pinfunction "10_10") (pintype "passive"))
      (node (ref "P9") (pin "2") (pinfunction "2_2") (pintype "passive"))
      (node (ref "P9") (pin "23") (pinfunction "23_23") (pintype "passive"))
      (node (ref "P9") (pin "24") (pinfunction "24_24") (pintype "passive"))
      (node (ref "P9") (pin "9") (pinfunction "9_9") (pintype "passive"))
      (node (ref "R101") (pin "2") (pinfunction "2_2") (pintype "passive"))
      (node (ref "R103") (pin "2") (pinfunction "2_2") (pintype "passive"))
      (node (ref "R105") (pin "2") (pinfunction "2_2") (pintype "passive"))
      (node (ref "R107") (pin "2") (pinfunction "2_2") (pintype "passive"))
      (node (ref "R109") (pin "2") (pinfunction "2_2") (pintype "passive"))
      (node (ref "R111") (pin "2") (pinfunction "2_2") (pintype "passive"))
      (node (ref "R113") (pin "2") (pinfunction "2_2") (pintype "passive"))
      (node (ref "R115") (pin "2") (pinfunction "2_2") (pintype "passive"))
      (node (ref "R117") (pin "2") (pinfunction "2_2") (pintype "passive"))
      (node (ref "R119") (pin "2") (pinfunction "2_2") (pintype "passive"))
      (node (ref "R121") (pin "2") (pinfunction "2_2") (pintype "passive"))
      (node (ref "R123") (pin "2") (pinfunction "2_2") (pintype "passive"))
      (node (ref "R125") (pin "2") (pinfunction "2_2") (pintype "passive"))
      (node (ref "R127") (pin "2") (pinfunction "2_2") (pintype "passive"))
      (node (ref "R129") (pin "2") (pinfunction "2_2") (pintype "passive"))
      (node (ref "R131") (pin "2") (pinfunction "2_2") (pintype "passive"))
      (node (ref "R133") (pin "2") (pinfunction "2_2") (pintype "passive"))
      (node (ref "R135") (pin "2") (pinfunction "2_2") (pintype "passive"))
      (node (ref "R137") (pin "2") (pinfunction "2_2") (pintype "passive"))
      (node (ref "R139") (pin "2") (pinfunction "2_2") (pintype "passive"))
      (node (ref "R141") (pin "2") (pinfunction "2_2") (pintype "passive"))
      (node (ref "R143") (pin "2") (pinfunction "2_2") (pintype "passive"))
      (node (ref "R145") (pin "2") (pinfunction "2_2") (pintype "passive"))
      (node (ref "R147") (pin "2") (pinfunction "2_2") (pintype "passive"))
      (node (ref "R149") (pin "2") (pinfunction "2_2") (pintype "passive"))
      (node (ref "R151") (pin "2") (pinfunction "2_2") (pintype "passive"))
      (node (ref "R153") (pin "2") (pinfunction "2_2") (pintype "passive"))
      (node (ref "R155") (pin "2") (pinfunction "2_2") (pintype "passive"))
      (node (ref "R157") (pin "2") (pinfunction "2_2") (pintype "passive"))
      (node (ref "R159") (pin "2") (pinfunction "2_2") (pintype "passive"))
      (node (ref "R161") (pin "2") (pinfunction "2_2") (pintype "passive"))
      (node (ref "R163") (pin "2") (pinfunction "2_2") (pintype "passive"))
      (node (ref "R165") (pin "2") (pinfunction "2_2") (pintype "passive"))
      (node (ref "R167") (pin "2") (pinfunction "2_2") (pintype "passive"))
      (node (ref "R169") (pin "2") (pinfunction "2_2") (pintype "passive"))
      (node (ref "R17") (pin "2") (pinfunction "2_2") (pintype "passive"))
      (node (ref "R171") (pin "2") (pinfunction "2_2") (pintype "passive"))
      (node (ref "R175") (pin "2") (pinfunction "2_2") (pintype "passive"))
      (node (ref "R177") (pin "2") (pinfunction "2_2") (pintype "passive"))
      (node (ref "R179") (pin "2") (pinfunction "2_2") (pintype "passive"))
      (node (ref "R181") (pin "2") (pinfunction "2_2") (pintype "passive"))
      (node (ref "R183") (pin "2") (pinfunction "2_2") (pintype "passive"))
      (node (ref "R185") (pin "2") (pinfunction "2_2") (pintype "passive"))
      (node (ref "R187") (pin "2") (pinfunction "2_2") (pintype "passive"))
      (node (ref "R189") (pin "2") (pinfunction "2_2") (pintype "passive"))
      (node (ref "R19") (pin "2") (pinfunction "2_2") (pintype "passive"))
      (node (ref "R191") (pin "2") (pinfunction "2_2") (pintype "passive"))
      (node (ref "R193") (pin "2") (pinfunction "2_2") (pintype "passive"))
      (node (ref "R195") (pin "2") (pinfunction "2_2") (pintype "passive"))
      (node (ref "R197") (pin "2") (pinfunction "2_2") (pintype "passive"))
      (node (ref "R199") (pin "2") (pinfunction "2_2") (pintype "passive"))
      (node (ref "R201") (pin "2") (pinfunction "2_2") (pintype "passive"))
      (node (ref "R203") (pin "2") (pinfunction "2_2") (pintype "passive"))
      (node (ref "R205") (pin "2") (pinfunction "2_2") (pintype "passive"))
      (node (ref "R207") (pin "2") (pinfunction "2_2") (pintype "passive"))
      (node (ref "R209") (pin "2") (pinfunction "2_2") (pintype "passive"))
      (node (ref "R21") (pin "2") (pinfunction "2_2") (pintype "passive"))
      (node (ref "R23") (pin "2") (pinfunction "2_2") (pintype "passive"))
      (node (ref "R25") (pin "2") (pinfunction "2_2") (pintype "passive"))
      (node (ref "R27") (pin "2") (pinfunction "2_2") (pintype "passive"))
      (node (ref "R29") (pin "2") (pinfunction "2_2") (pintype "passive"))
      (node (ref "R31") (pin "2") (pinfunction "2_2") (pintype "passive"))
      (node (ref "R33") (pin "2") (pinfunction "2_2") (pintype "passive"))
      (node (ref "R35") (pin "2") (pinfunction "2_2") (pintype "passive"))
      (node (ref "R37") (pin "2") (pinfunction "2_2") (pintype "passive"))
      (node (ref "R39") (pin "2") (pinfunction "2_2") (pintype "passive"))
      (node (ref "R41") (pin "2") (pinfunction "2_2") (pintype "passive"))
      (node (ref "R43") (pin "2") (pinfunction "2_2") (pintype "passive"))
      (node (ref "R45") (pin "2") (pinfunction "2_2") (pintype "passive"))
      (node (ref "R47") (pin "2") (pinfunction "2_2") (pintype "passive"))
      (node (ref "R49") (pin "2") (pinfunction "2_2") (pintype "passive"))
      (node (ref "R51") (pin "2") (pinfunction "2_2") (pintype "passive"))
      (node (ref "R53") (pin "2") (pinfunction "2_2") (pintype "passive"))
      (node (ref "R55") (pin "2") (pinfunction "2_2") (pintype "passive"))
      (node (ref "R57") (pin "2") (pinfunction "2_2") (pintype "passive"))
      (node (ref "R59") (pin "2") (pinfunction "2_2") (pintype "passive"))
      (node (ref "R61") (pin "2") (pinfunction "2_2") (pintype "passive"))
      (node (ref "R63") (pin "2") (pinfunction "2_2") (pintype "passive"))
      (node (ref "R65") (pin "2") (pinfunction "2_2") (pintype "passive"))
      (node (ref "R67") (pin "2") (pinfunction "2_2") (pintype "passive"))
      (node (ref "R69") (pin "2") (pinfunction "2_2") (pintype "passive"))
      (node (ref "R71") (pin "2") (pinfunction "2_2") (pintype "passive"))
      (node (ref "R73") (pin "2") (pinfunction "2_2") (pintype "passive"))
      (node (ref "R75") (pin "2") (pinfunction "2_2") (pintype "passive"))
      (node (ref "R77") (pin "2") (pinfunction "2_2") (pintype "passive"))
      (node (ref "R79") (pin "2") (pinfunction "2_2") (pintype "passive"))
      (node (ref "R81") (pin "2") (pinfunction "2_2") (pintype "passive"))
      (node (ref "R83") (pin "2") (pinfunction "2_2") (pintype "passive"))
      (node (ref "R85") (pin "2") (pinfunction "2_2") (pintype "passive"))
      (node (ref "R87") (pin "2") (pinfunction "2_2") (pintype "passive"))
      (node (ref "R89") (pin "2") (pinfunction "2_2") (pintype "passive"))
      (node (ref "R91") (pin "2") (pinfunction "2_2") (pintype "passive"))
      (node (ref "R93") (pin "2") (pinfunction "2_2") (pintype "passive"))
      (node (ref "R95") (pin "2") (pinfunction "2_2") (pintype "passive"))
      (node (ref "R97") (pin "2") (pinfunction "2_2") (pintype "passive"))
      (node (ref "R99") (pin "2") (pinfunction "2_2") (pintype "passive"))
      (node (ref "U10") (pin "7") (pinfunction "VEE_7") (pintype "passive"))
      (node (ref "U10") (pin "8") (pinfunction "GND_8") (pintype "passive"))
      (node (ref "U11") (pin "7") (pinfunction "VEE_7") (pintype "passive"))
      (node (ref "U11") (pin "8") (pinfunction "GND_8") (pintype "passive"))
      (node (ref "U12") (pin "7") (pinfunction "VEE_7") (pintype "passive"))
      (node (ref "U12") (pin "8") (pinfunction "GND_8") (pintype "passive"))
      (node (ref "U13") (pin "7") (pinfunction "VEE_7") (pintype "passive"))
      (node (ref "U13") (pin "8") (pinfunction "GND_8") (pintype "passive"))
      (node (ref "U14") (pin "7") (pinfunction "VEE_7") (pintype "passive"))
      (node (ref "U14") (pin "8") (pinfunction "GND_8") (pintype "passive"))
      (node (ref "U15") (pin "7") (pinfunction "VEE_7") (pintype "passive"))
      (node (ref "U15") (pin "8") (pinfunction "GND_8") (pintype "passive"))
      (node (ref "U16") (pin "7") (pinfunction "VEE_7") (pintype "passive"))
      (node (ref "U16") (pin "8") (pinfunction "GND_8") (pintype "passive"))
      (node (ref "U17") (pin "7") (pinfunction "VEE_7") (pintype "passive"))
      (node (ref "U17") (pin "8") (pinfunction "GND_8") (pintype "passive"))
      (node (ref "U18") (pin "7") (pinfunction "VEE_7") (pintype "passive"))
      (node (ref "U18") (pin "8") (pinfunction "GND_8") (pintype "passive"))
      (node (ref "U19") (pin "7") (pinfunction "VEE_7") (pintype "passive"))
      (node (ref "U19") (pin "8") (pinfunction "GND_8") (pintype "passive"))
      (node (ref "U20") (pin "7") (pinfunction "VEE_7") (pintype "passive"))
      (node (ref "U20") (pin "8") (pinfunction "GND_8") (pintype "passive"))
      (node (ref "U21") (pin "7") (pinfunction "VEE_7") (pintype "passive"))
      (node (ref "U21") (pin "8") (pinfunction "GND_8") (pintype "passive"))
      (node (ref "U22") (pin "7") (pinfunction "VEE_7") (pintype "passive"))
      (node (ref "U22") (pin "8") (pinfunction "GND_8") (pintype "passive"))
      (node (ref "U23") (pin "7") (pinfunction "VEE_7") (pintype "passive"))
      (node (ref "U23") (pin "8") (pinfunction "GND_8") (pintype "passive"))
      (node (ref "U24") (pin "7") (pinfunction "VEE_7") (pintype "passive"))
      (node (ref "U24") (pin "8") (pinfunction "GND_8") (pintype "passive"))
      (node (ref "U25") (pin "7") (pinfunction "VEE_7") (pintype "passive"))
      (node (ref "U25") (pin "8") (pinfunction "GND_8") (pintype "passive"))
      (node (ref "U26") (pin "7") (pinfunction "VEE_7") (pintype "passive"))
      (node (ref "U26") (pin "8") (pinfunction "GND_8") (pintype "passive"))
      (node (ref "U27") (pin "7") (pinfunction "VEE_7") (pintype "passive"))
      (node (ref "U27") (pin "8") (pinfunction "GND_8") (pintype "passive"))
      (node (ref "U28") (pin "7") (pinfunction "VEE_7") (pintype "passive"))
      (node (ref "U28") (pin "8") (pinfunction "GND_8") (pintype "passive"))
      (node (ref "U29") (pin "7") (pinfunction "VEE_7") (pintype "passive"))
      (node (ref "U29") (pin "8") (pinfunction "GND_8") (pintype "passive"))
      (node (ref "U30") (pin "7") (pinfunction "VEE_7") (pintype "passive"))
      (node (ref "U30") (pin "8") (pinfunction "GND_8") (pintype "passive"))
      (node (ref "U31") (pin "7") (pinfunction "VEE_7") (pintype "passive"))
      (node (ref "U31") (pin "8") (pinfunction "GND_8") (pintype "passive"))
      (node (ref "U32") (pin "7") (pinfunction "VEE_7") (pintype "passive"))
      (node (ref "U32") (pin "8") (pinfunction "GND_8") (pintype "passive"))
      (node (ref "U33") (pin "7") (pinfunction "VEE_7") (pintype "passive"))
      (node (ref "U33") (pin "8") (pinfunction "GND_8") (pintype "passive"))
      (node (ref "U34") (pin "7") (pinfunction "VEE_7") (pintype "passive"))
      (node (ref "U34") (pin "8") (pinfunction "GND_8") (pintype "passive"))
      (node (ref "U35") (pin "7") (pinfunction "VEE_7") (pintype "passive"))
      (node (ref "U35") (pin "8") (pinfunction "GND_8") (pintype "passive"))
      (node (ref "U36") (pin "7") (pinfunction "VEE_7") (pintype "passive"))
      (node (ref "U36") (pin "8") (pinfunction "GND_8") (pintype "passive"))
      (node (ref "U37") (pin "7") (pinfunction "VEE_7") (pintype "passive"))
      (node (ref "U37") (pin "8") (pinfunction "GND_8") (pintype "passive"))
      (node (ref "U38") (pin "7") (pinfunction "VEE_7") (pintype "passive"))
      (node (ref "U38") (pin "8") (pinfunction "GND_8") (pintype "passive"))
      (node (ref "U39") (pin "7") (pinfunction "VEE_7") (pintype "passive"))
      (node (ref "U39") (pin "8") (pinfunction "GND_8") (pintype "passive"))
      (node (ref "U40") (pin "7") (pinfunction "VEE_7") (pintype "passive"))
      (node (ref "U40") (pin "8") (pinfunction "GND_8") (pintype "passive"))
      (node (ref "U41") (pin "7") (pinfunction "VEE_7") (pintype "passive"))
      (node (ref "U41") (pin "8") (pinfunction "GND_8") (pintype "passive"))
      (node (ref "U42") (pin "7") (pinfunction "VEE_7") (pintype "passive"))
      (node (ref "U42") (pin "8") (pinfunction "GND_8") (pintype "passive"))
      (node (ref "U43") (pin "7") (pinfunction "VEE_7") (pintype "passive"))
      (node (ref "U43") (pin "8") (pinfunction "GND_8") (pintype "passive"))
      (node (ref "U44") (pin "7") (pinfunction "VEE_7") (pintype "passive"))
      (node (ref "U44") (pin "8") (pinfunction "GND_8") (pintype "passive"))
      (node (ref "U45") (pin "7") (pinfunction "VEE_7") (pintype "passive"))
      (node (ref "U45") (pin "8") (pinfunction "GND_8") (pintype "passive"))
      (node (ref "U50") (pin "1") (pinfunction "GND_1") (pintype "passive"))
      (node (ref "U51") (pin "1") (pinfunction "ADDR_1") (pintype "passive"))
      (node (ref "U51") (pin "3") (pinfunction "GND_3") (pintype "passive"))
      (node (ref "U8") (pin "7") (pinfunction "VEE_7") (pintype "passive"))
      (node (ref "U8") (pin "8") (pinfunction "GND_8") (pintype "passive"))
      (node (ref "U9") (pin "7") (pinfunction "VEE_7") (pintype "passive"))
      (node (ref "U9") (pin "8") (pinfunction "GND_8") (pintype "passive"))
    )
    (net (code "352") (name "GPIO0") (class "Default")
      (node (ref "U8") (pin "3") (pinfunction "Z_3") (pintype "passive"))
    )
    (net (code "353") (name "GPIO1") (class "Default")
      (node (ref "U9") (pin "3") (pinfunction "Z_3") (pintype "passive"))
    )
    (net (code "354") (name "GPIO2") (class "Default")
      (node (ref "U10") (pin "3") (pinfunction "Z_3") (pintype "passive"))
    )
    (net (code "355") (name "GPIO3") (class "Default")
      (node (ref "U11") (pin "3") (pinfunction "Z_3") (pintype "passive"))
    )
    (net (code "356") (name "GPIO4") (class "Default")
      (node (ref "U12") (pin "3") (pinfunction "Z_3") (pintype "passive"))
    )
    (net (code "357") (name "GPIO5") (class "Default")
      (node (ref "U13") (pin "3") (pinfunction "Z_3") (pintype "passive"))
    )
    (net (code "358") (name "GPIO6") (class "Default")
      (node (ref "U14") (pin "3") (pinfunction "Z_3") (pintype "passive"))
    )
    (net (code "359") (name "GPIO7") (class "Default")
      (node (ref "U15") (pin "3") (pinfunction "Z_3") (pintype "passive"))
    )
    (net (code "360") (name "GPIO8") (class "Default")
      (node (ref "U16") (pin "3") (pinfunction "Z_3") (pintype "passive"))
    )
    (net (code "361") (name "GPIO9") (class "Default")
      (node (ref "U17") (pin "3") (pinfunction "Z_3") (pintype "passive"))
    )
    (net (code "362") (name "GPIO10") (class "Default")
      (node (ref "U18") (pin "3") (pinfunction "Z_3") (pintype "passive"))
    )
    (net (code "363") (name "GPIO11") (class "Default")
      (node (ref "U19") (pin "3") (pinfunction "Z_3") (pintype "passive"))
    )
    (net (code "364") (name "GPIO12") (class "Default")
      (node (ref "U20") (pin "3") (pinfunction "Z_3") (pintype "passive"))
    )
    (net (code "365") (name "GPIO13") (class "Default")
      (node (ref "U21") (pin "3") (pinfunction "Z_3") (pintype "passive"))
    )
    (net (code "366") (name "GPIO14") (class "Default")
      (node (ref "U22") (pin "3") (pinfunction "Z_3") (pintype "passive"))
    )
    (net (code "367") (name "GPIO15") (class "Default")
      (node (ref "U23") (pin "3") (pinfunction "Z_3") (pintype "passive"))
    )
    (net (code "368") (name "I2C_SCL") (class "Default")
      (node (ref "U31") (pin "3") (pinfunction "Z_3") (pintype "passive"))
    )
    (net (code "369") (name "I2C_SDA") (class "Default")
      (node (ref "U30") (pin "3") (pinfunction "Z_3") (pintype "passive"))
    )
    (net (code "370") (name "I_MA_0") (class "Default")
      (node (ref "U45") (pin "13") (pinfunction "Y0_13") (pintype "passive"))
    )
    (net (code "371") (name "I_MA_1") (class "Default")
      (node (ref "U45") (pin "14") (pinfunction "Y1_14") (pintype "passive"))
    )
    (net (code "372") (name "I_MA_2") (class "Default")
      (node (ref "U45") (pin "15") (pinfunction "Y2_15") (pintype "passive"))
    )
    (net (code "373") (name "I_MA_3") (class "Default")
      (node (ref "U45") (pin "12") (pinfunction "Y3_12") (pintype "passive"))
    )
    (net (code "374") (name "I_MA_4") (class "Default")
      (node (ref "U45") (pin "1") (pinfunction "Y4_1") (pintype "passive"))
    )
    (net (code "375") (name "I_MA_5") (class "Default")
      (node (ref "U45") (pin "5") (pinfunction "Y5_5") (pintype "passive"))
    )
    (net (code "376") (name "I_MA_6") (class "Default")
      (node (ref "U45") (pin "2") (pinfunction "Y6_2") (pintype "passive"))
    )
    (net (code "377") (name "I_MA_7") (class "Default")
      (node (ref "U45") (pin "4") (pinfunction "Y7_4") (pintype "passive"))
    )
    (net (code "378") (name "I_UA_0") (class "Default")
      (node (ref "U44") (pin "13") (pinfunction "Y0_13") (pintype "passive"))
    )
    (net (code "379") (name "I_UA_1") (class "Default")
      (node (ref "U44") (pin "14") (pinfunction "Y1_14") (pintype "passive"))
    )
    (net (code "380") (name "I_UA_2") (class "Default")
      (node (ref "U44") (pin "15") (pinfunction "Y2_15") (pintype "passive"))
    )
    (net (code "381") (name "I_UA_3") (class "Default")
      (node (ref "U44") (pin "12") (pinfunction "Y3_12") (pintype "passive"))
    )
    (net (code "382") (name "I_UA_4") (class "Default")
      (node (ref "U44") (pin "1") (pinfunction "Y4_1") (pintype "passive"))
    )
    (net (code "383") (name "I_UA_5") (class "Default")
      (node (ref "U44") (pin "5") (pinfunction "Y5_5") (pintype "passive"))
    )
    (net (code "384") (name "I_UA_6") (class "Default")
      (node (ref "U44") (pin "2") (pinfunction "Y6_2") (pintype "passive"))
    )
    (net (code "385") (name "I_UA_7") (class "Default")
      (node (ref "U44") (pin "4") (pinfunction "Y7_4") (pintype "passive"))
    )
    (net (code "386") (name "S1V8") (class "Default")
      (node (ref "U38") (pin "3") (pinfunction "Z_3") (pintype "passive"))
    )
    (net (code "387") (name "S2V5") (class "Default")
      (node (ref "U39") (pin "3") (pinfunction "Z_3") (pintype "passive"))
    )
    (net (code "388") (name "S3V0") (class "Default")
      (node (ref "U40") (pin "3") (pinfunction "Z_3") (pintype "passive"))
    )
    (net (code "389") (name "S3V3") (class "Default")
      (node (ref "U41") (pin "3") (pinfunction "Z_3") (pintype "passive"))
    )
    (net (code "390") (name "S5V0") (class "Default")
      (node (ref "U42") (pin "3") (pinfunction "Z_3") (pintype "passive"))
    )
    (net (code "391") (name "SPDT_EN") (class "Default")
      (node (ref "U10") (pin "6") (pinfunction "~{EN}_6") (pintype "passive"))
      (node (ref "U11") (pin "6") (pinfunction "~{EN}_6") (pintype "passive"))
      (node (ref "U12") (pin "6") (pinfunction "~{EN}_6") (pintype "passive"))
      (node (ref "U13") (pin "6") (pinfunction "~{EN}_6") (pintype "passive"))
      (node (ref "U14") (pin "6") (pinfunction "~{EN}_6") (pintype "passive"))
      (node (ref "U15") (pin "6") (pinfunction "~{EN}_6") (pintype "passive"))
      (node (ref "U16") (pin "6") (pinfunction "~{EN}_6") (pintype "passive"))
      (node (ref "U17") (pin "6") (pinfunction "~{EN}_6") (pintype "passive"))
      (node (ref "U18") (pin "6") (pinfunction "~{EN}_6") (pintype "passive"))
      (node (ref "U19") (pin "6") (pinfunction "~{EN}_6") (pintype "passive"))
      (node (ref "U20") (pin "6") (pinfunction "~{EN}_6") (pintype "passive"))
      (node (ref "U21") (pin "6") (pinfunction "~{EN}_6") (pintype "passive"))
      (node (ref "U22") (pin "6") (pinfunction "~{EN}_6") (pintype "passive"))
      (node (ref "U23") (pin "6") (pinfunction "~{EN}_6") (pintype "passive"))
      (node (ref "U24") (pin "6") (pinfunction "~{EN}_6") (pintype "passive"))
      (node (ref "U25") (pin "6") (pinfunction "~{EN}_6") (pintype "passive"))
      (node (ref "U26") (pin "6") (pinfunction "~{EN}_6") (pintype "passive"))
      (node (ref "U27") (pin "6") (pinfunction "~{EN}_6") (pintype "passive"))
      (node (ref "U28") (pin "6") (pinfunction "~{EN}_6") (pintype "passive"))
      (node (ref "U29") (pin "6") (pinfunction "~{EN}_6") (pintype "passive"))
      (node (ref "U30") (pin "6") (pinfunction "~{EN}_6") (pintype "passive"))
      (node (ref "U31") (pin "6") (pinfunction "~{EN}_6") (pintype "passive"))
      (node (ref "U32") (pin "6") (pinfunction "~{EN}_6") (pintype "passive"))
      (node (ref "U33") (pin "6") (pinfunction "~{EN}_6") (pintype "passive"))
      (node (ref "U34") (pin "6") (pinfunction "~{EN}_6") (pintype "passive"))
      (node (ref "U35") (pin "6") (pinfunction "~{EN}_6") (pintype "passive"))
      (node (ref "U36") (pin "6") (pinfunction "~{EN}_6") (pintype "passive"))
      (node (ref "U37") (pin "6") (pinfunction "~{EN}_6") (pintype "passive"))
      (node (ref "U38") (pin "6") (pinfunction "~{EN}_6") (pintype "passive"))
      (node (ref "U39") (pin "6") (pinfunction "~{EN}_6") (pintype "passive"))
      (node (ref "U40") (pin "6") (pinfunction "~{EN}_6") (pintype "passive"))
      (node (ref "U41") (pin "6") (pinfunction "~{EN}_6") (pintype "passive"))
      (node (ref "U42") (pin "6") (pinfunction "~{EN}_6") (pintype "passive"))
      (node (ref "U43") (pin "6") (pinfunction "~{EN}_6") (pintype "passive"))
      (node (ref "U44") (pin "6") (pinfunction "~{EN}_6") (pintype "passive"))
      (node (ref "U45") (pin "6") (pinfunction "~{EN}_6") (pintype "passive"))
      (node (ref "U8") (pin "6") (pinfunction "~{EN}_6") (pintype "passive"))
      (node (ref "U9") (pin "6") (pinfunction "~{EN}_6") (pintype "passive"))
    )
    (net (code "392") (name "SPI1_CS") (class "Default")
      (node (ref "U29") (pin "3") (pinfunction "Z_3") (pintype "passive"))
    )
    (net (code "393") (name "SPI1_MISO") (class "Default")
      (node (ref "U26") (pin "3") (pinfunction "Z_3") (pintype "passive"))
    )
    (net (code "394") (name "SPI1_MOSI") (class "Default")
      (node (ref "U27") (pin "3") (pinfunction "Z_3") (pintype "passive"))
    )
    (net (code "395") (name "SPI1_SCK") (class "Default")
      (node (ref "U28") (pin "3") (pinfunction "Z_3") (pintype "passive"))
    )
    (net (code "396") (name "USART1_RX") (class "Default")
      (node (ref "U24") (pin "3") (pinfunction "Z_3") (pintype "passive"))
    )
    (net (code "397") (name "USART1_TX") (class "Default")
      (node (ref "U25") (pin "3") (pinfunction "Z_3") (pintype "passive"))
    )
    (net (code "398") (name "VCC+1V8_0") (class "Default")
      (node (ref "P8") (pin "3") (pinfunction "3_3") (pintype "passive"))
      (node (ref "R112") (pin "1") (pinfunction "1_1") (pintype "passive"))
    )
    (net (code "399") (name "VCC+1V8_1") (class "Default")
      (node (ref "P9") (pin "3") (pinfunction "3_3") (pintype "passive"))
      (node (ref "R124") (pin "1") (pinfunction "1_1") (pintype "passive"))
    )
    (net (code "400") (name "VCC+1V8_2") (class "Default")
      (node (ref "P10") (pin "3") (pinfunction "3_3") (pintype "passive"))
      (node (ref "R136") (pin "1") (pinfunction "1_1") (pintype "passive"))
    )
    (net (code "401") (name "VCC+1V8_3") (class "Default")
      (node (ref "P11") (pin "3") (pinfunction "3_3") (pintype "passive"))
      (node (ref "R148") (pin "1") (pinfunction "1_1") (pintype "passive"))
    )
    (net (code "402") (name "VCC+1V8_4") (class "Default")
      (node (ref "P12") (pin "3") (pinfunction "3_3") (pintype "passive"))
      (node (ref "R160") (pin "1") (pinfunction "1_1") (pintype "passive"))
    )
    (net (code "403") (name "VCC+1V8_5") (class "Default")
      (node (ref "P13") (pin "3") (pinfunction "3_3") (pintype "passive"))
      (node (ref "R174") (pin "1") (pinfunction "1_1") (pintype "passive"))
    )
    (net (code "404") (name "VCC+1V8_6") (class "Default")
      (node (ref "P14") (pin "3") (pinfunction "3_3") (pintype "passive"))
      (node (ref "R186") (pin "1") (pinfunction "1_1") (pintype "passive"))
    )
    (net (code "405") (name "VCC+1V8_7") (class "Default")
      (node (ref "P15") (pin "3") (pinfunction "3_3") (pintype "passive"))
      (node (ref "R198") (pin "1") (pinfunction "1_1") (pintype "passive"))
    )
    (net (code "406") (name "VCC+2V5_0") (class "Default")
      (node (ref "P8") (pin "4") (pinfunction "4_4") (pintype "passive"))
      (node (ref "R114") (pin "1") (pinfunction "1_1") (pintype "passive"))
    )
    (net (code "407") (name "VCC+2V5_1") (class "Default")
      (node (ref "P9") (pin "4") (pinfunction "4_4") (pintype "passive"))
      (node (ref "R126") (pin "1") (pinfunction "1_1") (pintype "passive"))
    )
    (net (code "408") (name "VCC+2V5_2") (class "Default")
      (node (ref "P10") (pin "4") (pinfunction "4_4") (pintype "passive"))
      (node (ref "R138") (pin "1") (pinfunction "1_1") (pintype "passive"))
    )
    (net (code "409") (name "VCC+2V5_3") (class "Default")
      (node (ref "P11") (pin "4") (pinfunction "4_4") (pintype "passive"))
      (node (ref "R150") (pin "1") (pinfunction "1_1") (pintype "passive"))
    )
    (net (code "410") (name "VCC+2V5_4") (class "Default")
      (node (ref "P12") (pin "4") (pinfunction "4_4") (pintype "passive"))
      (node (ref "R162") (pin "1") (pinfunction "1_1") (pintype "passive"))
    )
    (net (code "411") (name "VCC+2V5_5") (class "Default")
      (node (ref "P13") (pin "4") (pinfunction "4_4") (pintype "passive"))
      (node (ref "R176") (pin "1") (pinfunction "1_1") (pintype "passive"))
    )
    (net (code "412") (name "VCC+2V5_6") (class "Default")
      (node (ref "P14") (pin "4") (pinfunction "4_4") (pintype "passive"))
      (node (ref "R188") (pin "1") (pinfunction "1_1") (pintype "passive"))
    )
    (net (code "413") (name "VCC+2V5_7") (class "Default")
      (node (ref "P15") (pin "4") (pinfunction "4_4") (pintype "passive"))
      (node (ref "R200") (pin "1") (pinfunction "1_1") (pintype "passive"))
    )
    (net (code "414") (name "VCC+3V0_0") (class "Default")
      (node (ref "P8") (pin "5") (pinfunction "5_5") (pintype "passive"))
      (node (ref "R116") (pin "1") (pinfunction "1_1") (pintype "passive"))
    )
    (net (code "415") (name "VCC+3V0_1") (class "Default")
      (node (ref "P9") (pin "5") (pinfunction "5_5") (pintype "passive"))
      (node (ref "R128") (pin "1") (pinfunction "1_1") (pintype "passive"))
    )
    (net (code "416") (name "VCC+3V0_2") (class "Default")
      (node (ref "P10") (pin "5") (pinfunction "5_5") (pintype "passive"))
      (node (ref "R140") (pin "1") (pinfunction "1_1") (pintype "passive"))
    )
    (net (code "417") (name "VCC+3V0_3") (class "Default")
      (node (ref "P11") (pin "5") (pinfunction "5_5") (pintype "passive"))
      (node (ref "R152") (pin "1") (pinfunction "1_1") (pintype "passive"))
    )
    (net (code "418") (name "VCC+3V0_4") (class "Default")
      (node (ref "P12") (pin "5") (pinfunction "5_5") (pintype "passive"))
      (node (ref "R164") (pin "1") (pinfunction "1_1") (pintype "passive"))
    )
    (net (code "419") (name "VCC+3V0_5") (class "Default")
      (node (ref "P13") (pin "5") (pinfunction "5_5") (pintype "passive"))
      (node (ref "R178") (pin "1") (pinfunction "1_1") (pintype "passive"))
    )
    (net (code "420") (name "VCC+3V0_6") (class "Default")
      (node (ref "P14") (pin "5") (pinfunction "5_5") (pintype "passive"))
      (node (ref "R190") (pin "1") (pinfunction "1_1") (pintype "passive"))
    )
    (net (code "421") (name "VCC+3V0_7") (class "Default")
      (node (ref "P15") (pin "5") (pinfunction "5_5") (pintype "passive"))
      (node (ref "R202") (pin "1") (pinfunction "1_1") (pintype "passive"))
    )
    (net (code "422") (name "VCC+3V3_0") (class "Default")
      (node (ref "P8") (pin "6") (pinfunction "6_6") (pintype "passive"))
      (node (ref "R118") (pin "1") (pinfunction "1_1") (pintype "passive"))
    )
    (net (code "423") (name "VCC+3V3_1") (class "Default")
      (node (ref "P9") (pin "6") (pinfunction "6_6") (pintype "passive"))
      (node (ref "R130") (pin "1") (pinfunction "1_1") (pintype "passive"))
    )
    (net (code "424") (name "VCC+3V3_2") (class "Default")
      (node (ref "P10") (pin "6") (pinfunction "6_6") (pintype "passive"))
      (node (ref "R142") (pin "1") (pinfunction "1_1") (pintype "passive"))
    )
    (net (code "425") (name "VCC+3V3_3") (class "Default")
      (node (ref "P11") (pin "6") (pinfunction "6_6") (pintype "passive"))
      (node (ref "R154") (pin "1") (pinfunction "1_1") (pintype "passive"))
    )
    (net (code "426") (name "VCC+3V3_4") (class "Default")
      (node (ref "P12") (pin "6") (pinfunction "6_6") (pintype "passive"))
      (node (ref "R166") (pin "1") (pinfunction "1_1") (pintype "passive"))
    )
    (net (code "427") (name "VCC+3V3_5") (class "Default")
      (node (ref "P13") (pin "6") (pinfunction "6_6") (pintype "passive"))
      (node (ref "R180") (pin "1") (pinfunction "1_1") (pintype "passive"))
    )
    (net (code "428") (name "VCC+3V3_6") (class "Default")
      (node (ref "P14") (pin "6") (pinfunction "6_6") (pintype "passive"))
      (node (ref "R192") (pin "1") (pinfunction "1_1") (pintype "passive"))
    )
    (net (code "429") (name "VCC+3V3_7") (class "Default")
      (node (ref "P15") (pin "6") (pinfunction "6_6") (pintype "passive"))
      (node (ref "R204") (pin "1") (pinfunction "1_1") (pintype "passive"))
    )
    (net (code "430") (name "VCC+5V0-0") (class "Default")
      (node (ref "P8") (pin "7") (pinfunction "7_7") (pintype "passive"))
      (node (ref "R120") (pin "1") (pinfunction "1_1") (pintype "passive"))
    )
    (net (code "431") (name "VCC+5V0-1") (class "Default")
      (node (ref "P9") (pin "7") (pinfunction "7_7") (pintype "passive"))
      (node (ref "R132") (pin "1") (pinfunction "1_1") (pintype "passive"))
    )
    (net (code "432") (name "VCC+5V0-2") (class "Default")
      (node (ref "P10") (pin "7") (pinfunction "7_7") (pintype "passive"))
      (node (ref "R144") (pin "1") (pinfunction "1_1") (pintype "passive"))
    )
    (net (code "433") (name "VCC+5V0-3") (class "Default")
      (node (ref "P11") (pin "7") (pinfunction "7_7") (pintype "passive"))
      (node (ref "R156") (pin "1") (pinfunction "1_1") (pintype "passive"))
    )
    (net (code "434") (name "VCC+5V0-4") (class "Default")
      (node (ref "P12") (pin "7") (pinfunction "7_7") (pintype "passive"))
      (node (ref "R168") (pin "1") (pinfunction "1_1") (pintype "passive"))
    )
    (net (code "435") (name "VCC+5V0-5") (class "Default")
      (node (ref "P13") (pin "7") (pinfunction "7_7") (pintype "passive"))
      (node (ref "R182") (pin "1") (pinfunction "1_1") (pintype "passive"))
    )
    (net (code "436") (name "VCC+5V0-6") (class "Default")
      (node (ref "P14") (pin "7") (pinfunction "7_7") (pintype "passive"))
      (node (ref "R194") (pin "1") (pinfunction "1_1") (pintype "passive"))
    )
    (net (code "437") (name "VCC+5V0-7") (class "Default")
      (node (ref "P15") (pin "7") (pinfunction "7_7") (pintype "passive"))
      (node (ref "R206") (pin "1") (pinfunction "1_1") (pintype "passive"))
    )
    (net (code "438") (name "VCC+12V0") (class "Default")
      (node (ref "C22") (pin "2") (pinfunction "2_2") (pintype "passive"))
      (node (ref "U50") (pin "3") (pinfunction "VIN_3") (pintype "passive"))
    )
    (net (code "439") (name "VCC+ADJ_0") (class "Default")
      (node (ref "P8") (pin "8") (pinfunction "8_8") (pintype "passive"))
      (node (ref "R122") (pin "1") (pinfunction "1_1") (pintype "passive"))
    )
    (net (code "440") (name "VCC+ADJ_1") (class "Default")
      (node (ref "P9") (pin "8") (pinfunction "8_8") (pintype "passive"))
      (node (ref "R134") (pin "1") (pinfunction "1_1") (pintype "passive"))
    )
    (net (code "441") (name "VCC+ADJ_2") (class "Default")
      (node (ref "P10") (pin "8") (pinfunction "8_8") (pintype "passive"))
      (node (ref "R146") (pin "1") (pinfunction "1_1") (pintype "passive"))
    )
    (net (code "442") (name "VCC+ADJ_3") (class "Default")
      (node (ref "P11") (pin "8") (pinfunction "8_8") (pintype "passive"))
      (node (ref "R158") (pin "1") (pinfunction "1_1") (pintype "passive"))
    )
    (net (code "443") (name "VCC+ADJ_4") (class "Default")
      (node (ref "P12") (pin "8") (pinfunction "8_8") (pintype "passive"))
      (node (ref "R170") (pin "1") (pinfunction "1_1") (pintype "passive"))
    )
    (net (code "444") (name "VCC+ADJ_5") (class "Default")
      (node (ref "P13") (pin "8") (pinfunction "8_8") (pintype "passive"))
      (node (ref "R184") (pin "1") (pinfunction "1_1") (pintype "passive"))
    )
    (net (code "445") (name "VCC+ADJ_6") (class "Default")
      (node (ref "P14") (pin "8") (pinfunction "8_8") (pintype "passive"))
      (node (ref "R196") (pin "1") (pinfunction "1_1") (pintype "passive"))
    )
    (net (code "446") (name "VCC+ADJ_7") (class "Default")
      (node (ref "P15") (pin "8") (pinfunction "8_8") (pintype "passive"))
      (node (ref "R208") (pin "1") (pinfunction "1_1") (pintype "passive"))
    )
    (net (code "447") (name "VCC_SPDT+5V0") (class "Default")
      (node (ref "C130") (pin "2") (pinfunction "2_2") (pintype "passive"))
      (node (ref "C131") (pin "2") (pinfunction "2_2") (pintype "passive"))
      (node (ref "C132") (pin "2") (pinfunction "2_2") (pintype "passive"))
      (node (ref "C133") (pin "2") (pinfunction "2_2") (pintype "passive"))
      (node (ref "C134") (pin "2") (pinfunction "2_2") (pintype "passive"))
      (node (ref "C135") (pin "2") (pinfunction "2_2") (pintype "passive"))
      (node (ref "C136") (pin "2") (pinfunction "2_2") (pintype "passive"))
      (node (ref "C137") (pin "2") (pinfunction "2_2") (pintype "passive"))
      (node (ref "C138") (pin "2") (pinfunction "2_2") (pintype "passive"))
      (node (ref "C139") (pin "2") (pinfunction "2_2") (pintype "passive"))
      (node (ref "C140") (pin "1") (pinfunction "1_1") (pintype "passive"))
      (node (ref "C141") (pin "1") (pinfunction "1_1") (pintype "passive"))
      (node (ref "C142") (pin "1") (pinfunction "1_1") (pintype "passive"))
      (node (ref "C143") (pin "1") (pinfunction "1_1") (pintype "passive"))
      (node (ref "C144") (pin "1") (pinfunction "1_1") (pintype "passive"))
      (node (ref "C145") (pin "1") (pinfunction "1_1") (pintype "passive"))
      (node (ref "C146") (pin "1") (pinfunction "1_1") (pintype "passive"))
      (node (ref "C147") (pin "1") (pinfunction "1_1") (pintype "passive"))
      (node (ref "C148") (pin "1") (pinfunction "1_1") (pintype "passive"))
      (node (ref "C149") (pin "1") (pinfunction "1_1") (pintype "passive"))
      (node (ref "C150") (pin "2") (pinfunction "2_2") (pintype "passive"))
      (node (ref "C151") (pin "2") (pinfunction "2_2") (pintype "passive"))
      (node (ref "C152") (pin "2") (pinfunction "2_2") (pintype "passive"))
      (node (ref "C153") (pin "2") (pinfunction "2_2") (pintype "passive"))
      (node (ref "C154") (pin "2") (pinfunction "2_2") (pintype "passive"))
      (node (ref "C155") (pin "2") (pinfunction "2_2") (pintype "passive"))
      (node (ref "C156") (pin "2") (pinfunction "2_2") (pintype "passive"))
      (node (ref "C157") (pin "2") (pinfunction "2_2") (pintype "passive"))
      (node (ref "C158") (pin "2") (pinfunction "2_2") (pintype "passive"))
      (node (ref "C159") (pin "2") (pinfunction "2_2") (pintype "passive"))
      (node (ref "C160") (pin "1") (pinfunction "1_1") (pintype "passive"))
      (node (ref "C161") (pin "1") (pinfunction "1_1") (pintype "passive"))
      (node (ref "C162") (pin "1") (pinfunction "1_1") (pintype "passive"))
      (node (ref "C163") (pin "1") (pinfunction "1_1") (pintype "passive"))
      (node (ref "C164") (pin "1") (pinfunction "1_1") (pintype "passive"))
      (node (ref "C165") (pin "1") (pinfunction "1_1") (pintype "passive"))
      (node (ref "C166") (pin "1") (pinfunction "1_1") (pintype "passive"))
      (node (ref "C167") (pin "1") (pinfunction "1_1") (pintype "passive"))
      (node (ref "C168") (pin "1") (pinfunction "1_1") (pintype "passive"))
      (node (ref "C169") (pin "1") (pinfunction "1_1") (pintype "passive"))
      (node (ref "C23") (pin "2") (pinfunction "2_2") (pintype "passive"))
      (node (ref "R172") (pin "2") (pinfunction "2_2") (pintype "passive"))
      (node (ref "R173") (pin "2") (pinfunction "2_2") (pintype "passive"))
      (node (ref "U10") (pin "16") (pinfunction "VCC_16") (pintype "passive"))
      (node (ref "U11") (pin "16") (pinfunction "VCC_16") (pintype "passive"))
      (node (ref "U12") (pin "16") (pinfunction "VCC_16") (pintype "passive"))
      (node (ref "U13") (pin "16") (pinfunction "VCC_16") (pintype "passive"))
      (node (ref "U14") (pin "16") (pinfunction "VCC_16") (pintype "passive"))
      (node (ref "U15") (pin "16") (pinfunction "VCC_16") (pintype "passive"))
      (node (ref "U16") (pin "16") (pinfunction "VCC_16") (pintype "passive"))
      (node (ref "U17") (pin "16") (pinfunction "VCC_16") (pintype "passive"))
      (node (ref "U18") (pin "16") (pinfunction "VCC_16") (pintype "passive"))
      (node (ref "U19") (pin "16") (pinfunction "VCC_16") (pintype "passive"))
      (node (ref "U20") (pin "16") (pinfunction "VCC_16") (pintype "passive"))
      (node (ref "U21") (pin "16") (pinfunction "VCC_16") (pintype "passive"))
      (node (ref "U22") (pin "16") (pinfunction "VCC_16") (pintype "passive"))
      (node (ref "U23") (pin "16") (pinfunction "VCC_16") (pintype "passive"))
      (node (ref "U24") (pin "16") (pinfunction "VCC_16") (pintype "passive"))
      (node (ref "U25") (pin "16") (pinfunction "VCC_16") (pintype "passive"))
      (node (ref "U26") (pin "16") (pinfunction "VCC_16") (pintype "passive"))
      (node (ref "U27") (pin "16") (pinfunction "VCC_16") (pintype "passive"))
      (node (ref "U28") (pin "16") (pinfunction "VCC_16") (pintype "passive"))
      (node (ref "U29") (pin "16") (pinfunction "VCC_16") (pintype "passive"))
      (node (ref "U30") (pin "16") (pinfunction "VCC_16") (pintype "passive"))
      (node (ref "U31") (pin "16") (pinfunction "VCC_16") (pintype "passive"))
      (node (ref "U32") (pin "16") (pinfunction "VCC_16") (pintype "passive"))
      (node (ref "U33") (pin "16") (pinfunction "VCC_16") (pintype "passive"))
      (node (ref "U34") (pin "16") (pinfunction "VCC_16") (pintype "passive"))
      (node (ref "U35") (pin "16") (pinfunction "VCC_16") (pintype "passive"))
      (node (ref "U36") (pin "16") (pinfunction "VCC_16") (pintype "passive"))
      (node (ref "U37") (pin "16") (pinfunction "VCC_16") (pintype "passive"))
      (node (ref "U38") (pin "16") (pinfunction "VCC_16") (pintype "passive"))
      (node (ref "U39") (pin "16") (pinfunction "VCC_16") (pintype "passive"))
      (node (ref "U40") (pin "16") (pinfunction "VCC_16") (pintype "passive"))
      (node (ref "U41") (pin "16") (pinfunction "VCC_16") (pintype "passive"))
      (node (ref "U42") (pin "16") (pinfunction "VCC_16") (pintype "passive"))
      (node (ref "U43") (pin "16") (pinfunction "VCC_16") (pintype "passive"))
      (node (ref "U44") (pin "16") (pinfunction "VCC_16") (pintype "passive"))
      (node (ref "U45") (pin "16") (pinfunction "VCC_16") (pintype "passive"))
      (node (ref "U50") (pin "2") (pinfunction "VOUT_2") (pintype "passive"))
      (node (ref "U51") (pin "8") (pinfunction "VDD_8") (pintype "passive"))
      (node (ref "U8") (pin "16") (pinfunction "VCC_16") (pintype "passive"))
      (node (ref "U9") (pin "16") (pinfunction "VCC_16") (pintype "passive"))
    )
    (net (code "448") (name "unconnected-(U51-AIN2-Pad6)") (class "Default")
      (node (ref "U51") (pin "6") (pinfunction "AIN2_6") (pintype "passive+no_connect"))
    )
    (net (code "449") (name "unconnected-(U51-AIN3-Pad7)") (class "Default")
      (node (ref "U51") (pin "7") (pinfunction "AIN3_7") (pintype "passive+no_connect"))
    )
    (net (code "450") (name "unconnected-(U51-RDY-Pad2)") (class "Default")
      (node (ref "U51") (pin "2") (pinfunction "RDY_2") (pintype "passive+no_connect"))
    )
  )
)
